# ADC.net
KiCad netlist of a schematic drawn in EAGLE
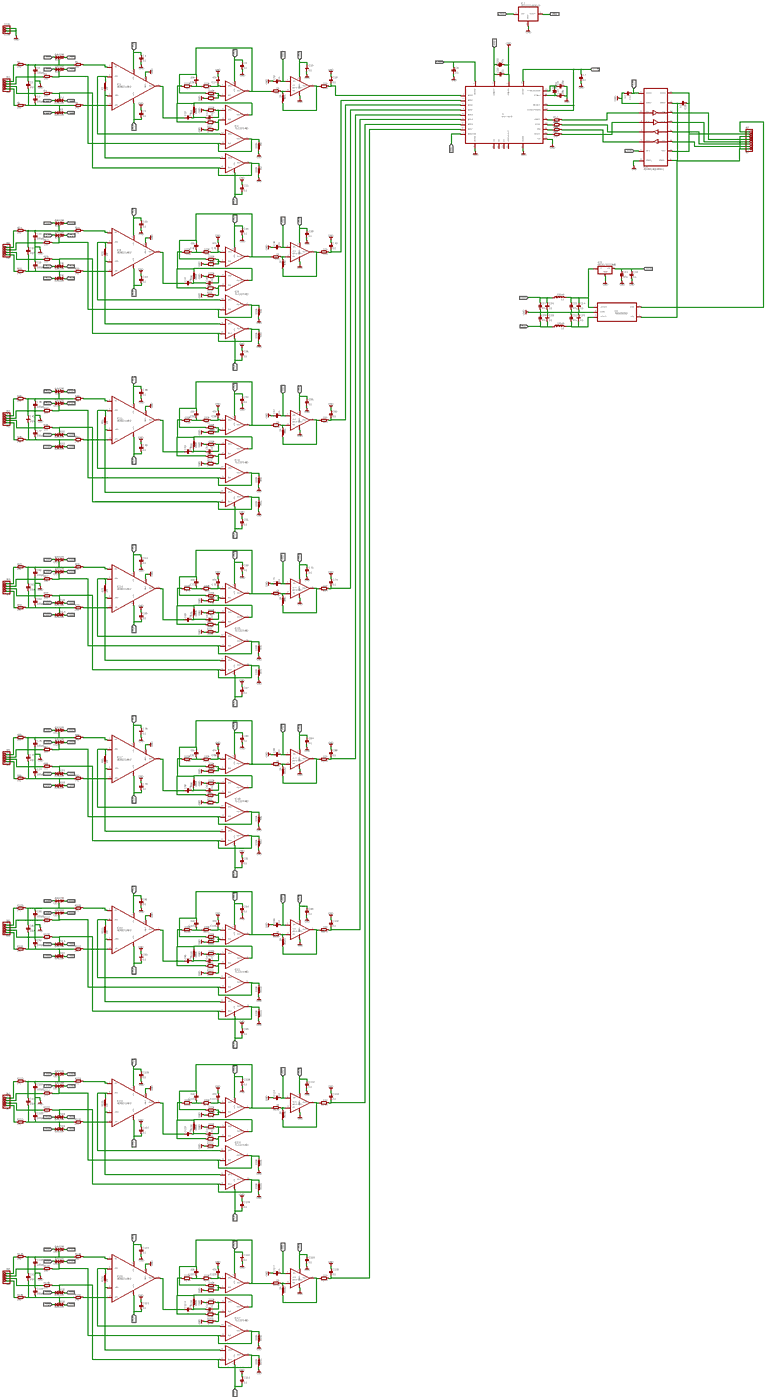
[diagram p0: schematic, sheet 1, overview]
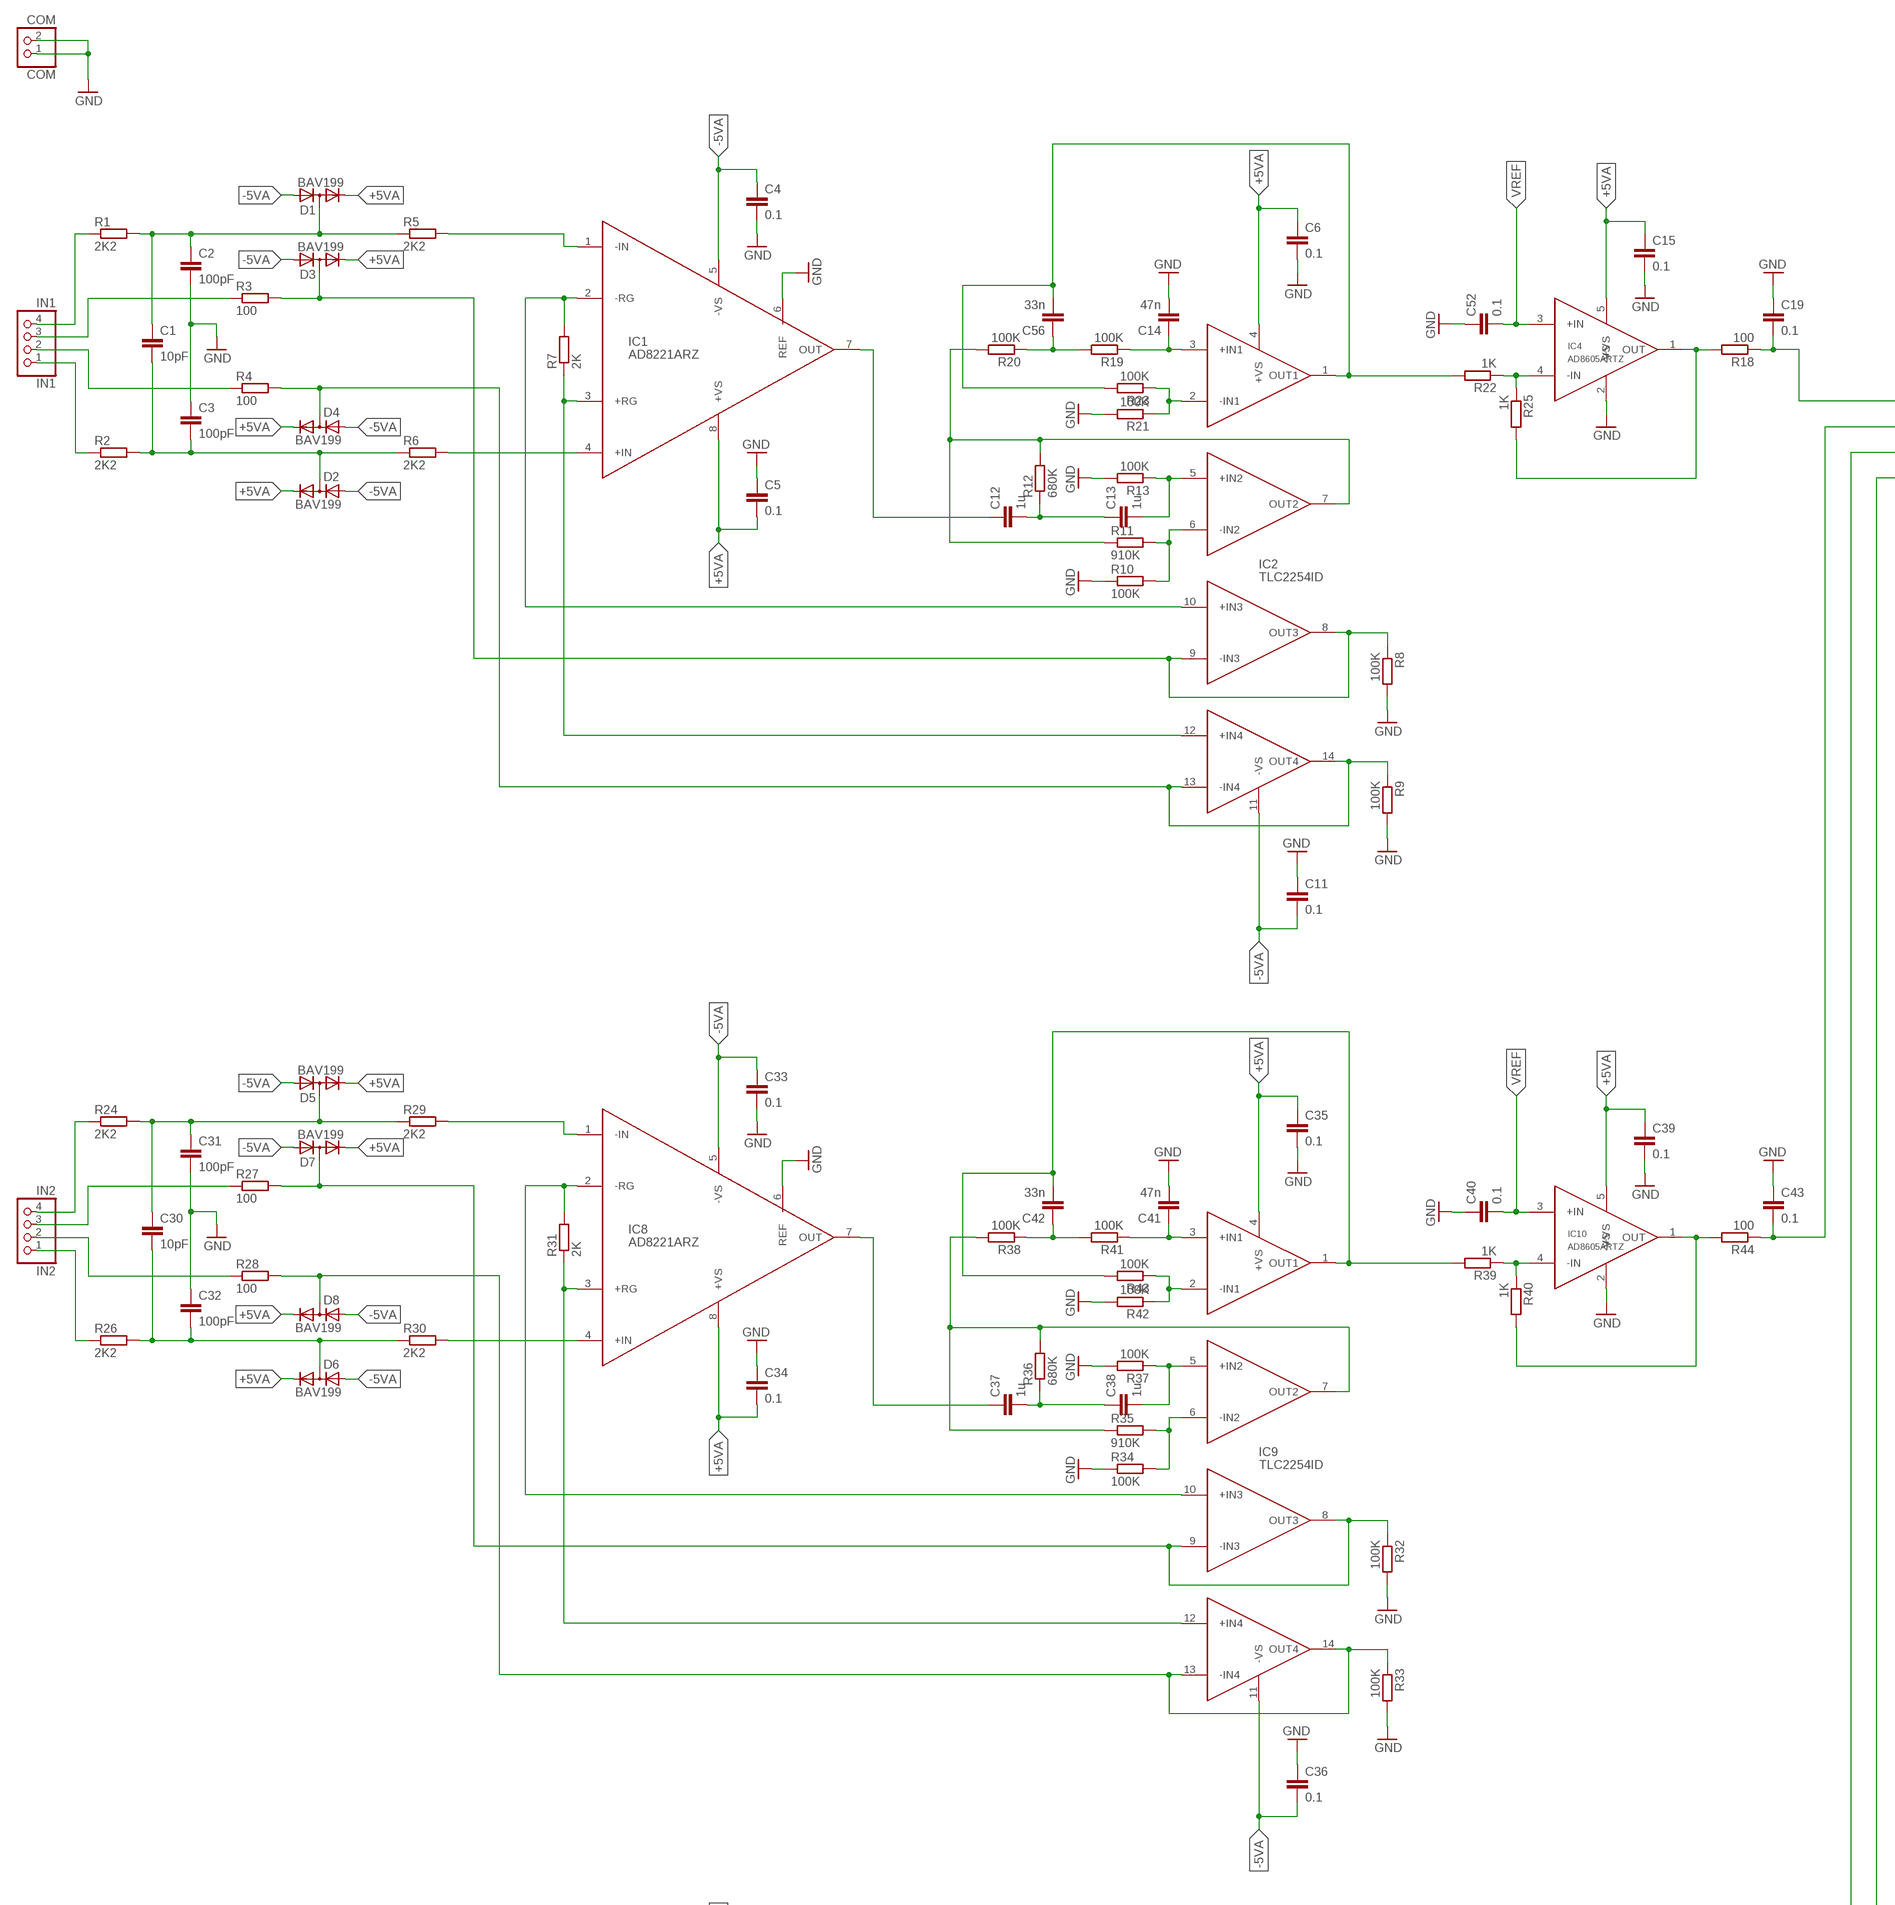
[diagram p1: schematic, sheet 1, part 1 of 5]
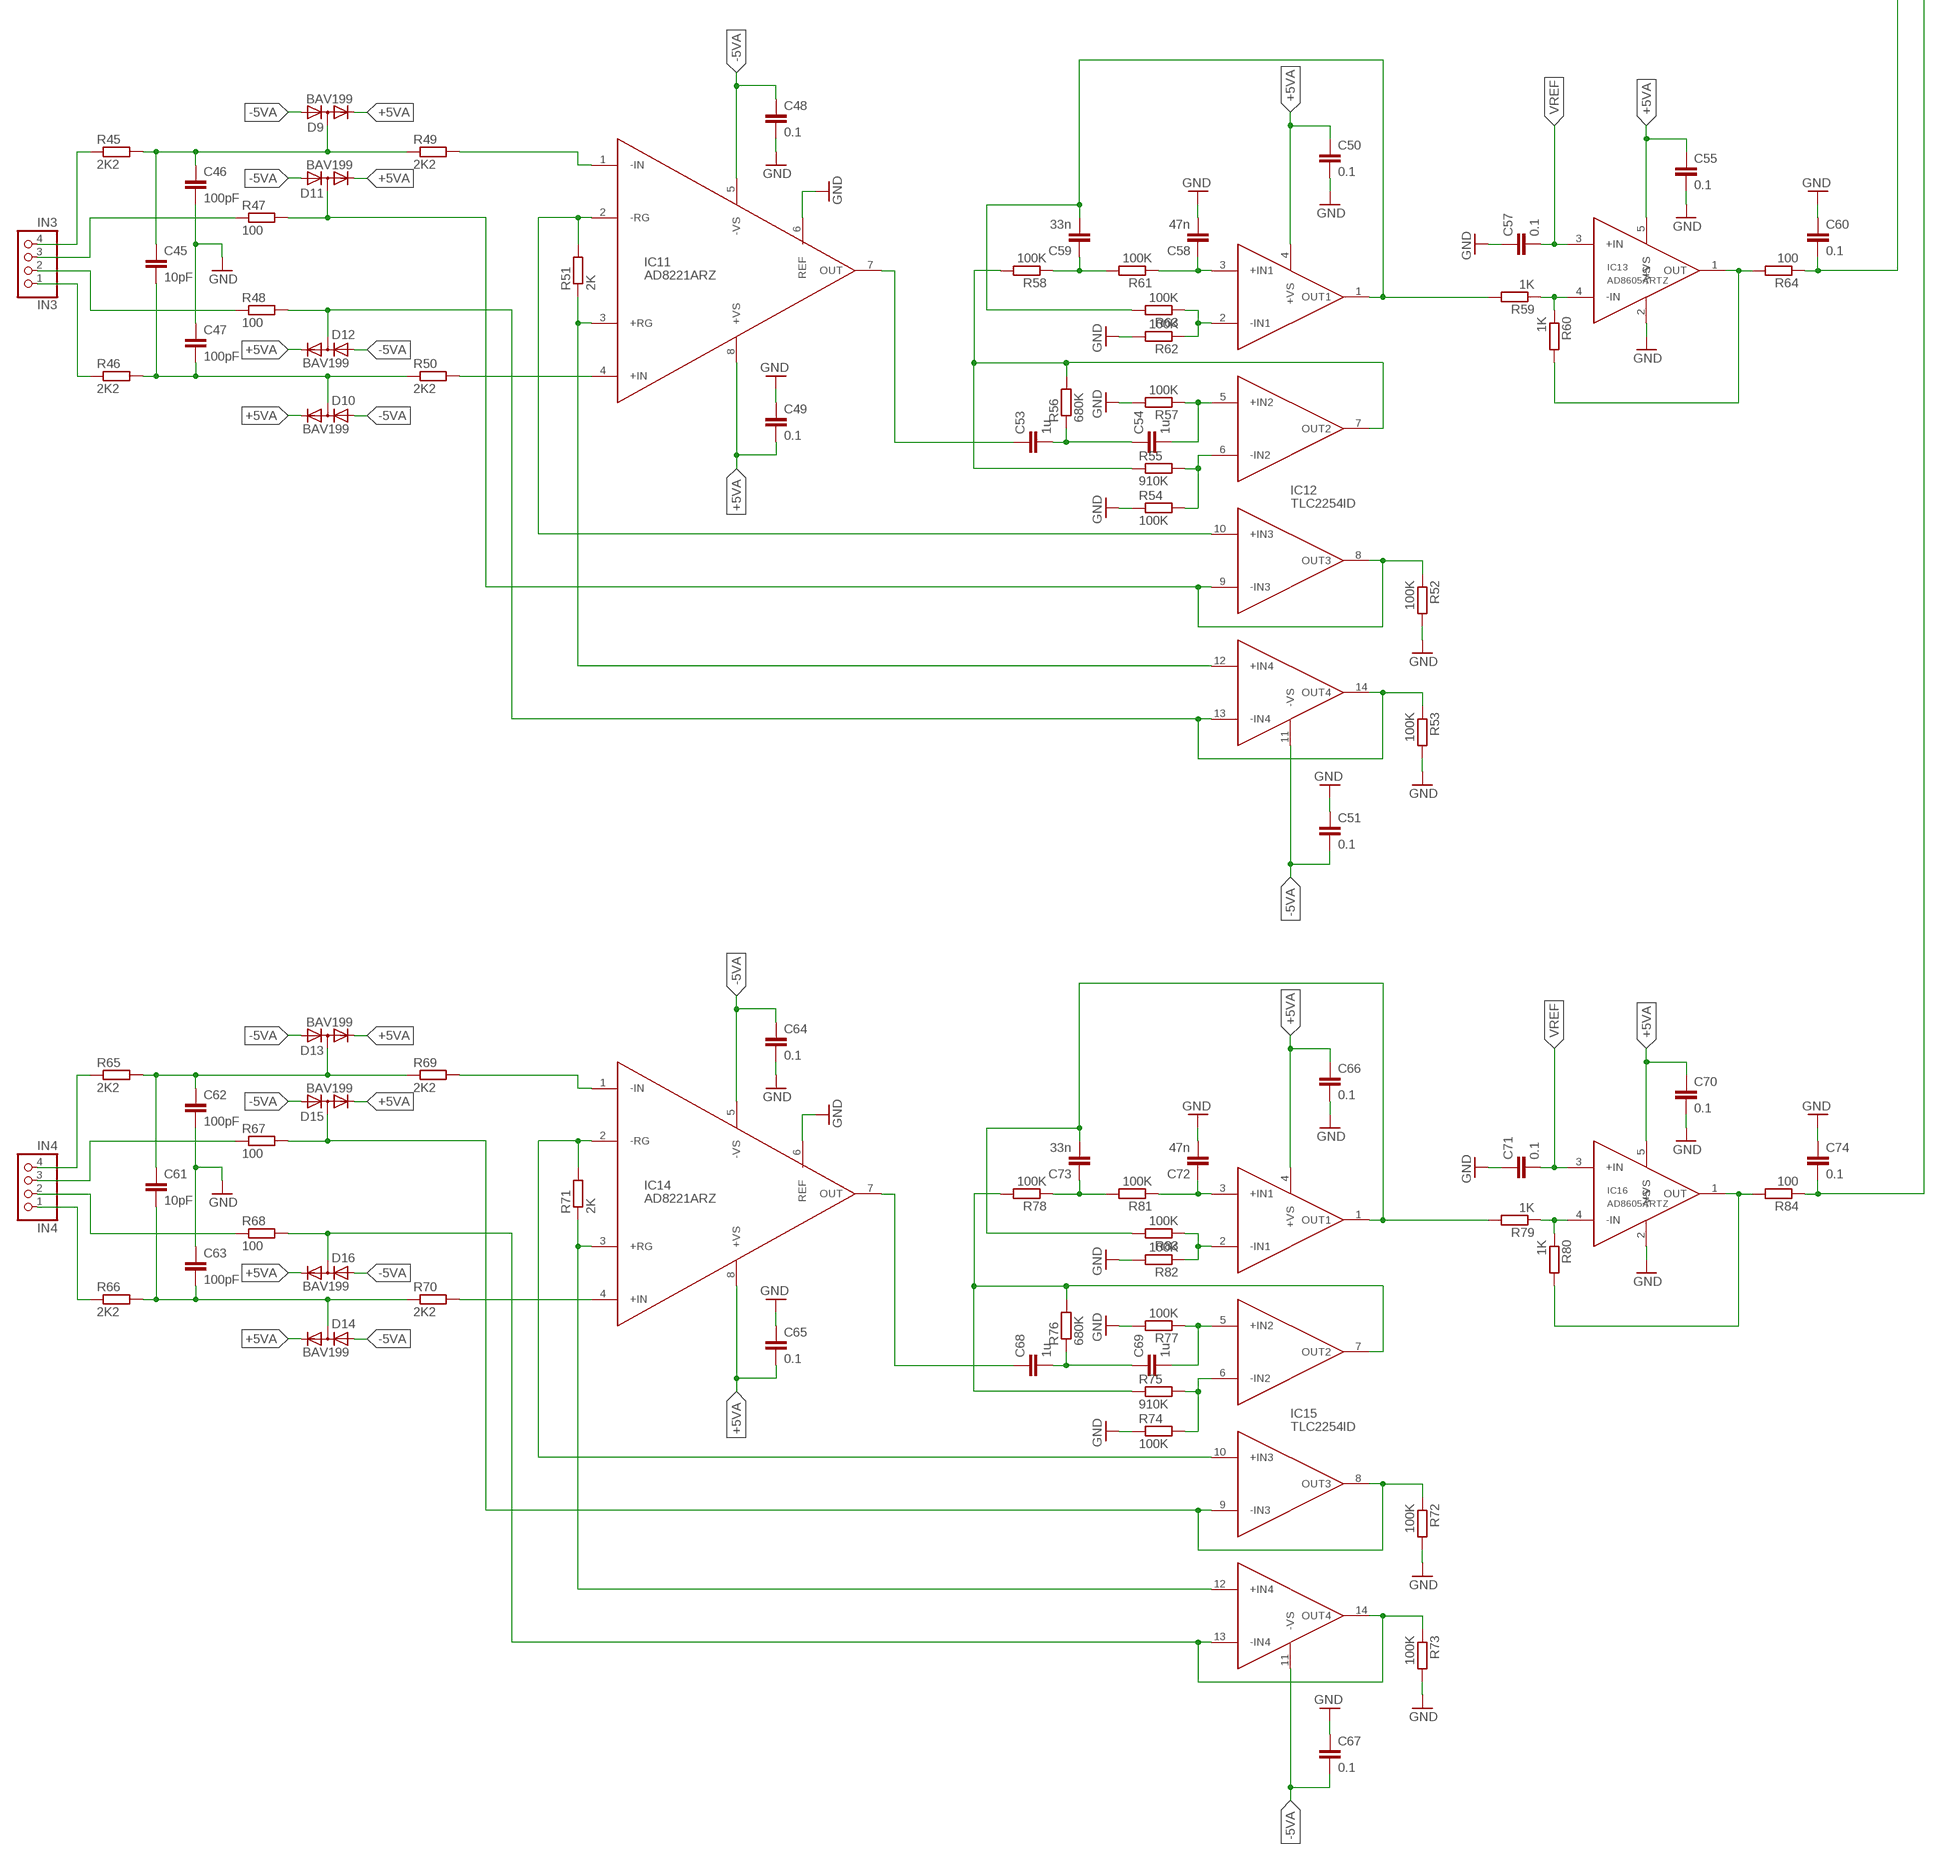
[diagram p2: schematic, sheet 1, part 2 of 5]
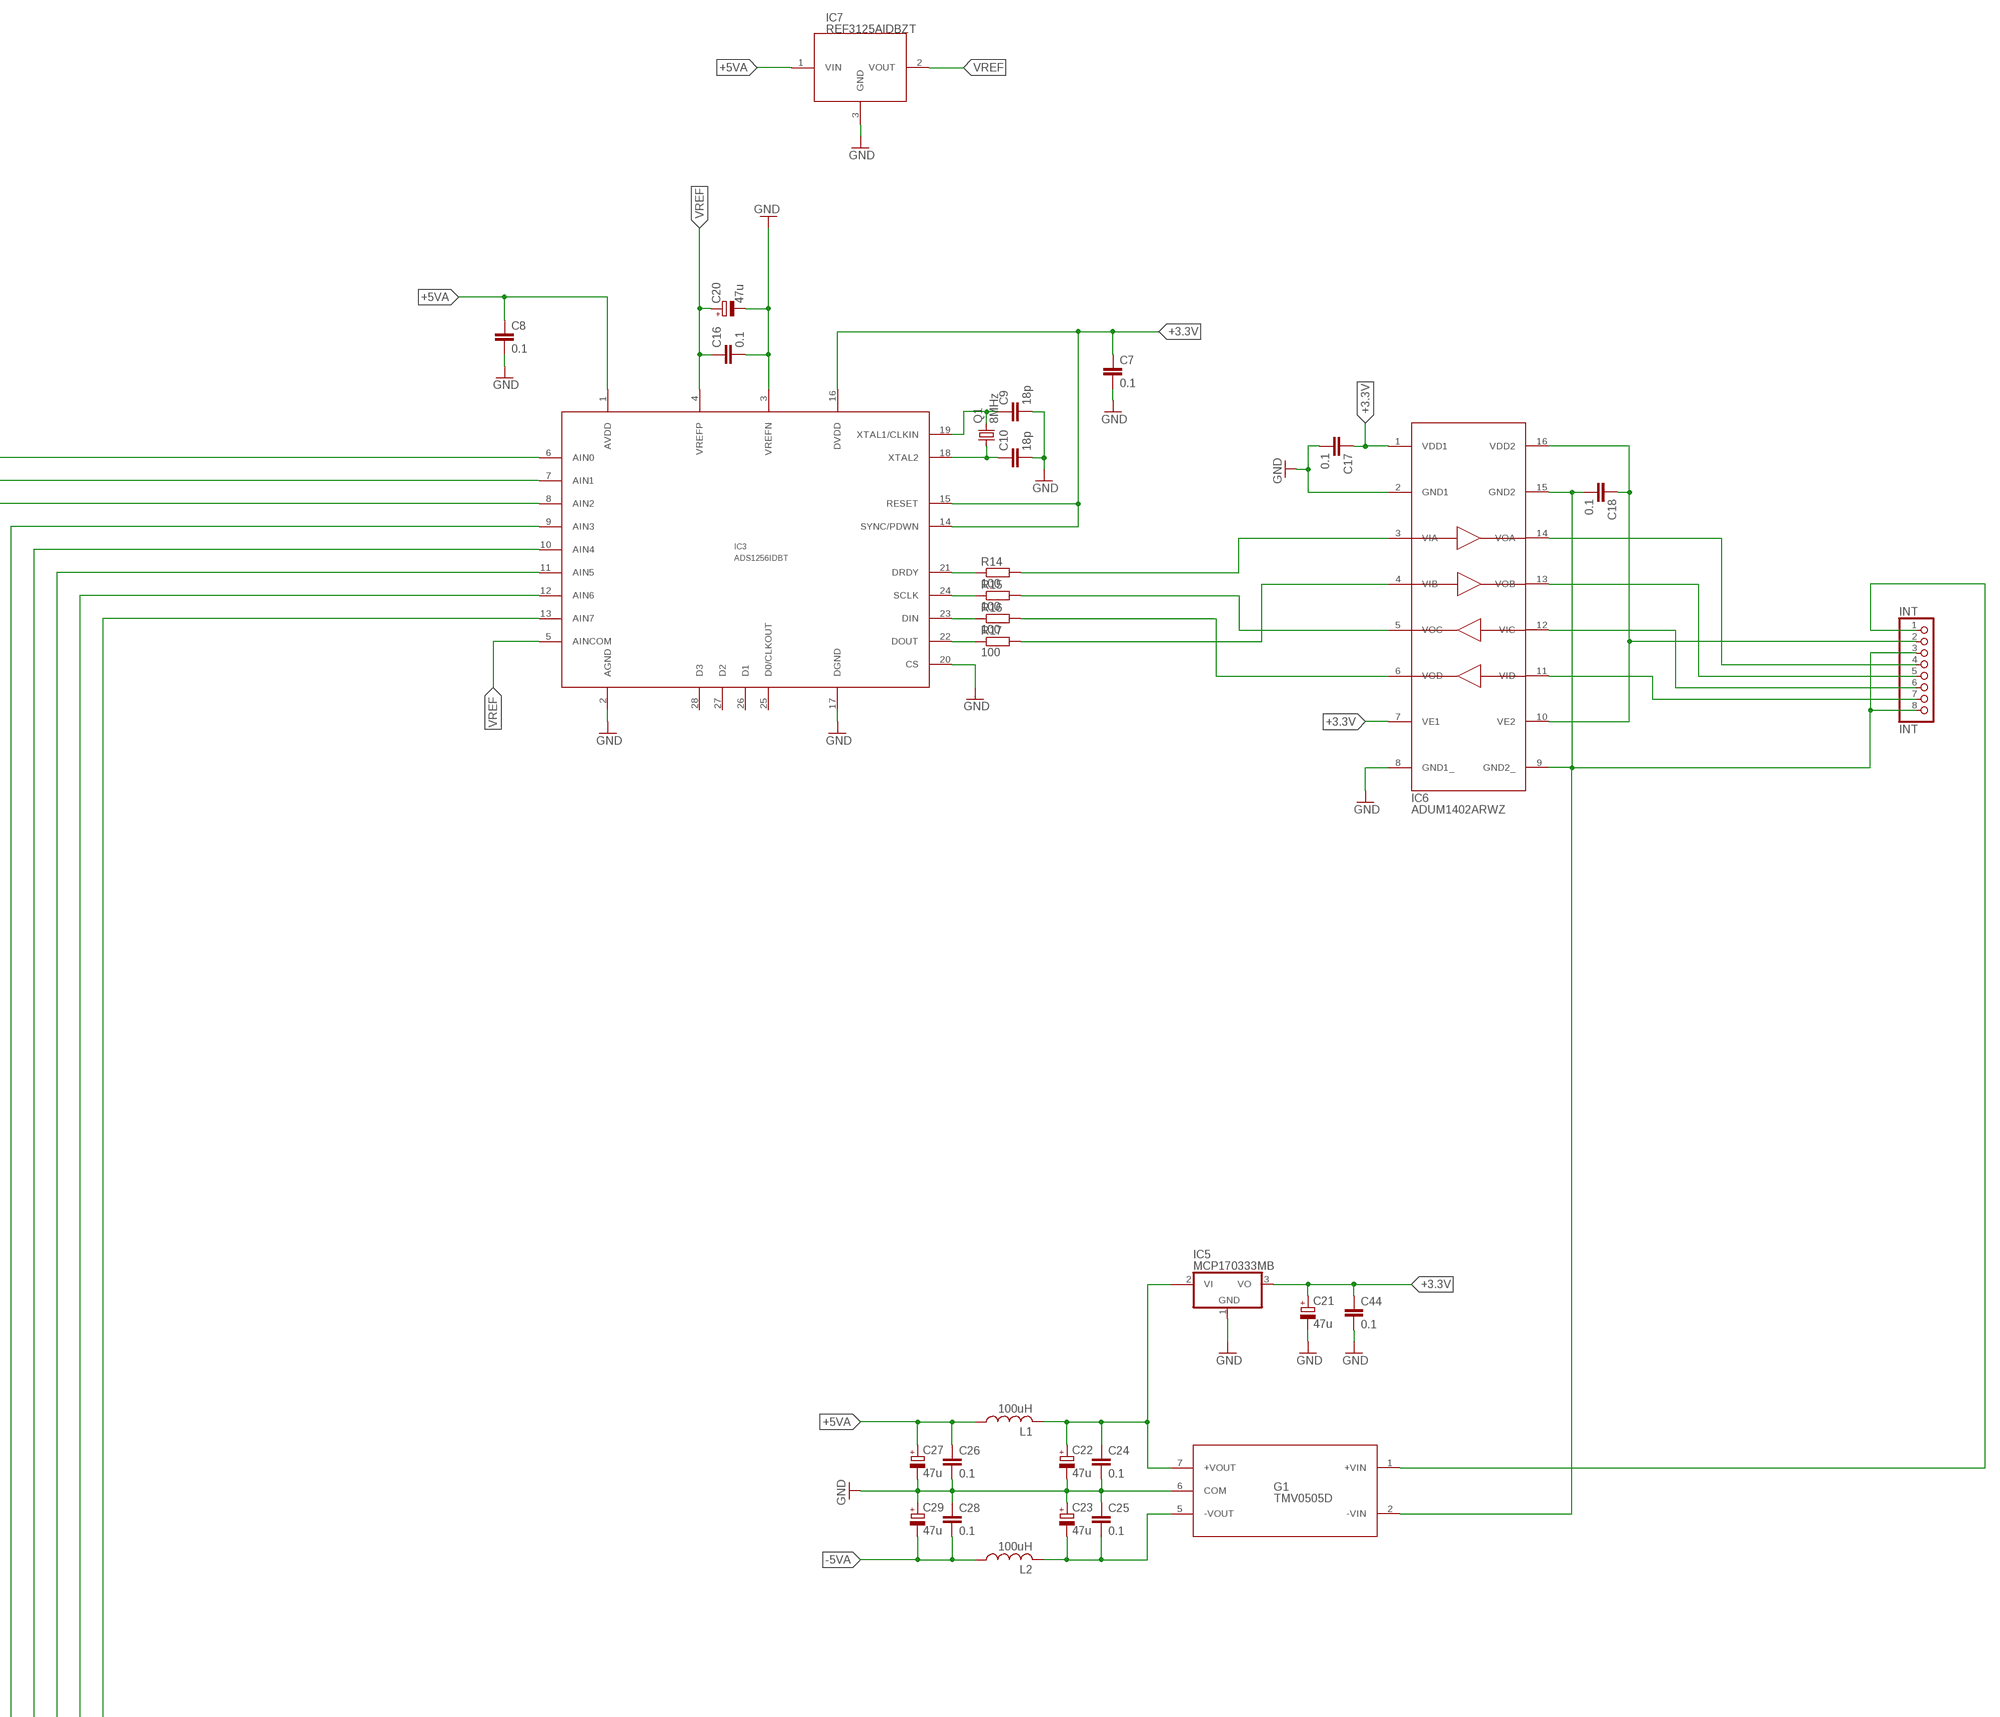
[diagram p3: schematic, sheet 1, part 3 of 5]
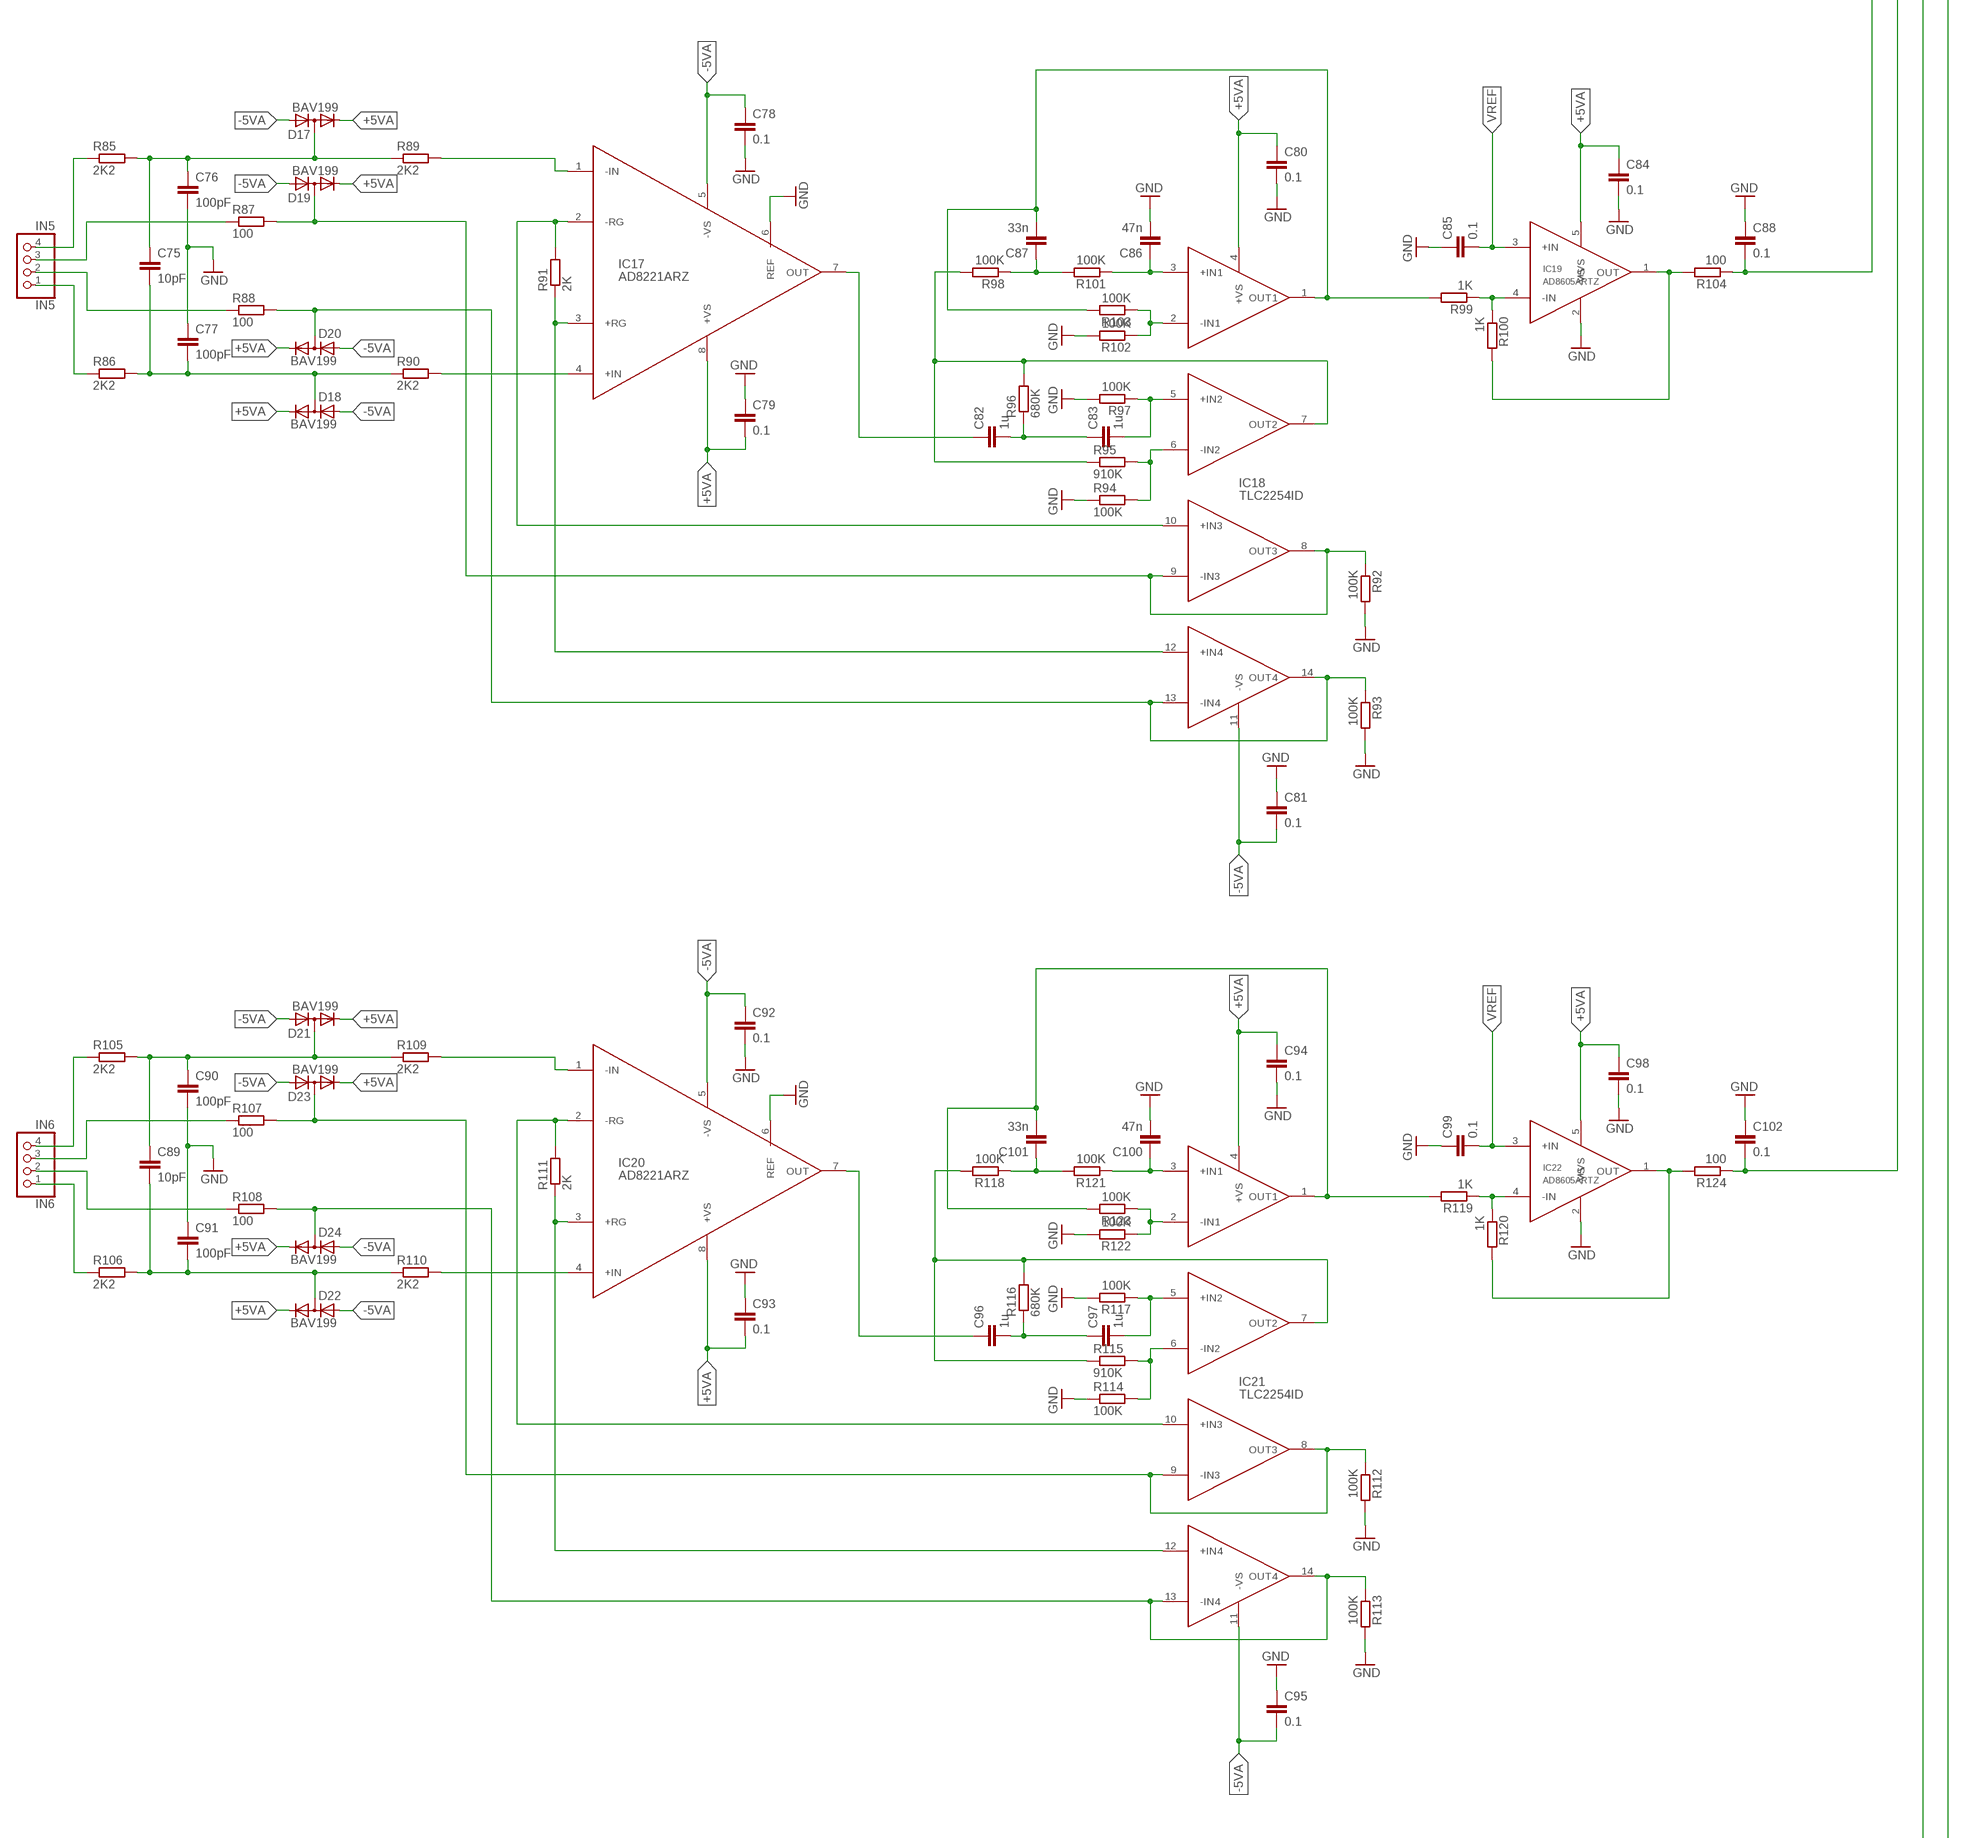
[diagram p4: schematic, sheet 1, part 4 of 5]
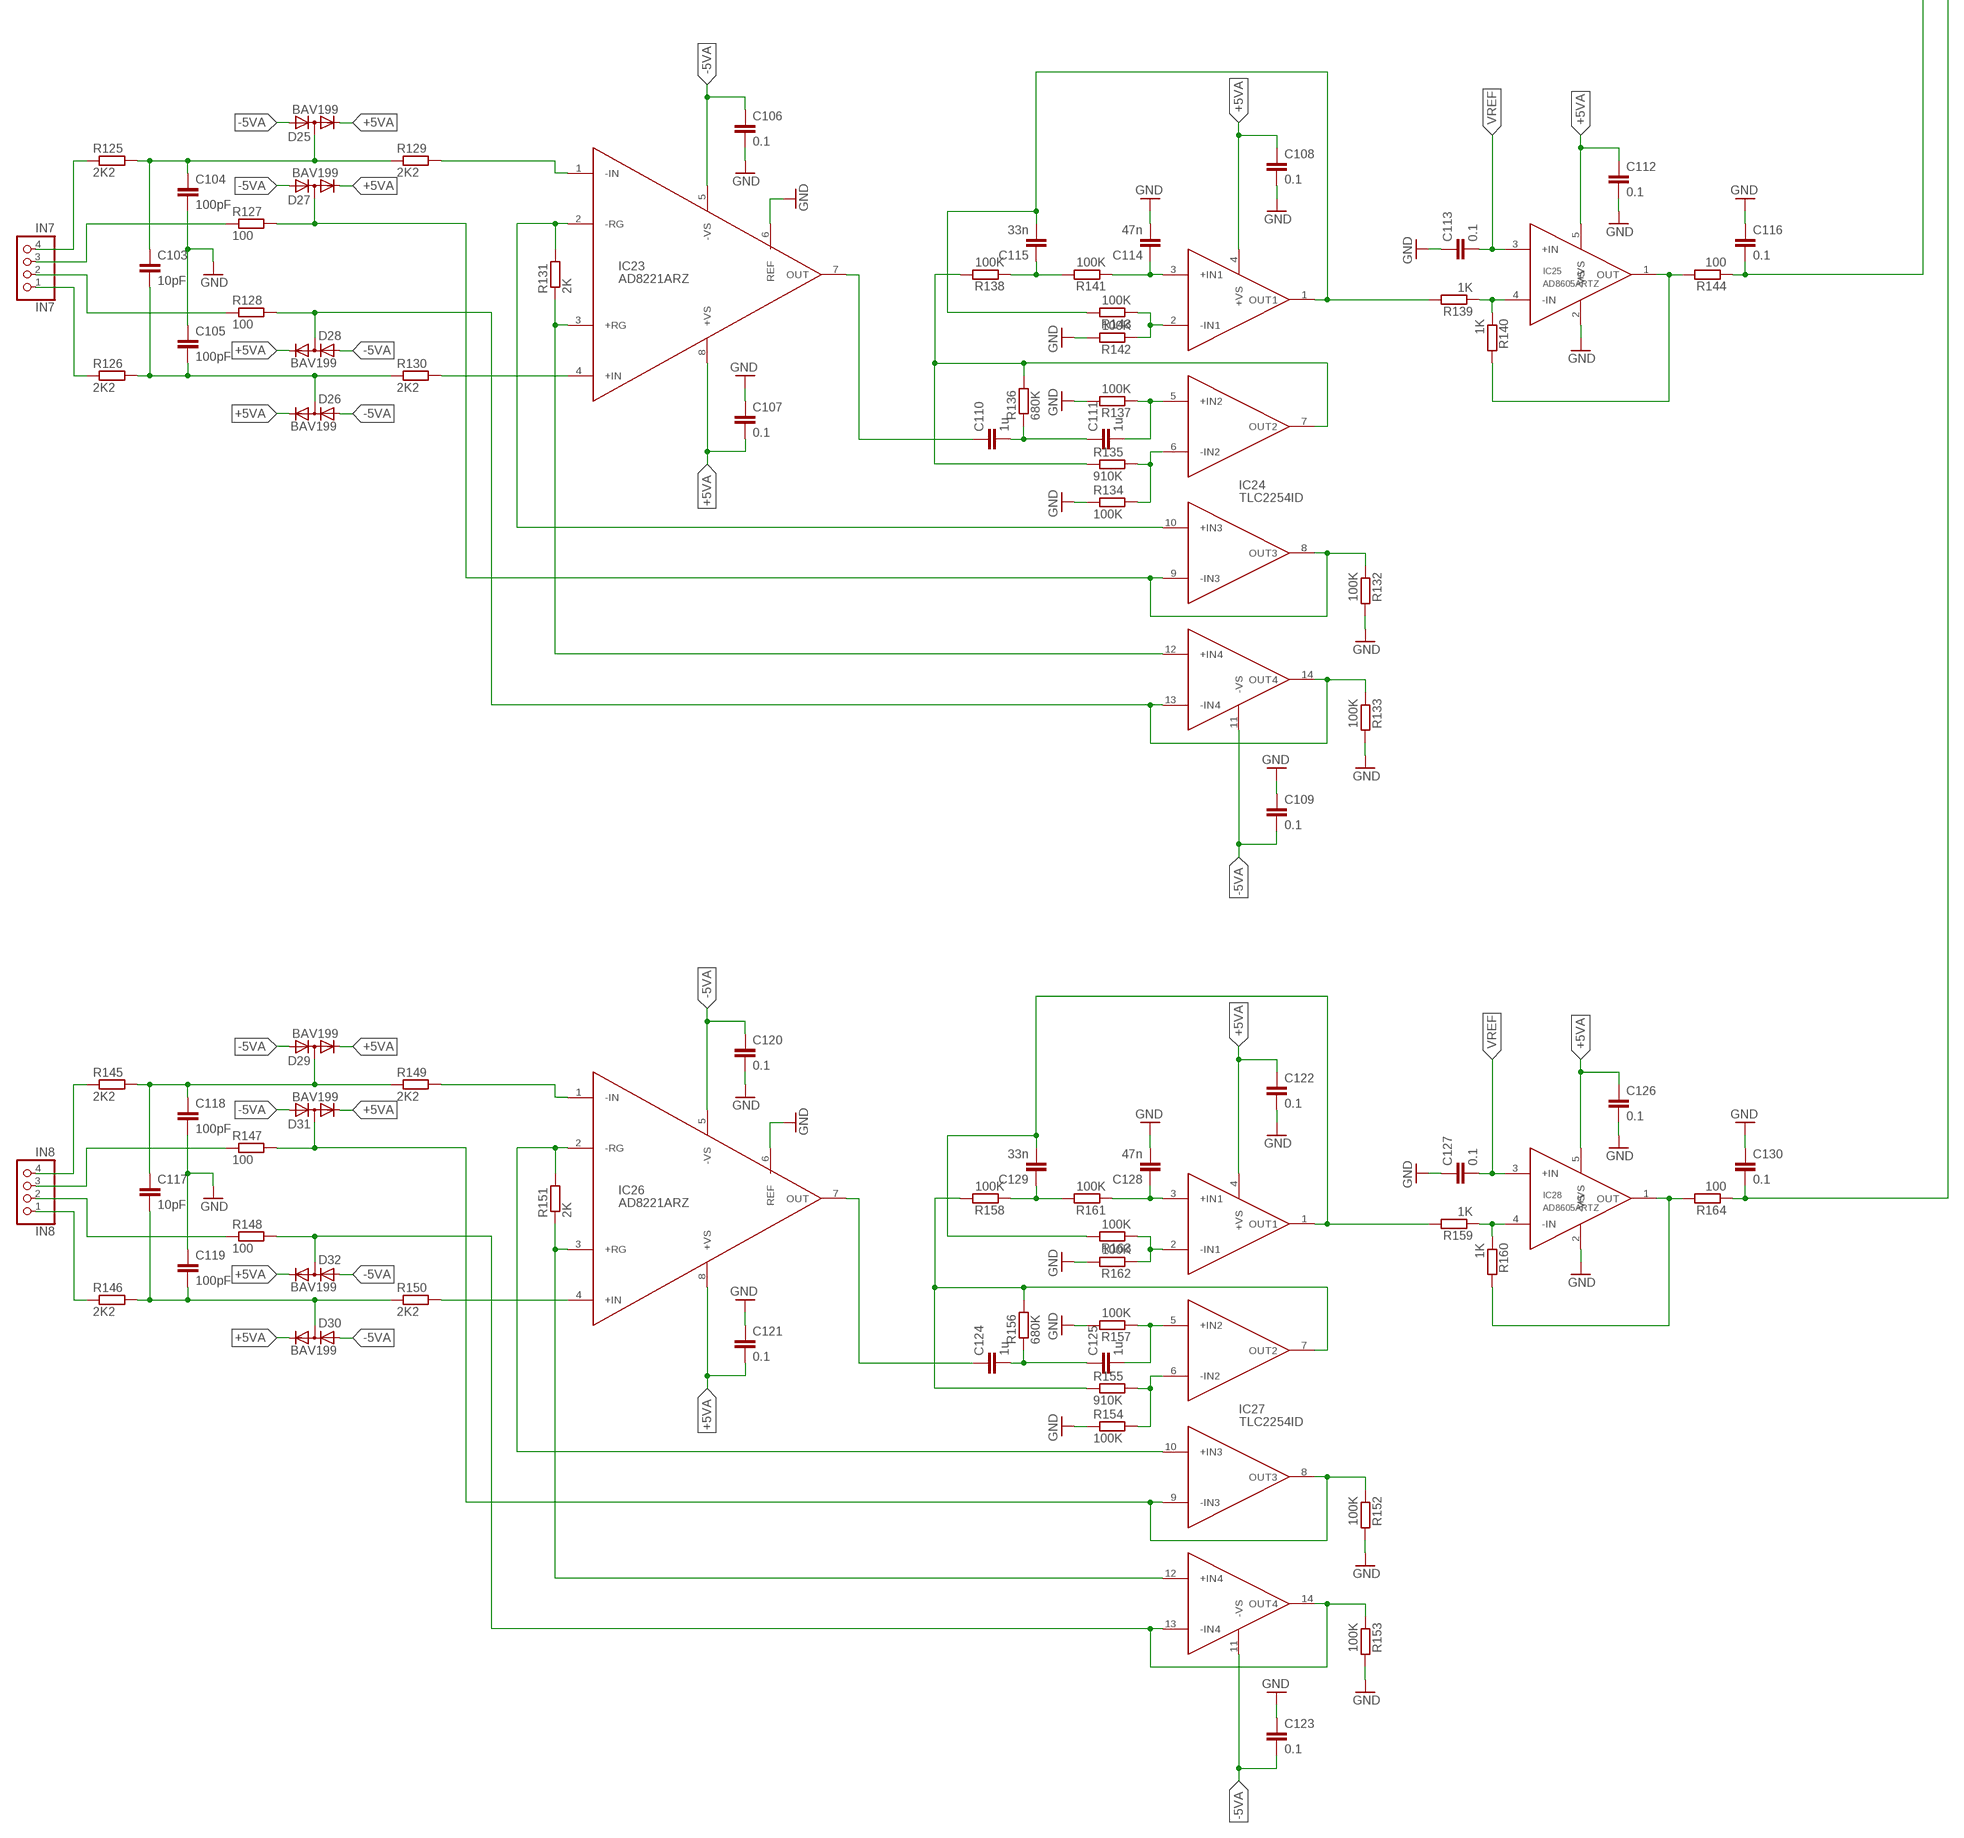
[diagram p5: schematic, sheet 1, part 5 of 5]

(export (version "E")
  (design (tool "Eeschema 10.0.6"))
  (components
    (comp (ref "C1")
      (value "10pF")
      (footprint "eagle-import:C0805")
      (libsource (lib "eagle-import") (part "C-EUC0805"))
    )
    (comp (ref "C2")
      (value "100pF")
      (footprint "eagle-import:C0805")
      (libsource (lib "eagle-import") (part "C-EUC0805"))
    )
    (comp (ref "C3")
      (value "100pF")
      (footprint "eagle-import:C0805")
      (libsource (lib "eagle-import") (part "C-EUC0805"))
    )
    (comp (ref "C4")
      (value "0.1")
      (footprint "eagle-import:C0805")
      (libsource (lib "eagle-import") (part "C-EUC0805"))
    )
    (comp (ref "C5")
      (value "0.1")
      (footprint "eagle-import:C0805")
      (libsource (lib "eagle-import") (part "C-EUC0805"))
    )
    (comp (ref "C6")
      (value "0.1")
      (footprint "eagle-import:C0805")
      (libsource (lib "eagle-import") (part "C-EUC0805"))
    )
    (comp (ref "C7")
      (value "0.1")
      (footprint "eagle-import:C0805")
      (libsource (lib "eagle-import") (part "C-EUC0805"))
    )
    (comp (ref "C8")
      (value "0.1")
      (footprint "eagle-import:C0805")
      (libsource (lib "eagle-import") (part "C-EUC0805"))
    )
    (comp (ref "C9")
      (value "18p")
      (footprint "eagle-import:C0805")
      (libsource (lib "eagle-import") (part "C-EUC0805"))
    )
    (comp (ref "C10")
      (value "18p")
      (footprint "eagle-import:C0805")
      (libsource (lib "eagle-import") (part "C-EUC0805"))
    )
    (comp (ref "C11")
      (value "0.1")
      (footprint "eagle-import:C0805")
      (libsource (lib "eagle-import") (part "C-EUC0805"))
    )
    (comp (ref "C12")
      (value "1u")
      (footprint "eagle-import:C0805")
      (libsource (lib "eagle-import") (part "C-EUC0805"))
    )
    (comp (ref "C13")
      (value "1u")
      (footprint "eagle-import:C0805")
      (libsource (lib "eagle-import") (part "C-EUC0805"))
    )
    (comp (ref "C14")
      (value "47n")
      (footprint "eagle-import:C0805")
      (libsource (lib "eagle-import") (part "C-EUC0805"))
    )
    (comp (ref "C15")
      (value "0.1")
      (footprint "eagle-import:C0805")
      (libsource (lib "eagle-import") (part "C-EUC0805"))
    )
    (comp (ref "C16")
      (value "0.1")
      (footprint "eagle-import:C0805")
      (libsource (lib "eagle-import") (part "C-EUC0805"))
    )
    (comp (ref "C17")
      (value "0.1")
      (footprint "eagle-import:C0805")
      (libsource (lib "eagle-import") (part "C-EUC0805"))
    )
    (comp (ref "C18")
      (value "0.1")
      (footprint "eagle-import:C0805")
      (libsource (lib "eagle-import") (part "C-EUC0805"))
    )
    (comp (ref "C19")
      (value "0.1")
      (footprint "eagle-import:C0805")
      (libsource (lib "eagle-import") (part "C-EUC0805"))
    )
    (comp (ref "C20")
      (value "47u")
      (footprint "eagle-import:E2-4")
      (libsource (lib "eagle-import") (part "CPOL-EUE2-4"))
    )
    (comp (ref "C21")
      (value "47u")
      (footprint "eagle-import:E2-4")
      (libsource (lib "eagle-import") (part "CPOL-EUE2-4"))
    )
    (comp (ref "C22")
      (value "47u")
      (footprint "eagle-import:E2-4")
      (libsource (lib "eagle-import") (part "CPOL-EUE2-4"))
    )
    (comp (ref "C23")
      (value "47u")
      (footprint "eagle-import:E2-4")
      (libsource (lib "eagle-import") (part "CPOL-EUE2-4"))
    )
    (comp (ref "C24")
      (value "0.1")
      (footprint "eagle-import:C0805")
      (libsource (lib "eagle-import") (part "C-EUC0805"))
    )
    (comp (ref "C25")
      (value "0.1")
      (footprint "eagle-import:C0805")
      (libsource (lib "eagle-import") (part "C-EUC0805"))
    )
    (comp (ref "C26")
      (value "0.1")
      (footprint "eagle-import:C0805")
      (libsource (lib "eagle-import") (part "C-EUC0805"))
    )
    (comp (ref "C27")
      (value "47u")
      (footprint "eagle-import:E2-4")
      (libsource (lib "eagle-import") (part "CPOL-EUE2-4"))
    )
    (comp (ref "C28")
      (value "0.1")
      (footprint "eagle-import:C0805")
      (libsource (lib "eagle-import") (part "C-EUC0805"))
    )
    (comp (ref "C29")
      (value "47u")
      (footprint "eagle-import:E2-4")
      (libsource (lib "eagle-import") (part "CPOL-EUE2-4"))
    )
    (comp (ref "C30")
      (value "10pF")
      (footprint "eagle-import:C0805")
      (libsource (lib "eagle-import") (part "C-EUC0805"))
    )
    (comp (ref "C31")
      (value "100pF")
      (footprint "eagle-import:C0805")
      (libsource (lib "eagle-import") (part "C-EUC0805"))
    )
    (comp (ref "C32")
      (value "100pF")
      (footprint "eagle-import:C0805")
      (libsource (lib "eagle-import") (part "C-EUC0805"))
    )
    (comp (ref "C33")
      (value "0.1")
      (footprint "eagle-import:C0805")
      (libsource (lib "eagle-import") (part "C-EUC0805"))
    )
    (comp (ref "C34")
      (value "0.1")
      (footprint "eagle-import:C0805")
      (libsource (lib "eagle-import") (part "C-EUC0805"))
    )
    (comp (ref "C35")
      (value "0.1")
      (footprint "eagle-import:C0805")
      (libsource (lib "eagle-import") (part "C-EUC0805"))
    )
    (comp (ref "C36")
      (value "0.1")
      (footprint "eagle-import:C0805")
      (libsource (lib "eagle-import") (part "C-EUC0805"))
    )
    (comp (ref "C37")
      (value "1u")
      (footprint "eagle-import:C0805")
      (libsource (lib "eagle-import") (part "C-EUC0805"))
    )
    (comp (ref "C38")
      (value "1u")
      (footprint "eagle-import:C0805")
      (libsource (lib "eagle-import") (part "C-EUC0805"))
    )
    (comp (ref "C39")
      (value "0.1")
      (footprint "eagle-import:C0805")
      (libsource (lib "eagle-import") (part "C-EUC0805"))
    )
    (comp (ref "C40")
      (value "0.1")
      (footprint "eagle-import:C0805")
      (libsource (lib "eagle-import") (part "C-EUC0805"))
    )
    (comp (ref "C41")
      (value "47n")
      (footprint "eagle-import:C0805")
      (libsource (lib "eagle-import") (part "C-EUC0805"))
    )
    (comp (ref "C42")
      (value "33n")
      (footprint "eagle-import:C0805")
      (libsource (lib "eagle-import") (part "C-EUC0805"))
    )
    (comp (ref "C43")
      (value "0.1")
      (footprint "eagle-import:C0805")
      (libsource (lib "eagle-import") (part "C-EUC0805"))
    )
    (comp (ref "C44")
      (value "0.1")
      (footprint "eagle-import:C0805")
      (libsource (lib "eagle-import") (part "C-EUC0805"))
    )
    (comp (ref "C45")
      (value "10pF")
      (footprint "eagle-import:C0805")
      (libsource (lib "eagle-import") (part "C-EUC0805"))
    )
    (comp (ref "C46")
      (value "100pF")
      (footprint "eagle-import:C0805")
      (libsource (lib "eagle-import") (part "C-EUC0805"))
    )
    (comp (ref "C47")
      (value "100pF")
      (footprint "eagle-import:C0805")
      (libsource (lib "eagle-import") (part "C-EUC0805"))
    )
    (comp (ref "C48")
      (value "0.1")
      (footprint "eagle-import:C0805")
      (libsource (lib "eagle-import") (part "C-EUC0805"))
    )
    (comp (ref "C49")
      (value "0.1")
      (footprint "eagle-import:C0805")
      (libsource (lib "eagle-import") (part "C-EUC0805"))
    )
    (comp (ref "C50")
      (value "0.1")
      (footprint "eagle-import:C0805")
      (libsource (lib "eagle-import") (part "C-EUC0805"))
    )
    (comp (ref "C51")
      (value "0.1")
      (footprint "eagle-import:C0805")
      (libsource (lib "eagle-import") (part "C-EUC0805"))
    )
    (comp (ref "C52")
      (value "0.1")
      (footprint "eagle-import:C0805")
      (libsource (lib "eagle-import") (part "C-EUC0805"))
    )
    (comp (ref "C53")
      (value "1u")
      (footprint "eagle-import:C0805")
      (libsource (lib "eagle-import") (part "C-EUC0805"))
    )
    (comp (ref "C54")
      (value "1u")
      (footprint "eagle-import:C0805")
      (libsource (lib "eagle-import") (part "C-EUC0805"))
    )
    (comp (ref "C55")
      (value "0.1")
      (footprint "eagle-import:C0805")
      (libsource (lib "eagle-import") (part "C-EUC0805"))
    )
    (comp (ref "C56")
      (value "33n")
      (footprint "eagle-import:C0805")
      (libsource (lib "eagle-import") (part "C-EUC0805"))
    )
    (comp (ref "C57")
      (value "0.1")
      (footprint "eagle-import:C0805")
      (libsource (lib "eagle-import") (part "C-EUC0805"))
    )
    (comp (ref "C58")
      (value "47n")
      (footprint "eagle-import:C0805")
      (libsource (lib "eagle-import") (part "C-EUC0805"))
    )
    (comp (ref "C59")
      (value "33n")
      (footprint "eagle-import:C0805")
      (libsource (lib "eagle-import") (part "C-EUC0805"))
    )
    (comp (ref "C60")
      (value "0.1")
      (footprint "eagle-import:C0805")
      (libsource (lib "eagle-import") (part "C-EUC0805"))
    )
    (comp (ref "C61")
      (value "10pF")
      (footprint "eagle-import:C0805")
      (libsource (lib "eagle-import") (part "C-EUC0805"))
    )
    (comp (ref "C62")
      (value "100pF")
      (footprint "eagle-import:C0805")
      (libsource (lib "eagle-import") (part "C-EUC0805"))
    )
    (comp (ref "C63")
      (value "100pF")
      (footprint "eagle-import:C0805")
      (libsource (lib "eagle-import") (part "C-EUC0805"))
    )
    (comp (ref "C64")
      (value "0.1")
      (footprint "eagle-import:C0805")
      (libsource (lib "eagle-import") (part "C-EUC0805"))
    )
    (comp (ref "C65")
      (value "0.1")
      (footprint "eagle-import:C0805")
      (libsource (lib "eagle-import") (part "C-EUC0805"))
    )
    (comp (ref "C66")
      (value "0.1")
      (footprint "eagle-import:C0805")
      (libsource (lib "eagle-import") (part "C-EUC0805"))
    )
    (comp (ref "C67")
      (value "0.1")
      (footprint "eagle-import:C0805")
      (libsource (lib "eagle-import") (part "C-EUC0805"))
    )
    (comp (ref "C68")
      (value "1u")
      (footprint "eagle-import:C0805")
      (libsource (lib "eagle-import") (part "C-EUC0805"))
    )
    (comp (ref "C69")
      (value "1u")
      (footprint "eagle-import:C0805")
      (libsource (lib "eagle-import") (part "C-EUC0805"))
    )
    (comp (ref "C70")
      (value "0.1")
      (footprint "eagle-import:C0805")
      (libsource (lib "eagle-import") (part "C-EUC0805"))
    )
    (comp (ref "C71")
      (value "0.1")
      (footprint "eagle-import:C0805")
      (libsource (lib "eagle-import") (part "C-EUC0805"))
    )
    (comp (ref "C72")
      (value "47n")
      (footprint "eagle-import:C0805")
      (libsource (lib "eagle-import") (part "C-EUC0805"))
    )
    (comp (ref "C73")
      (value "33n")
      (footprint "eagle-import:C0805")
      (libsource (lib "eagle-import") (part "C-EUC0805"))
    )
    (comp (ref "C74")
      (value "0.1")
      (footprint "eagle-import:C0805")
      (libsource (lib "eagle-import") (part "C-EUC0805"))
    )
    (comp (ref "C75")
      (value "10pF")
      (footprint "eagle-import:C0805")
      (libsource (lib "eagle-import") (part "C-EUC0805"))
    )
    (comp (ref "C76")
      (value "100pF")
      (footprint "eagle-import:C0805")
      (libsource (lib "eagle-import") (part "C-EUC0805"))
    )
    (comp (ref "C77")
      (value "100pF")
      (footprint "eagle-import:C0805")
      (libsource (lib "eagle-import") (part "C-EUC0805"))
    )
    (comp (ref "C78")
      (value "0.1")
      (footprint "eagle-import:C0805")
      (libsource (lib "eagle-import") (part "C-EUC0805"))
    )
    (comp (ref "C79")
      (value "0.1")
      (footprint "eagle-import:C0805")
      (libsource (lib "eagle-import") (part "C-EUC0805"))
    )
    (comp (ref "C80")
      (value "0.1")
      (footprint "eagle-import:C0805")
      (libsource (lib "eagle-import") (part "C-EUC0805"))
    )
    (comp (ref "C81")
      (value "0.1")
      (footprint "eagle-import:C0805")
      (libsource (lib "eagle-import") (part "C-EUC0805"))
    )
    (comp (ref "C82")
      (value "1u")
      (footprint "eagle-import:C0805")
      (libsource (lib "eagle-import") (part "C-EUC0805"))
    )
    (comp (ref "C83")
      (value "1u")
      (footprint "eagle-import:C0805")
      (libsource (lib "eagle-import") (part "C-EUC0805"))
    )
    (comp (ref "C84")
      (value "0.1")
      (footprint "eagle-import:C0805")
      (libsource (lib "eagle-import") (part "C-EUC0805"))
    )
    (comp (ref "C85")
      (value "0.1")
      (footprint "eagle-import:C0805")
      (libsource (lib "eagle-import") (part "C-EUC0805"))
    )
    (comp (ref "C86")
      (value "47n")
      (footprint "eagle-import:C0805")
      (libsource (lib "eagle-import") (part "C-EUC0805"))
    )
    (comp (ref "C87")
      (value "33n")
      (footprint "eagle-import:C0805")
      (libsource (lib "eagle-import") (part "C-EUC0805"))
    )
    (comp (ref "C88")
      (value "0.1")
      (footprint "eagle-import:C0805")
      (libsource (lib "eagle-import") (part "C-EUC0805"))
    )
    (comp (ref "C89")
      (value "10pF")
      (footprint "eagle-import:C0805")
      (libsource (lib "eagle-import") (part "C-EUC0805"))
    )
    (comp (ref "C90")
      (value "100pF")
      (footprint "eagle-import:C0805")
      (libsource (lib "eagle-import") (part "C-EUC0805"))
    )
    (comp (ref "C91")
      (value "100pF")
      (footprint "eagle-import:C0805")
      (libsource (lib "eagle-import") (part "C-EUC0805"))
    )
    (comp (ref "C92")
      (value "0.1")
      (footprint "eagle-import:C0805")
      (libsource (lib "eagle-import") (part "C-EUC0805"))
    )
    (comp (ref "C93")
      (value "0.1")
      (footprint "eagle-import:C0805")
      (libsource (lib "eagle-import") (part "C-EUC0805"))
    )
    (comp (ref "C94")
      (value "0.1")
      (footprint "eagle-import:C0805")
      (libsource (lib "eagle-import") (part "C-EUC0805"))
    )
    (comp (ref "C95")
      (value "0.1")
      (footprint "eagle-import:C0805")
      (libsource (lib "eagle-import") (part "C-EUC0805"))
    )
    (comp (ref "C96")
      (value "1u")
      (footprint "eagle-import:C0805")
      (libsource (lib "eagle-import") (part "C-EUC0805"))
    )
    (comp (ref "C97")
      (value "1u")
      (footprint "eagle-import:C0805")
      (libsource (lib "eagle-import") (part "C-EUC0805"))
    )
    (comp (ref "C98")
      (value "0.1")
      (footprint "eagle-import:C0805")
      (libsource (lib "eagle-import") (part "C-EUC0805"))
    )
    (comp (ref "C99")
      (value "0.1")
      (footprint "eagle-import:C0805")
      (libsource (lib "eagle-import") (part "C-EUC0805"))
    )
    (comp (ref "C100")
      (value "47n")
      (footprint "eagle-import:C0805")
      (libsource (lib "eagle-import") (part "C-EUC0805"))
    )
    (comp (ref "C101")
      (value "33n")
      (footprint "eagle-import:C0805")
      (libsource (lib "eagle-import") (part "C-EUC0805"))
    )
    (comp (ref "C102")
      (value "0.1")
      (footprint "eagle-import:C0805")
      (libsource (lib "eagle-import") (part "C-EUC0805"))
    )
    (comp (ref "C103")
      (value "10pF")
      (footprint "eagle-import:C0805")
      (libsource (lib "eagle-import") (part "C-EUC0805"))
    )
    (comp (ref "C104")
      (value "100pF")
      (footprint "eagle-import:C0805")
      (libsource (lib "eagle-import") (part "C-EUC0805"))
    )
    (comp (ref "C105")
      (value "100pF")
      (footprint "eagle-import:C0805")
      (libsource (lib "eagle-import") (part "C-EUC0805"))
    )
    (comp (ref "C106")
      (value "0.1")
      (footprint "eagle-import:C0805")
      (libsource (lib "eagle-import") (part "C-EUC0805"))
    )
    (comp (ref "C107")
      (value "0.1")
      (footprint "eagle-import:C0805")
      (libsource (lib "eagle-import") (part "C-EUC0805"))
    )
    (comp (ref "C108")
      (value "0.1")
      (footprint "eagle-import:C0805")
      (libsource (lib "eagle-import") (part "C-EUC0805"))
    )
    (comp (ref "C109")
      (value "0.1")
      (footprint "eagle-import:C0805")
      (libsource (lib "eagle-import") (part "C-EUC0805"))
    )
    (comp (ref "C110")
      (value "1u")
      (footprint "eagle-import:C0805")
      (libsource (lib "eagle-import") (part "C-EUC0805"))
    )
    (comp (ref "C111")
      (value "1u")
      (footprint "eagle-import:C0805")
      (libsource (lib "eagle-import") (part "C-EUC0805"))
    )
    (comp (ref "C112")
      (value "0.1")
      (footprint "eagle-import:C0805")
      (libsource (lib "eagle-import") (part "C-EUC0805"))
    )
    (comp (ref "C113")
      (value "0.1")
      (footprint "eagle-import:C0805")
      (libsource (lib "eagle-import") (part "C-EUC0805"))
    )
    (comp (ref "C114")
      (value "47n")
      (footprint "eagle-import:C0805")
      (libsource (lib "eagle-import") (part "C-EUC0805"))
    )
    (comp (ref "C115")
      (value "33n")
      (footprint "eagle-import:C0805")
      (libsource (lib "eagle-import") (part "C-EUC0805"))
    )
    (comp (ref "C116")
      (value "0.1")
      (footprint "eagle-import:C0805")
      (libsource (lib "eagle-import") (part "C-EUC0805"))
    )
    (comp (ref "C117")
      (value "10pF")
      (footprint "eagle-import:C0805")
      (libsource (lib "eagle-import") (part "C-EUC0805"))
    )
    (comp (ref "C118")
      (value "100pF")
      (footprint "eagle-import:C0805")
      (libsource (lib "eagle-import") (part "C-EUC0805"))
    )
    (comp (ref "C119")
      (value "100pF")
      (footprint "eagle-import:C0805")
      (libsource (lib "eagle-import") (part "C-EUC0805"))
    )
    (comp (ref "C120")
      (value "0.1")
      (footprint "eagle-import:C0805")
      (libsource (lib "eagle-import") (part "C-EUC0805"))
    )
    (comp (ref "C121")
      (value "0.1")
      (footprint "eagle-import:C0805")
      (libsource (lib "eagle-import") (part "C-EUC0805"))
    )
    (comp (ref "C122")
      (value "0.1")
      (footprint "eagle-import:C0805")
      (libsource (lib "eagle-import") (part "C-EUC0805"))
    )
    (comp (ref "C123")
      (value "0.1")
      (footprint "eagle-import:C0805")
      (libsource (lib "eagle-import") (part "C-EUC0805"))
    )
    (comp (ref "C124")
      (value "1u")
      (footprint "eagle-import:C0805")
      (libsource (lib "eagle-import") (part "C-EUC0805"))
    )
    (comp (ref "C125")
      (value "1u")
      (footprint "eagle-import:C0805")
      (libsource (lib "eagle-import") (part "C-EUC0805"))
    )
    (comp (ref "C126")
      (value "0.1")
      (footprint "eagle-import:C0805")
      (libsource (lib "eagle-import") (part "C-EUC0805"))
    )
    (comp (ref "C127")
      (value "0.1")
      (footprint "eagle-import:C0805")
      (libsource (lib "eagle-import") (part "C-EUC0805"))
    )
    (comp (ref "C128")
      (value "47n")
      (footprint "eagle-import:C0805")
      (libsource (lib "eagle-import") (part "C-EUC0805"))
    )
    (comp (ref "C129")
      (value "33n")
      (footprint "eagle-import:C0805")
      (libsource (lib "eagle-import") (part "C-EUC0805"))
    )
    (comp (ref "C130")
      (value "0.1")
      (footprint "eagle-import:C0805")
      (libsource (lib "eagle-import") (part "C-EUC0805"))
    )
    (comp (ref "COM")
      (value "COM")
      (footprint "eagle-import:1X02")
      (libsource (lib "eagle-import") (part "PINHD-1X2"))
    )
    (comp (ref "D1")
      (value "BAV199")
      (footprint "eagle-import:SOT23")
      (libsource (lib "eagle-import") (part "BAV199"))
    )
    (comp (ref "D2")
      (value "BAV199")
      (footprint "eagle-import:SOT23")
      (libsource (lib "eagle-import") (part "BAV199"))
    )
    (comp (ref "D3")
      (value "BAV199")
      (footprint "eagle-import:SOT23")
      (libsource (lib "eagle-import") (part "BAV199"))
    )
    (comp (ref "D4")
      (value "BAV199")
      (footprint "eagle-import:SOT23")
      (libsource (lib "eagle-import") (part "BAV199"))
    )
    (comp (ref "D5")
      (value "BAV199")
      (footprint "eagle-import:SOT23")
      (libsource (lib "eagle-import") (part "BAV199"))
    )
    (comp (ref "D6")
      (value "BAV199")
      (footprint "eagle-import:SOT23")
      (libsource (lib "eagle-import") (part "BAV199"))
    )
    (comp (ref "D7")
      (value "BAV199")
      (footprint "eagle-import:SOT23")
      (libsource (lib "eagle-import") (part "BAV199"))
    )
    (comp (ref "D8")
      (value "BAV199")
      (footprint "eagle-import:SOT23")
      (libsource (lib "eagle-import") (part "BAV199"))
    )
    (comp (ref "D9")
      (value "BAV199")
      (footprint "eagle-import:SOT23")
      (libsource (lib "eagle-import") (part "BAV199"))
    )
    (comp (ref "D10")
      (value "BAV199")
      (footprint "eagle-import:SOT23")
      (libsource (lib "eagle-import") (part "BAV199"))
    )
    (comp (ref "D11")
      (value "BAV199")
      (footprint "eagle-import:SOT23")
      (libsource (lib "eagle-import") (part "BAV199"))
    )
    (comp (ref "D12")
      (value "BAV199")
      (footprint "eagle-import:SOT23")
      (libsource (lib "eagle-import") (part "BAV199"))
    )
    (comp (ref "D13")
      (value "BAV199")
      (footprint "eagle-import:SOT23")
      (libsource (lib "eagle-import") (part "BAV199"))
    )
    (comp (ref "D14")
      (value "BAV199")
      (footprint "eagle-import:SOT23")
      (libsource (lib "eagle-import") (part "BAV199"))
    )
    (comp (ref "D15")
      (value "BAV199")
      (footprint "eagle-import:SOT23")
      (libsource (lib "eagle-import") (part "BAV199"))
    )
    (comp (ref "D16")
      (value "BAV199")
      (footprint "eagle-import:SOT23")
      (libsource (lib "eagle-import") (part "BAV199"))
    )
    (comp (ref "D17")
      (value "BAV199")
      (footprint "eagle-import:SOT23")
      (libsource (lib "eagle-import") (part "BAV199"))
    )
    (comp (ref "D18")
      (value "BAV199")
      (footprint "eagle-import:SOT23")
      (libsource (lib "eagle-import") (part "BAV199"))
    )
    (comp (ref "D19")
      (value "BAV199")
      (footprint "eagle-import:SOT23")
      (libsource (lib "eagle-import") (part "BAV199"))
    )
    (comp (ref "D20")
      (value "BAV199")
      (footprint "eagle-import:SOT23")
      (libsource (lib "eagle-import") (part "BAV199"))
    )
    (comp (ref "D21")
      (value "BAV199")
      (footprint "eagle-import:SOT23")
      (libsource (lib "eagle-import") (part "BAV199"))
    )
    (comp (ref "D22")
      (value "BAV199")
      (footprint "eagle-import:SOT23")
      (libsource (lib "eagle-import") (part "BAV199"))
    )
    (comp (ref "D23")
      (value "BAV199")
      (footprint "eagle-import:SOT23")
      (libsource (lib "eagle-import") (part "BAV199"))
    )
    (comp (ref "D24")
      (value "BAV199")
      (footprint "eagle-import:SOT23")
      (libsource (lib "eagle-import") (part "BAV199"))
    )
    (comp (ref "D25")
      (value "BAV199")
      (footprint "eagle-import:SOT23")
      (libsource (lib "eagle-import") (part "BAV199"))
    )
    (comp (ref "D26")
      (value "BAV199")
      (footprint "eagle-import:SOT23")
      (libsource (lib "eagle-import") (part "BAV199"))
    )
    (comp (ref "D27")
      (value "BAV199")
      (footprint "eagle-import:SOT23")
      (libsource (lib "eagle-import") (part "BAV199"))
    )
    (comp (ref "D28")
      (value "BAV199")
      (footprint "eagle-import:SOT23")
      (libsource (lib "eagle-import") (part "BAV199"))
    )
    (comp (ref "D29")
      (value "BAV199")
      (footprint "eagle-import:SOT23")
      (libsource (lib "eagle-import") (part "BAV199"))
    )
    (comp (ref "D30")
      (value "BAV199")
      (footprint "eagle-import:SOT23")
      (libsource (lib "eagle-import") (part "BAV199"))
    )
    (comp (ref "D31")
      (value "BAV199")
      (footprint "eagle-import:SOT23")
      (libsource (lib "eagle-import") (part "BAV199"))
    )
    (comp (ref "D32")
      (value "BAV199")
      (footprint "eagle-import:SOT23")
      (libsource (lib "eagle-import") (part "BAV199"))
    )
    (comp (ref "G1")
      (value "TMV0505D")
      (footprint "eagle-import:TMV0505D")
      (libsource (lib "eagle-import") (part "TMV0505D"))
    )
    (comp (ref "IC1")
      (value "AD8221ARZ")
      (footprint "eagle-import:SO-08")
      (libsource (lib "eagle-import") (part "AD8221ARZ"))
    )
    (comp (ref "IC2")
      (value "TLC2254ID")
      (footprint "eagle-import:TLC2254ID")
      (libsource (lib "eagle-import") (part "TLC2254ID"))
    )
    (comp (ref "IC3")
      (value "ADS1256IDBT")
      (footprint "eagle-import:ADS1256IDBT")
      (libsource (lib "eagle-import") (part "ADS1256IDBT"))
    )
    (comp (ref "IC4")
      (value "AD8605ARTZ")
      (footprint "eagle-import:AD8605ARTZ")
      (libsource (lib "eagle-import") (part "AD8605ARTZ"))
    )
    (comp (ref "IC5")
      (value "MCP170333MB")
      (footprint "eagle-import:SOT89")
      (libsource (lib "eagle-import") (part "MCP1703MB33"))
    )
    (comp (ref "IC6")
      (value "ADUM1402ARWZ")
      (footprint "eagle-import:ADUM1402ARWZ")
      (libsource (lib "eagle-import") (part "ADUM1402ARWZ"))
    )
    (comp (ref "IC7")
      (value "REF3125AIDBZT")
      (footprint "eagle-import:REF3125AIDBZT")
      (libsource (lib "eagle-import") (part "REF3125AIDBZT"))
    )
    (comp (ref "IC8")
      (value "AD8221ARZ")
      (footprint "eagle-import:SO-08")
      (libsource (lib "eagle-import") (part "AD8221ARZ"))
    )
    (comp (ref "IC9")
      (value "TLC2254ID")
      (footprint "eagle-import:TLC2254ID")
      (libsource (lib "eagle-import") (part "TLC2254ID"))
    )
    (comp (ref "IC10")
      (value "AD8605ARTZ")
      (footprint "eagle-import:AD8605ARTZ")
      (libsource (lib "eagle-import") (part "AD8605ARTZ"))
    )
    (comp (ref "IC11")
      (value "AD8221ARZ")
      (footprint "eagle-import:SO-08")
      (libsource (lib "eagle-import") (part "AD8221ARZ"))
    )
    (comp (ref "IC12")
      (value "TLC2254ID")
      (footprint "eagle-import:TLC2254ID")
      (libsource (lib "eagle-import") (part "TLC2254ID"))
    )
    (comp (ref "IC13")
      (value "AD8605ARTZ")
      (footprint "eagle-import:AD8605ARTZ")
      (libsource (lib "eagle-import") (part "AD8605ARTZ"))
    )
    (comp (ref "IC14")
      (value "AD8221ARZ")
      (footprint "eagle-import:SO-08")
      (libsource (lib "eagle-import") (part "AD8221ARZ"))
    )
    (comp (ref "IC15")
      (value "TLC2254ID")
      (footprint "eagle-import:TLC2254ID")
      (libsource (lib "eagle-import") (part "TLC2254ID"))
    )
    (comp (ref "IC16")
      (value "AD8605ARTZ")
      (footprint "eagle-import:AD8605ARTZ")
      (libsource (lib "eagle-import") (part "AD8605ARTZ"))
    )
    (comp (ref "IC17")
      (value "AD8221ARZ")
      (footprint "eagle-import:SO-08")
      (libsource (lib "eagle-import") (part "AD8221ARZ"))
    )
    (comp (ref "IC18")
      (value "TLC2254ID")
      (footprint "eagle-import:TLC2254ID")
      (libsource (lib "eagle-import") (part "TLC2254ID"))
    )
    (comp (ref "IC19")
      (value "AD8605ARTZ")
      (footprint "eagle-import:AD8605ARTZ")
      (libsource (lib "eagle-import") (part "AD8605ARTZ"))
    )
    (comp (ref "IC20")
      (value "AD8221ARZ")
      (footprint "eagle-import:SO-08")
      (libsource (lib "eagle-import") (part "AD8221ARZ"))
    )
    (comp (ref "IC21")
      (value "TLC2254ID")
      (footprint "eagle-import:TLC2254ID")
      (libsource (lib "eagle-import") (part "TLC2254ID"))
    )
    (comp (ref "IC22")
      (value "AD8605ARTZ")
      (footprint "eagle-import:AD8605ARTZ")
      (libsource (lib "eagle-import") (part "AD8605ARTZ"))
    )
    (comp (ref "IC23")
      (value "AD8221ARZ")
      (footprint "eagle-import:SO-08")
      (libsource (lib "eagle-import") (part "AD8221ARZ"))
    )
    (comp (ref "IC24")
      (value "TLC2254ID")
      (footprint "eagle-import:TLC2254ID")
      (libsource (lib "eagle-import") (part "TLC2254ID"))
    )
    (comp (ref "IC25")
      (value "AD8605ARTZ")
      (footprint "eagle-import:AD8605ARTZ")
      (libsource (lib "eagle-import") (part "AD8605ARTZ"))
    )
    (comp (ref "IC26")
      (value "AD8221ARZ")
      (footprint "eagle-import:SO-08")
      (libsource (lib "eagle-import") (part "AD8221ARZ"))
    )
    (comp (ref "IC27")
      (value "TLC2254ID")
      (footprint "eagle-import:TLC2254ID")
      (libsource (lib "eagle-import") (part "TLC2254ID"))
    )
    (comp (ref "IC28")
      (value "AD8605ARTZ")
      (footprint "eagle-import:AD8605ARTZ")
      (libsource (lib "eagle-import") (part "AD8605ARTZ"))
    )
    (comp (ref "IN1")
      (value "IN1")
      (footprint "eagle-import:1X04")
      (libsource (lib "eagle-import") (part "PINHD-1X4"))
    )
    (comp (ref "IN2")
      (value "IN2")
      (footprint "eagle-import:1X04")
      (libsource (lib "eagle-import") (part "PINHD-1X4"))
    )
    (comp (ref "IN3")
      (value "IN3")
      (footprint "eagle-import:1X04")
      (libsource (lib "eagle-import") (part "PINHD-1X4"))
    )
    (comp (ref "IN4")
      (value "IN4")
      (footprint "eagle-import:1X04")
      (libsource (lib "eagle-import") (part "PINHD-1X4"))
    )
    (comp (ref "IN5")
      (value "IN5")
      (footprint "eagle-import:1X04")
      (libsource (lib "eagle-import") (part "PINHD-1X4"))
    )
    (comp (ref "IN6")
      (value "IN6")
      (footprint "eagle-import:1X04")
      (libsource (lib "eagle-import") (part "PINHD-1X4"))
    )
    (comp (ref "IN7")
      (value "IN7")
      (footprint "eagle-import:1X04")
      (libsource (lib "eagle-import") (part "PINHD-1X4"))
    )
    (comp (ref "IN8")
      (value "IN8")
      (footprint "eagle-import:1X04")
      (libsource (lib "eagle-import") (part "PINHD-1X4"))
    )
    (comp (ref "INT")
      (value "INT")
      (footprint "eagle-import:1X08")
      (libsource (lib "eagle-import") (part "PINHD-1X8"))
    )
    (comp (ref "L1")
      (value "100uH")
      (footprint "eagle-import:L4532P")
      (libsource (lib "eagle-import") (part "L-USL4532P"))
    )
    (comp (ref "L2")
      (value "100uH")
      (footprint "eagle-import:L4532P")
      (libsource (lib "eagle-import") (part "L-USL4532P"))
    )
    (comp (ref "Q1")
      (value "8MHz")
      (footprint "eagle-import:HC49U-V")
      (libsource (lib "eagle-import") (part "CRYSTALHC49U-V"))
    )
    (comp (ref "R1")
      (value "2K2")
      (footprint "eagle-import:R0805")
      (libsource (lib "eagle-import") (part "R-EU_R0805"))
    )
    (comp (ref "R2")
      (value "2K2")
      (footprint "eagle-import:R0805")
      (libsource (lib "eagle-import") (part "R-EU_R0805"))
    )
    (comp (ref "R3")
      (value "100")
      (footprint "eagle-import:R0805")
      (libsource (lib "eagle-import") (part "R-EU_R0805"))
    )
    (comp (ref "R4")
      (value "100")
      (footprint "eagle-import:R0805")
      (libsource (lib "eagle-import") (part "R-EU_R0805"))
    )
    (comp (ref "R5")
      (value "2K2")
      (footprint "eagle-import:R0805")
      (libsource (lib "eagle-import") (part "R-EU_R0805"))
    )
    (comp (ref "R6")
      (value "2K2")
      (footprint "eagle-import:R0805")
      (libsource (lib "eagle-import") (part "R-EU_R0805"))
    )
    (comp (ref "R7")
      (value "2K")
      (footprint "eagle-import:R0805")
      (libsource (lib "eagle-import") (part "R-EU_R0805"))
    )
    (comp (ref "R8")
      (value "100K")
      (footprint "eagle-import:R0805")
      (libsource (lib "eagle-import") (part "R-EU_R0805"))
    )
    (comp (ref "R9")
      (value "100K")
      (footprint "eagle-import:R0805")
      (libsource (lib "eagle-import") (part "R-EU_R0805"))
    )
    (comp (ref "R10")
      (value "100K")
      (footprint "eagle-import:R0805")
      (libsource (lib "eagle-import") (part "R-EU_R0805"))
    )
    (comp (ref "R11")
      (value "910K")
      (footprint "eagle-import:R0805")
      (libsource (lib "eagle-import") (part "R-EU_R0805"))
    )
    (comp (ref "R12")
      (value "680K")
      (footprint "eagle-import:R0805")
      (libsource (lib "eagle-import") (part "R-EU_R0805"))
    )
    (comp (ref "R13")
      (value "100K")
      (footprint "eagle-import:R0805")
      (libsource (lib "eagle-import") (part "R-EU_R0805"))
    )
    (comp (ref "R14")
      (value "100")
      (footprint "eagle-import:R0805")
      (libsource (lib "eagle-import") (part "R-EU_R0805"))
    )
    (comp (ref "R15")
      (value "100")
      (footprint "eagle-import:R0805")
      (libsource (lib "eagle-import") (part "R-EU_R0805"))
    )
    (comp (ref "R16")
      (value "100")
      (footprint "eagle-import:R0805")
      (libsource (lib "eagle-import") (part "R-EU_R0805"))
    )
    (comp (ref "R17")
      (value "100")
      (footprint "eagle-import:R0805")
      (libsource (lib "eagle-import") (part "R-EU_R0805"))
    )
    (comp (ref "R18")
      (value "100")
      (footprint "eagle-import:R0805")
      (libsource (lib "eagle-import") (part "R-EU_R0805"))
    )
    (comp (ref "R19")
      (value "100K")
      (footprint "eagle-import:R0805")
      (libsource (lib "eagle-import") (part "R-EU_R0805"))
    )
    (comp (ref "R20")
      (value "100K")
      (footprint "eagle-import:R0805")
      (libsource (lib "eagle-import") (part "R-EU_R0805"))
    )
    (comp (ref "R21")
      (value "100K")
      (footprint "eagle-import:R0805")
      (libsource (lib "eagle-import") (part "R-EU_R0805"))
    )
    (comp (ref "R22")
      (value "1K")
      (footprint "eagle-import:R0805")
      (libsource (lib "eagle-import") (part "R-EU_R0805"))
    )
    (comp (ref "R23")
      (value "100K")
      (footprint "eagle-import:R0805")
      (libsource (lib "eagle-import") (part "R-EU_R0805"))
    )
    (comp (ref "R24")
      (value "2K2")
      (footprint "eagle-import:R0805")
      (libsource (lib "eagle-import") (part "R-EU_R0805"))
    )
    (comp (ref "R25")
      (value "1K")
      (footprint "eagle-import:R0805")
      (libsource (lib "eagle-import") (part "R-EU_R0805"))
    )
    (comp (ref "R26")
      (value "2K2")
      (footprint "eagle-import:R0805")
      (libsource (lib "eagle-import") (part "R-EU_R0805"))
    )
    (comp (ref "R27")
      (value "100")
      (footprint "eagle-import:R0805")
      (libsource (lib "eagle-import") (part "R-EU_R0805"))
    )
    (comp (ref "R28")
      (value "100")
      (footprint "eagle-import:R0805")
      (libsource (lib "eagle-import") (part "R-EU_R0805"))
    )
    (comp (ref "R29")
      (value "2K2")
      (footprint "eagle-import:R0805")
      (libsource (lib "eagle-import") (part "R-EU_R0805"))
    )
    (comp (ref "R30")
      (value "2K2")
      (footprint "eagle-import:R0805")
      (libsource (lib "eagle-import") (part "R-EU_R0805"))
    )
    (comp (ref "R31")
      (value "2K")
      (footprint "eagle-import:R0805")
      (libsource (lib "eagle-import") (part "R-EU_R0805"))
    )
    (comp (ref "R32")
      (value "100K")
      (footprint "eagle-import:R0805")
      (libsource (lib "eagle-import") (part "R-EU_R0805"))
    )
    (comp (ref "R33")
      (value "100K")
      (footprint "eagle-import:R0805")
      (libsource (lib "eagle-import") (part "R-EU_R0805"))
    )
    (comp (ref "R34")
      (value "100K")
      (footprint "eagle-import:R0805")
      (libsource (lib "eagle-import") (part "R-EU_R0805"))
    )
    (comp (ref "R35")
      (value "910K")
      (footprint "eagle-import:R0805")
      (libsource (lib "eagle-import") (part "R-EU_R0805"))
    )
    (comp (ref "R36")
      (value "680K")
      (footprint "eagle-import:R0805")
      (libsource (lib "eagle-import") (part "R-EU_R0805"))
    )
    (comp (ref "R37")
      (value "100K")
      (footprint "eagle-import:R0805")
      (libsource (lib "eagle-import") (part "R-EU_R0805"))
    )
    (comp (ref "R38")
      (value "100K")
      (footprint "eagle-import:R0805")
      (libsource (lib "eagle-import") (part "R-EU_R0805"))
    )
    (comp (ref "R39")
      (value "1K")
      (footprint "eagle-import:R0805")
      (libsource (lib "eagle-import") (part "R-EU_R0805"))
    )
    (comp (ref "R40")
      (value "1K")
      (footprint "eagle-import:R0805")
      (libsource (lib "eagle-import") (part "R-EU_R0805"))
    )
    (comp (ref "R41")
      (value "100K")
      (footprint "eagle-import:R0805")
      (libsource (lib "eagle-import") (part "R-EU_R0805"))
    )
    (comp (ref "R42")
      (value "100K")
      (footprint "eagle-import:R0805")
      (libsource (lib "eagle-import") (part "R-EU_R0805"))
    )
    (comp (ref "R43")
      (value "100K")
      (footprint "eagle-import:R0805")
      (libsource (lib "eagle-import") (part "R-EU_R0805"))
    )
    (comp (ref "R44")
      (value "100")
      (footprint "eagle-import:R0805")
      (libsource (lib "eagle-import") (part "R-EU_R0805"))
    )
    (comp (ref "R45")
      (value "2K2")
      (footprint "eagle-import:R0805")
      (libsource (lib "eagle-import") (part "R-EU_R0805"))
    )
    (comp (ref "R46")
      (value "2K2")
      (footprint "eagle-import:R0805")
      (libsource (lib "eagle-import") (part "R-EU_R0805"))
    )
    (comp (ref "R47")
      (value "100")
      (footprint "eagle-import:R0805")
      (libsource (lib "eagle-import") (part "R-EU_R0805"))
    )
    (comp (ref "R48")
      (value "100")
      (footprint "eagle-import:R0805")
      (libsource (lib "eagle-import") (part "R-EU_R0805"))
    )
    (comp (ref "R49")
      (value "2K2")
      (footprint "eagle-import:R0805")
      (libsource (lib "eagle-import") (part "R-EU_R0805"))
    )
    (comp (ref "R50")
      (value "2K2")
      (footprint "eagle-import:R0805")
      (libsource (lib "eagle-import") (part "R-EU_R0805"))
    )
    (comp (ref "R51")
      (value "2K")
      (footprint "eagle-import:R0805")
      (libsource (lib "eagle-import") (part "R-EU_R0805"))
    )
    (comp (ref "R52")
      (value "100K")
      (footprint "eagle-import:R0805")
      (libsource (lib "eagle-import") (part "R-EU_R0805"))
    )
    (comp (ref "R53")
      (value "100K")
      (footprint "eagle-import:R0805")
      (libsource (lib "eagle-import") (part "R-EU_R0805"))
    )
    (comp (ref "R54")
      (value "100K")
      (footprint "eagle-import:R0805")
      (libsource (lib "eagle-import") (part "R-EU_R0805"))
    )
    (comp (ref "R55")
      (value "910K")
      (footprint "eagle-import:R0805")
      (libsource (lib "eagle-import") (part "R-EU_R0805"))
    )
    (comp (ref "R56")
      (value "680K")
      (footprint "eagle-import:R0805")
      (libsource (lib "eagle-import") (part "R-EU_R0805"))
    )
    (comp (ref "R57")
      (value "100K")
      (footprint "eagle-import:R0805")
      (libsource (lib "eagle-import") (part "R-EU_R0805"))
    )
    (comp (ref "R58")
      (value "100K")
      (footprint "eagle-import:R0805")
      (libsource (lib "eagle-import") (part "R-EU_R0805"))
    )
    (comp (ref "R59")
      (value "1K")
      (footprint "eagle-import:R0805")
      (libsource (lib "eagle-import") (part "R-EU_R0805"))
    )
    (comp (ref "R60")
      (value "1K")
      (footprint "eagle-import:R0805")
      (libsource (lib "eagle-import") (part "R-EU_R0805"))
    )
    (comp (ref "R61")
      (value "100K")
      (footprint "eagle-import:R0805")
      (libsource (lib "eagle-import") (part "R-EU_R0805"))
    )
    (comp (ref "R62")
      (value "100K")
      (footprint "eagle-import:R0805")
      (libsource (lib "eagle-import") (part "R-EU_R0805"))
    )
    (comp (ref "R63")
      (value "100K")
      (footprint "eagle-import:R0805")
      (libsource (lib "eagle-import") (part "R-EU_R0805"))
    )
    (comp (ref "R64")
      (value "100")
      (footprint "eagle-import:R0805")
      (libsource (lib "eagle-import") (part "R-EU_R0805"))
    )
    (comp (ref "R65")
      (value "2K2")
      (footprint "eagle-import:R0805")
      (libsource (lib "eagle-import") (part "R-EU_R0805"))
    )
    (comp (ref "R66")
      (value "2K2")
      (footprint "eagle-import:R0805")
      (libsource (lib "eagle-import") (part "R-EU_R0805"))
    )
    (comp (ref "R67")
      (value "100")
      (footprint "eagle-import:R0805")
      (libsource (lib "eagle-import") (part "R-EU_R0805"))
    )
    (comp (ref "R68")
      (value "100")
      (footprint "eagle-import:R0805")
      (libsource (lib "eagle-import") (part "R-EU_R0805"))
    )
    (comp (ref "R69")
      (value "2K2")
      (footprint "eagle-import:R0805")
      (libsource (lib "eagle-import") (part "R-EU_R0805"))
    )
    (comp (ref "R70")
      (value "2K2")
      (footprint "eagle-import:R0805")
      (libsource (lib "eagle-import") (part "R-EU_R0805"))
    )
    (comp (ref "R71")
      (value "2K")
      (footprint "eagle-import:R0805")
      (libsource (lib "eagle-import") (part "R-EU_R0805"))
    )
    (comp (ref "R72")
      (value "100K")
      (footprint "eagle-import:R0805")
      (libsource (lib "eagle-import") (part "R-EU_R0805"))
    )
    (comp (ref "R73")
      (value "100K")
      (footprint "eagle-import:R0805")
      (libsource (lib "eagle-import") (part "R-EU_R0805"))
    )
    (comp (ref "R74")
      (value "100K")
      (footprint "eagle-import:R0805")
      (libsource (lib "eagle-import") (part "R-EU_R0805"))
    )
    (comp (ref "R75")
      (value "910K")
      (footprint "eagle-import:R0805")
      (libsource (lib "eagle-import") (part "R-EU_R0805"))
    )
    (comp (ref "R76")
      (value "680K")
      (footprint "eagle-import:R0805")
      (libsource (lib "eagle-import") (part "R-EU_R0805"))
    )
    (comp (ref "R77")
      (value "100K")
      (footprint "eagle-import:R0805")
      (libsource (lib "eagle-import") (part "R-EU_R0805"))
    )
    (comp (ref "R78")
      (value "100K")
      (footprint "eagle-import:R0805")
      (libsource (lib "eagle-import") (part "R-EU_R0805"))
    )
    (comp (ref "R79")
      (value "1K")
      (footprint "eagle-import:R0805")
      (libsource (lib "eagle-import") (part "R-EU_R0805"))
    )
    (comp (ref "R80")
      (value "1K")
      (footprint "eagle-import:R0805")
      (libsource (lib "eagle-import") (part "R-EU_R0805"))
    )
    (comp (ref "R81")
      (value "100K")
      (footprint "eagle-import:R0805")
      (libsource (lib "eagle-import") (part "R-EU_R0805"))
    )
    (comp (ref "R82")
      (value "100K")
      (footprint "eagle-import:R0805")
      (libsource (lib "eagle-import") (part "R-EU_R0805"))
    )
    (comp (ref "R83")
      (value "100K")
      (footprint "eagle-import:R0805")
      (libsource (lib "eagle-import") (part "R-EU_R0805"))
    )
    (comp (ref "R84")
      (value "100")
      (footprint "eagle-import:R0805")
      (libsource (lib "eagle-import") (part "R-EU_R0805"))
    )
    (comp (ref "R85")
      (value "2K2")
      (footprint "eagle-import:R0805")
      (libsource (lib "eagle-import") (part "R-EU_R0805"))
    )
    (comp (ref "R86")
      (value "2K2")
      (footprint "eagle-import:R0805")
      (libsource (lib "eagle-import") (part "R-EU_R0805"))
    )
    (comp (ref "R87")
      (value "100")
      (footprint "eagle-import:R0805")
      (libsource (lib "eagle-import") (part "R-EU_R0805"))
    )
    (comp (ref "R88")
      (value "100")
      (footprint "eagle-import:R0805")
      (libsource (lib "eagle-import") (part "R-EU_R0805"))
    )
    (comp (ref "R89")
      (value "2K2")
      (footprint "eagle-import:R0805")
      (libsource (lib "eagle-import") (part "R-EU_R0805"))
    )
    (comp (ref "R90")
      (value "2K2")
      (footprint "eagle-import:R0805")
      (libsource (lib "eagle-import") (part "R-EU_R0805"))
    )
    (comp (ref "R91")
      (value "2K")
      (footprint "eagle-import:R0805")
      (libsource (lib "eagle-import") (part "R-EU_R0805"))
    )
    (comp (ref "R92")
      (value "100K")
      (footprint "eagle-import:R0805")
      (libsource (lib "eagle-import") (part "R-EU_R0805"))
    )
    (comp (ref "R93")
      (value "100K")
      (footprint "eagle-import:R0805")
      (libsource (lib "eagle-import") (part "R-EU_R0805"))
    )
    (comp (ref "R94")
      (value "100K")
      (footprint "eagle-import:R0805")
      (libsource (lib "eagle-import") (part "R-EU_R0805"))
    )
    (comp (ref "R95")
      (value "910K")
      (footprint "eagle-import:R0805")
      (libsource (lib "eagle-import") (part "R-EU_R0805"))
    )
    (comp (ref "R96")
      (value "680K")
      (footprint "eagle-import:R0805")
      (libsource (lib "eagle-import") (part "R-EU_R0805"))
    )
    (comp (ref "R97")
      (value "100K")
      (footprint "eagle-import:R0805")
      (libsource (lib "eagle-import") (part "R-EU_R0805"))
    )
    (comp (ref "R98")
      (value "100K")
      (footprint "eagle-import:R0805")
      (libsource (lib "eagle-import") (part "R-EU_R0805"))
    )
    (comp (ref "R99")
      (value "1K")
      (footprint "eagle-import:R0805")
      (libsource (lib "eagle-import") (part "R-EU_R0805"))
    )
    (comp (ref "R100")
      (value "1K")
      (footprint "eagle-import:R0805")
      (libsource (lib "eagle-import") (part "R-EU_R0805"))
    )
    (comp (ref "R101")
      (value "100K")
      (footprint "eagle-import:R0805")
      (libsource (lib "eagle-import") (part "R-EU_R0805"))
    )
    (comp (ref "R102")
      (value "100K")
      (footprint "eagle-import:R0805")
      (libsource (lib "eagle-import") (part "R-EU_R0805"))
    )
    (comp (ref "R103")
      (value "100K")
      (footprint "eagle-import:R0805")
      (libsource (lib "eagle-import") (part "R-EU_R0805"))
    )
    (comp (ref "R104")
      (value "100")
      (footprint "eagle-import:R0805")
      (libsource (lib "eagle-import") (part "R-EU_R0805"))
    )
    (comp (ref "R105")
      (value "2K2")
      (footprint "eagle-import:R0805")
      (libsource (lib "eagle-import") (part "R-EU_R0805"))
    )
    (comp (ref "R106")
      (value "2K2")
      (footprint "eagle-import:R0805")
      (libsource (lib "eagle-import") (part "R-EU_R0805"))
    )
    (comp (ref "R107")
      (value "100")
      (footprint "eagle-import:R0805")
      (libsource (lib "eagle-import") (part "R-EU_R0805"))
    )
    (comp (ref "R108")
      (value "100")
      (footprint "eagle-import:R0805")
      (libsource (lib "eagle-import") (part "R-EU_R0805"))
    )
    (comp (ref "R109")
      (value "2K2")
      (footprint "eagle-import:R0805")
      (libsource (lib "eagle-import") (part "R-EU_R0805"))
    )
    (comp (ref "R110")
      (value "2K2")
      (footprint "eagle-import:R0805")
      (libsource (lib "eagle-import") (part "R-EU_R0805"))
    )
    (comp (ref "R111")
      (value "2K")
      (footprint "eagle-import:R0805")
      (libsource (lib "eagle-import") (part "R-EU_R0805"))
    )
    (comp (ref "R112")
      (value "100K")
      (footprint "eagle-import:R0805")
      (libsource (lib "eagle-import") (part "R-EU_R0805"))
    )
    (comp (ref "R113")
      (value "100K")
      (footprint "eagle-import:R0805")
      (libsource (lib "eagle-import") (part "R-EU_R0805"))
    )
    (comp (ref "R114")
      (value "100K")
      (footprint "eagle-import:R0805")
      (libsource (lib "eagle-import") (part "R-EU_R0805"))
    )
    (comp (ref "R115")
      (value "910K")
      (footprint "eagle-import:R0805")
      (libsource (lib "eagle-import") (part "R-EU_R0805"))
    )
    (comp (ref "R116")
      (value "680K")
      (footprint "eagle-import:R0805")
      (libsource (lib "eagle-import") (part "R-EU_R0805"))
    )
    (comp (ref "R117")
      (value "100K")
      (footprint "eagle-import:R0805")
      (libsource (lib "eagle-import") (part "R-EU_R0805"))
    )
    (comp (ref "R118")
      (value "100K")
      (footprint "eagle-import:R0805")
      (libsource (lib "eagle-import") (part "R-EU_R0805"))
    )
    (comp (ref "R119")
      (value "1K")
      (footprint "eagle-import:R0805")
      (libsource (lib "eagle-import") (part "R-EU_R0805"))
    )
    (comp (ref "R120")
      (value "1K")
      (footprint "eagle-import:R0805")
      (libsource (lib "eagle-import") (part "R-EU_R0805"))
    )
    (comp (ref "R121")
      (value "100K")
      (footprint "eagle-import:R0805")
      (libsource (lib "eagle-import") (part "R-EU_R0805"))
    )
    (comp (ref "R122")
      (value "100K")
      (footprint "eagle-import:R0805")
      (libsource (lib "eagle-import") (part "R-EU_R0805"))
    )
    (comp (ref "R123")
      (value "100K")
      (footprint "eagle-import:R0805")
      (libsource (lib "eagle-import") (part "R-EU_R0805"))
    )
    (comp (ref "R124")
      (value "100")
      (footprint "eagle-import:R0805")
      (libsource (lib "eagle-import") (part "R-EU_R0805"))
    )
    (comp (ref "R125")
      (value "2K2")
      (footprint "eagle-import:R0805")
      (libsource (lib "eagle-import") (part "R-EU_R0805"))
    )
    (comp (ref "R126")
      (value "2K2")
      (footprint "eagle-import:R0805")
      (libsource (lib "eagle-import") (part "R-EU_R0805"))
    )
    (comp (ref "R127")
      (value "100")
      (footprint "eagle-import:R0805")
      (libsource (lib "eagle-import") (part "R-EU_R0805"))
    )
    (comp (ref "R128")
      (value "100")
      (footprint "eagle-import:R0805")
      (libsource (lib "eagle-import") (part "R-EU_R0805"))
    )
    (comp (ref "R129")
      (value "2K2")
      (footprint "eagle-import:R0805")
      (libsource (lib "eagle-import") (part "R-EU_R0805"))
    )
    (comp (ref "R130")
      (value "2K2")
      (footprint "eagle-import:R0805")
      (libsource (lib "eagle-import") (part "R-EU_R0805"))
    )
    (comp (ref "R131")
      (value "2K")
      (footprint "eagle-import:R0805")
      (libsource (lib "eagle-import") (part "R-EU_R0805"))
    )
    (comp (ref "R132")
      (value "100K")
      (footprint "eagle-import:R0805")
      (libsource (lib "eagle-import") (part "R-EU_R0805"))
    )
    (comp (ref "R133")
      (value "100K")
      (footprint "eagle-import:R0805")
      (libsource (lib "eagle-import") (part "R-EU_R0805"))
    )
    (comp (ref "R134")
      (value "100K")
      (footprint "eagle-import:R0805")
      (libsource (lib "eagle-import") (part "R-EU_R0805"))
    )
    (comp (ref "R135")
      (value "910K")
      (footprint "eagle-import:R0805")
      (libsource (lib "eagle-import") (part "R-EU_R0805"))
    )
    (comp (ref "R136")
      (value "680K")
      (footprint "eagle-import:R0805")
      (libsource (lib "eagle-import") (part "R-EU_R0805"))
    )
    (comp (ref "R137")
      (value "100K")
      (footprint "eagle-import:R0805")
      (libsource (lib "eagle-import") (part "R-EU_R0805"))
    )
    (comp (ref "R138")
      (value "100K")
      (footprint "eagle-import:R0805")
      (libsource (lib "eagle-import") (part "R-EU_R0805"))
    )
    (comp (ref "R139")
      (value "1K")
      (footprint "eagle-import:R0805")
      (libsource (lib "eagle-import") (part "R-EU_R0805"))
    )
    (comp (ref "R140")
      (value "1K")
      (footprint "eagle-import:R0805")
      (libsource (lib "eagle-import") (part "R-EU_R0805"))
    )
    (comp (ref "R141")
      (value "100K")
      (footprint "eagle-import:R0805")
      (libsource (lib "eagle-import") (part "R-EU_R0805"))
    )
    (comp (ref "R142")
      (value "100K")
      (footprint "eagle-import:R0805")
      (libsource (lib "eagle-import") (part "R-EU_R0805"))
    )
    (comp (ref "R143")
      (value "100K")
      (footprint "eagle-import:R0805")
      (libsource (lib "eagle-import") (part "R-EU_R0805"))
    )
    (comp (ref "R144")
      (value "100")
      (footprint "eagle-import:R0805")
      (libsource (lib "eagle-import") (part "R-EU_R0805"))
    )
    (comp (ref "R145")
      (value "2K2")
      (footprint "eagle-import:R0805")
      (libsource (lib "eagle-import") (part "R-EU_R0805"))
    )
    (comp (ref "R146")
      (value "2K2")
      (footprint "eagle-import:R0805")
      (libsource (lib "eagle-import") (part "R-EU_R0805"))
    )
    (comp (ref "R147")
      (value "100")
      (footprint "eagle-import:R0805")
      (libsource (lib "eagle-import") (part "R-EU_R0805"))
    )
    (comp (ref "R148")
      (value "100")
      (footprint "eagle-import:R0805")
      (libsource (lib "eagle-import") (part "R-EU_R0805"))
    )
    (comp (ref "R149")
      (value "2K2")
      (footprint "eagle-import:R0805")
      (libsource (lib "eagle-import") (part "R-EU_R0805"))
    )
    (comp (ref "R150")
      (value "2K2")
      (footprint "eagle-import:R0805")
      (libsource (lib "eagle-import") (part "R-EU_R0805"))
    )
    (comp (ref "R151")
      (value "2K")
      (footprint "eagle-import:R0805")
      (libsource (lib "eagle-import") (part "R-EU_R0805"))
    )
    (comp (ref "R152")
      (value "100K")
      (footprint "eagle-import:R0805")
      (libsource (lib "eagle-import") (part "R-EU_R0805"))
    )
    (comp (ref "R153")
      (value "100K")
      (footprint "eagle-import:R0805")
      (libsource (lib "eagle-import") (part "R-EU_R0805"))
    )
    (comp (ref "R154")
      (value "100K")
      (footprint "eagle-import:R0805")
      (libsource (lib "eagle-import") (part "R-EU_R0805"))
    )
    (comp (ref "R155")
      (value "910K")
      (footprint "eagle-import:R0805")
      (libsource (lib "eagle-import") (part "R-EU_R0805"))
    )
    (comp (ref "R156")
      (value "680K")
      (footprint "eagle-import:R0805")
      (libsource (lib "eagle-import") (part "R-EU_R0805"))
    )
    (comp (ref "R157")
      (value "100K")
      (footprint "eagle-import:R0805")
      (libsource (lib "eagle-import") (part "R-EU_R0805"))
    )
    (comp (ref "R158")
      (value "100K")
      (footprint "eagle-import:R0805")
      (libsource (lib "eagle-import") (part "R-EU_R0805"))
    )
    (comp (ref "R159")
      (value "1K")
      (footprint "eagle-import:R0805")
      (libsource (lib "eagle-import") (part "R-EU_R0805"))
    )
    (comp (ref "R160")
      (value "1K")
      (footprint "eagle-import:R0805")
      (libsource (lib "eagle-import") (part "R-EU_R0805"))
    )
    (comp (ref "R161")
      (value "100K")
      (footprint "eagle-import:R0805")
      (libsource (lib "eagle-import") (part "R-EU_R0805"))
    )
    (comp (ref "R162")
      (value "100K")
      (footprint "eagle-import:R0805")
      (libsource (lib "eagle-import") (part "R-EU_R0805"))
    )
    (comp (ref "R163")
      (value "100K")
      (footprint "eagle-import:R0805")
      (libsource (lib "eagle-import") (part "R-EU_R0805"))
    )
    (comp (ref "R164")
      (value "100")
      (footprint "eagle-import:R0805")
      (libsource (lib "eagle-import") (part "R-EU_R0805"))
    )
  )
  (nets
    (net (code "1") (name "+3.3V") (class "Default")
      (node (ref "C17") (pin "1") (pinfunction "1_1") (pintype "passive"))
      (node (ref "C21") (pin "+") (pinfunction "+_+") (pintype "passive"))
      (node (ref "C44") (pin "1") (pinfunction "1_1") (pintype "passive"))
      (node (ref "C7") (pin "1") (pinfunction "1_1") (pintype "passive"))
      (node (ref "IC3") (pin "14") (pinfunction "SYNC/PDWN_14") (pintype "bidirectional"))
      (node (ref "IC3") (pin "15") (pinfunction "RESET_15") (pintype "bidirectional"))
      (node (ref "IC3") (pin "16") (pinfunction "DVDD_16") (pintype "bidirectional"))
      (node (ref "IC5") (pin "3") (pinfunction "VO_3") (pintype "passive"))
      (node (ref "IC6") (pin "1") (pinfunction "VDD1_1") (pintype "bidirectional"))
      (node (ref "IC6") (pin "7") (pinfunction "VE1_7") (pintype "bidirectional"))
    )
    (net (code "2") (name "+5VA") (class "Default")
      (node (ref "C107") (pin "2") (pinfunction "2_2") (pintype "passive"))
      (node (ref "C108") (pin "1") (pinfunction "1_1") (pintype "passive"))
      (node (ref "C112") (pin "1") (pinfunction "1_1") (pintype "passive"))
      (node (ref "C121") (pin "2") (pinfunction "2_2") (pintype "passive"))
      (node (ref "C122") (pin "1") (pinfunction "1_1") (pintype "passive"))
      (node (ref "C126") (pin "1") (pinfunction "1_1") (pintype "passive"))
      (node (ref "C15") (pin "1") (pinfunction "1_1") (pintype "passive"))
      (node (ref "C26") (pin "1") (pinfunction "1_1") (pintype "passive"))
      (node (ref "C27") (pin "+") (pinfunction "+_+") (pintype "passive"))
      (node (ref "C34") (pin "2") (pinfunction "2_2") (pintype "passive"))
      (node (ref "C35") (pin "1") (pinfunction "1_1") (pintype "passive"))
      (node (ref "C39") (pin "1") (pinfunction "1_1") (pintype "passive"))
      (node (ref "C49") (pin "2") (pinfunction "2_2") (pintype "passive"))
      (node (ref "C5") (pin "2") (pinfunction "2_2") (pintype "passive"))
      (node (ref "C50") (pin "1") (pinfunction "1_1") (pintype "passive"))
      (node (ref "C55") (pin "1") (pinfunction "1_1") (pintype "passive"))
      (node (ref "C6") (pin "1") (pinfunction "1_1") (pintype "passive"))
      (node (ref "C65") (pin "2") (pinfunction "2_2") (pintype "passive"))
      (node (ref "C66") (pin "1") (pinfunction "1_1") (pintype "passive"))
      (node (ref "C70") (pin "1") (pinfunction "1_1") (pintype "passive"))
      (node (ref "C79") (pin "2") (pinfunction "2_2") (pintype "passive"))
      (node (ref "C8") (pin "1") (pinfunction "1_1") (pintype "passive"))
      (node (ref "C80") (pin "1") (pinfunction "1_1") (pintype "passive"))
      (node (ref "C84") (pin "1") (pinfunction "1_1") (pintype "passive"))
      (node (ref "C93") (pin "2") (pinfunction "2_2") (pintype "passive"))
      (node (ref "C94") (pin "1") (pinfunction "1_1") (pintype "passive"))
      (node (ref "C98") (pin "1") (pinfunction "1_1") (pintype "passive"))
      (node (ref "D1") (pin "2") (pinfunction "C_2") (pintype "passive"))
      (node (ref "D10") (pin "2") (pinfunction "C_2") (pintype "passive"))
      (node (ref "D11") (pin "2") (pinfunction "C_2") (pintype "passive"))
      (node (ref "D12") (pin "2") (pinfunction "C_2") (pintype "passive"))
      (node (ref "D13") (pin "2") (pinfunction "C_2") (pintype "passive"))
      (node (ref "D14") (pin "2") (pinfunction "C_2") (pintype "passive"))
      (node (ref "D15") (pin "2") (pinfunction "C_2") (pintype "passive"))
      (node (ref "D16") (pin "2") (pinfunction "C_2") (pintype "passive"))
      (node (ref "D17") (pin "2") (pinfunction "C_2") (pintype "passive"))
      (node (ref "D18") (pin "2") (pinfunction "C_2") (pintype "passive"))
      (node (ref "D19") (pin "2") (pinfunction "C_2") (pintype "passive"))
      (node (ref "D2") (pin "2") (pinfunction "C_2") (pintype "passive"))
      (node (ref "D20") (pin "2") (pinfunction "C_2") (pintype "passive"))
      (node (ref "D21") (pin "2") (pinfunction "C_2") (pintype "passive"))
      (node (ref "D22") (pin "2") (pinfunction "C_2") (pintype "passive"))
      (node (ref "D23") (pin "2") (pinfunction "C_2") (pintype "passive"))
      (node (ref "D24") (pin "2") (pinfunction "C_2") (pintype "passive"))
      (node (ref "D25") (pin "2") (pinfunction "C_2") (pintype "passive"))
      (node (ref "D26") (pin "2") (pinfunction "C_2") (pintype "passive"))
      (node (ref "D27") (pin "2") (pinfunction "C_2") (pintype "passive"))
      (node (ref "D28") (pin "2") (pinfunction "C_2") (pintype "passive"))
      (node (ref "D29") (pin "2") (pinfunction "C_2") (pintype "passive"))
      (node (ref "D3") (pin "2") (pinfunction "C_2") (pintype "passive"))
      (node (ref "D30") (pin "2") (pinfunction "C_2") (pintype "passive"))
      (node (ref "D31") (pin "2") (pinfunction "C_2") (pintype "passive"))
      (node (ref "D32") (pin "2") (pinfunction "C_2") (pintype "passive"))
      (node (ref "D4") (pin "2") (pinfunction "C_2") (pintype "passive"))
      (node (ref "D5") (pin "2") (pinfunction "C_2") (pintype "passive"))
      (node (ref "D6") (pin "2") (pinfunction "C_2") (pintype "passive"))
      (node (ref "D7") (pin "2") (pinfunction "C_2") (pintype "passive"))
      (node (ref "D8") (pin "2") (pinfunction "C_2") (pintype "passive"))
      (node (ref "D9") (pin "2") (pinfunction "C_2") (pintype "passive"))
      (node (ref "IC1") (pin "8") (pinfunction "+VS_8") (pintype "power_in"))
      (node (ref "IC10") (pin "5") (pinfunction "+VS_5") (pintype "power_in"))
      (node (ref "IC11") (pin "8") (pinfunction "+VS_8") (pintype "power_in"))
      (node (ref "IC12") (pin "4") (pinfunction "+VS_4") (pintype "power_in"))
      (node (ref "IC13") (pin "5") (pinfunction "+VS_5") (pintype "power_in"))
      (node (ref "IC14") (pin "8") (pinfunction "+VS_8") (pintype "power_in"))
      (node (ref "IC15") (pin "4") (pinfunction "+VS_4") (pintype "power_in"))
      (node (ref "IC16") (pin "5") (pinfunction "+VS_5") (pintype "power_in"))
      (node (ref "IC17") (pin "8") (pinfunction "+VS_8") (pintype "power_in"))
      (node (ref "IC18") (pin "4") (pinfunction "+VS_4") (pintype "power_in"))
      (node (ref "IC19") (pin "5") (pinfunction "+VS_5") (pintype "power_in"))
      (node (ref "IC2") (pin "4") (pinfunction "+VS_4") (pintype "power_in"))
      (node (ref "IC20") (pin "8") (pinfunction "+VS_8") (pintype "power_in"))
      (node (ref "IC21") (pin "4") (pinfunction "+VS_4") (pintype "power_in"))
      (node (ref "IC22") (pin "5") (pinfunction "+VS_5") (pintype "power_in"))
      (node (ref "IC23") (pin "8") (pinfunction "+VS_8") (pintype "power_in"))
      (node (ref "IC24") (pin "4") (pinfunction "+VS_4") (pintype "power_in"))
      (node (ref "IC25") (pin "5") (pinfunction "+VS_5") (pintype "power_in"))
      (node (ref "IC26") (pin "8") (pinfunction "+VS_8") (pintype "power_in"))
      (node (ref "IC27") (pin "4") (pinfunction "+VS_4") (pintype "power_in"))
      (node (ref "IC28") (pin "5") (pinfunction "+VS_5") (pintype "power_in"))
      (node (ref "IC3") (pin "1") (pinfunction "AVDD_1") (pintype "bidirectional"))
      (node (ref "IC4") (pin "5") (pinfunction "+VS_5") (pintype "power_in"))
      (node (ref "IC7") (pin "1") (pinfunction "VIN_1") (pintype "bidirectional"))
      (node (ref "IC8") (pin "8") (pinfunction "+VS_8") (pintype "power_in"))
      (node (ref "IC9") (pin "4") (pinfunction "+VS_4") (pintype "power_in"))
      (node (ref "L1") (pin "1") (pinfunction "1_1") (pintype "passive"))
    )
    (net (code "3") (name "-5VA") (class "Default")
      (node (ref "C106") (pin "1") (pinfunction "1_1") (pintype "passive"))
      (node (ref "C109") (pin "2") (pinfunction "2_2") (pintype "passive"))
      (node (ref "C11") (pin "2") (pinfunction "2_2") (pintype "passive"))
      (node (ref "C120") (pin "1") (pinfunction "1_1") (pintype "passive"))
      (node (ref "C123") (pin "2") (pinfunction "2_2") (pintype "passive"))
      (node (ref "C28") (pin "2") (pinfunction "2_2") (pintype "passive"))
      (node (ref "C29") (pin "-") (pinfunction "-_-") (pintype "passive"))
      (node (ref "C33") (pin "1") (pinfunction "1_1") (pintype "passive"))
      (node (ref "C36") (pin "2") (pinfunction "2_2") (pintype "passive"))
      (node (ref "C4") (pin "1") (pinfunction "1_1") (pintype "passive"))
      (node (ref "C48") (pin "1") (pinfunction "1_1") (pintype "passive"))
      (node (ref "C51") (pin "2") (pinfunction "2_2") (pintype "passive"))
      (node (ref "C64") (pin "1") (pinfunction "1_1") (pintype "passive"))
      (node (ref "C67") (pin "2") (pinfunction "2_2") (pintype "passive"))
      (node (ref "C78") (pin "1") (pinfunction "1_1") (pintype "passive"))
      (node (ref "C81") (pin "2") (pinfunction "2_2") (pintype "passive"))
      (node (ref "C92") (pin "1") (pinfunction "1_1") (pintype "passive"))
      (node (ref "C95") (pin "2") (pinfunction "2_2") (pintype "passive"))
      (node (ref "D1") (pin "1") (pinfunction "A_1") (pintype "passive"))
      (node (ref "D10") (pin "1") (pinfunction "A_1") (pintype "passive"))
      (node (ref "D11") (pin "1") (pinfunction "A_1") (pintype "passive"))
      (node (ref "D12") (pin "1") (pinfunction "A_1") (pintype "passive"))
      (node (ref "D13") (pin "1") (pinfunction "A_1") (pintype "passive"))
      (node (ref "D14") (pin "1") (pinfunction "A_1") (pintype "passive"))
      (node (ref "D15") (pin "1") (pinfunction "A_1") (pintype "passive"))
      (node (ref "D16") (pin "1") (pinfunction "A_1") (pintype "passive"))
      (node (ref "D17") (pin "1") (pinfunction "A_1") (pintype "passive"))
      (node (ref "D18") (pin "1") (pinfunction "A_1") (pintype "passive"))
      (node (ref "D19") (pin "1") (pinfunction "A_1") (pintype "passive"))
      (node (ref "D2") (pin "1") (pinfunction "A_1") (pintype "passive"))
      (node (ref "D20") (pin "1") (pinfunction "A_1") (pintype "passive"))
      (node (ref "D21") (pin "1") (pinfunction "A_1") (pintype "passive"))
      (node (ref "D22") (pin "1") (pinfunction "A_1") (pintype "passive"))
      (node (ref "D23") (pin "1") (pinfunction "A_1") (pintype "passive"))
      (node (ref "D24") (pin "1") (pinfunction "A_1") (pintype "passive"))
      (node (ref "D25") (pin "1") (pinfunction "A_1") (pintype "passive"))
      (node (ref "D26") (pin "1") (pinfunction "A_1") (pintype "passive"))
      (node (ref "D27") (pin "1") (pinfunction "A_1") (pintype "passive"))
      (node (ref "D28") (pin "1") (pinfunction "A_1") (pintype "passive"))
      (node (ref "D29") (pin "1") (pinfunction "A_1") (pintype "passive"))
      (node (ref "D3") (pin "1") (pinfunction "A_1") (pintype "passive"))
      (node (ref "D30") (pin "1") (pinfunction "A_1") (pintype "passive"))
      (node (ref "D31") (pin "1") (pinfunction "A_1") (pintype "passive"))
      (node (ref "D32") (pin "1") (pinfunction "A_1") (pintype "passive"))
      (node (ref "D4") (pin "1") (pinfunction "A_1") (pintype "passive"))
      (node (ref "D5") (pin "1") (pinfunction "A_1") (pintype "passive"))
      (node (ref "D6") (pin "1") (pinfunction "A_1") (pintype "passive"))
      (node (ref "D7") (pin "1") (pinfunction "A_1") (pintype "passive"))
      (node (ref "D8") (pin "1") (pinfunction "A_1") (pintype "passive"))
      (node (ref "D9") (pin "1") (pinfunction "A_1") (pintype "passive"))
      (node (ref "IC1") (pin "5") (pinfunction "-VS_5") (pintype "power_in"))
      (node (ref "IC11") (pin "5") (pinfunction "-VS_5") (pintype "power_in"))
      (node (ref "IC12") (pin "11") (pinfunction "-VS_11") (pintype "power_in"))
      (node (ref "IC14") (pin "5") (pinfunction "-VS_5") (pintype "power_in"))
      (node (ref "IC15") (pin "11") (pinfunction "-VS_11") (pintype "power_in"))
      (node (ref "IC17") (pin "5") (pinfunction "-VS_5") (pintype "power_in"))
      (node (ref "IC18") (pin "11") (pinfunction "-VS_11") (pintype "power_in"))
      (node (ref "IC2") (pin "11") (pinfunction "-VS_11") (pintype "power_in"))
      (node (ref "IC20") (pin "5") (pinfunction "-VS_5") (pintype "power_in"))
      (node (ref "IC21") (pin "11") (pinfunction "-VS_11") (pintype "power_in"))
      (node (ref "IC23") (pin "5") (pinfunction "-VS_5") (pintype "power_in"))
      (node (ref "IC24") (pin "11") (pinfunction "-VS_11") (pintype "power_in"))
      (node (ref "IC26") (pin "5") (pinfunction "-VS_5") (pintype "power_in"))
      (node (ref "IC27") (pin "11") (pinfunction "-VS_11") (pintype "power_in"))
      (node (ref "IC8") (pin "5") (pinfunction "-VS_5") (pintype "power_in"))
      (node (ref "IC9") (pin "11") (pinfunction "-VS_11") (pintype "power_in"))
      (node (ref "L2") (pin "1") (pinfunction "1_1") (pintype "passive"))
    )
    (net (code "4") (name "GND") (class "Default")
      (node (ref "C10") (pin "2") (pinfunction "2_2") (pintype "passive"))
      (node (ref "C100") (pin "2") (pinfunction "2_2") (pintype "passive"))
      (node (ref "C102") (pin "1") (pinfunction "1_1") (pintype "passive"))
      (node (ref "C104") (pin "2") (pinfunction "2_2") (pintype "passive"))
      (node (ref "C105") (pin "1") (pinfunction "1_1") (pintype "passive"))
      (node (ref "C106") (pin "2") (pinfunction "2_2") (pintype "passive"))
      (node (ref "C107") (pin "1") (pinfunction "1_1") (pintype "passive"))
      (node (ref "C108") (pin "2") (pinfunction "2_2") (pintype "passive"))
      (node (ref "C109") (pin "1") (pinfunction "1_1") (pintype "passive"))
      (node (ref "C11") (pin "1") (pinfunction "1_1") (pintype "passive"))
      (node (ref "C112") (pin "2") (pinfunction "2_2") (pintype "passive"))
      (node (ref "C113") (pin "1") (pinfunction "1_1") (pintype "passive"))
      (node (ref "C114") (pin "2") (pinfunction "2_2") (pintype "passive"))
      (node (ref "C116") (pin "1") (pinfunction "1_1") (pintype "passive"))
      (node (ref "C118") (pin "2") (pinfunction "2_2") (pintype "passive"))
      (node (ref "C119") (pin "1") (pinfunction "1_1") (pintype "passive"))
      (node (ref "C120") (pin "2") (pinfunction "2_2") (pintype "passive"))
      (node (ref "C121") (pin "1") (pinfunction "1_1") (pintype "passive"))
      (node (ref "C122") (pin "2") (pinfunction "2_2") (pintype "passive"))
      (node (ref "C123") (pin "1") (pinfunction "1_1") (pintype "passive"))
      (node (ref "C126") (pin "2") (pinfunction "2_2") (pintype "passive"))
      (node (ref "C127") (pin "1") (pinfunction "1_1") (pintype "passive"))
      (node (ref "C128") (pin "2") (pinfunction "2_2") (pintype "passive"))
      (node (ref "C130") (pin "1") (pinfunction "1_1") (pintype "passive"))
      (node (ref "C14") (pin "2") (pinfunction "2_2") (pintype "passive"))
      (node (ref "C15") (pin "2") (pinfunction "2_2") (pintype "passive"))
      (node (ref "C16") (pin "2") (pinfunction "2_2") (pintype "passive"))
      (node (ref "C17") (pin "2") (pinfunction "2_2") (pintype "passive"))
      (node (ref "C19") (pin "1") (pinfunction "1_1") (pintype "passive"))
      (node (ref "C2") (pin "2") (pinfunction "2_2") (pintype "passive"))
      (node (ref "C20") (pin "-") (pinfunction "-_-") (pintype "passive"))
      (node (ref "C21") (pin "-") (pinfunction "-_-") (pintype "passive"))
      (node (ref "C22") (pin "-") (pinfunction "-_-") (pintype "passive"))
      (node (ref "C23") (pin "+") (pinfunction "+_+") (pintype "passive"))
      (node (ref "C24") (pin "2") (pinfunction "2_2") (pintype "passive"))
      (node (ref "C25") (pin "1") (pinfunction "1_1") (pintype "passive"))
      (node (ref "C26") (pin "2") (pinfunction "2_2") (pintype "passive"))
      (node (ref "C27") (pin "-") (pinfunction "-_-") (pintype "passive"))
      (node (ref "C28") (pin "1") (pinfunction "1_1") (pintype "passive"))
      (node (ref "C29") (pin "+") (pinfunction "+_+") (pintype "passive"))
      (node (ref "C3") (pin "1") (pinfunction "1_1") (pintype "passive"))
      (node (ref "C31") (pin "2") (pinfunction "2_2") (pintype "passive"))
      (node (ref "C32") (pin "1") (pinfunction "1_1") (pintype "passive"))
      (node (ref "C33") (pin "2") (pinfunction "2_2") (pintype "passive"))
      (node (ref "C34") (pin "1") (pinfunction "1_1") (pintype "passive"))
      (node (ref "C35") (pin "2") (pinfunction "2_2") (pintype "passive"))
      (node (ref "C36") (pin "1") (pinfunction "1_1") (pintype "passive"))
      (node (ref "C39") (pin "2") (pinfunction "2_2") (pintype "passive"))
      (node (ref "C4") (pin "2") (pinfunction "2_2") (pintype "passive"))
      (node (ref "C40") (pin "1") (pinfunction "1_1") (pintype "passive"))
      (node (ref "C41") (pin "2") (pinfunction "2_2") (pintype "passive"))
      (node (ref "C43") (pin "1") (pinfunction "1_1") (pintype "passive"))
      (node (ref "C44") (pin "2") (pinfunction "2_2") (pintype "passive"))
      (node (ref "C46") (pin "2") (pinfunction "2_2") (pintype "passive"))
      (node (ref "C47") (pin "1") (pinfunction "1_1") (pintype "passive"))
      (node (ref "C48") (pin "2") (pinfunction "2_2") (pintype "passive"))
      (node (ref "C49") (pin "1") (pinfunction "1_1") (pintype "passive"))
      (node (ref "C5") (pin "1") (pinfunction "1_1") (pintype "passive"))
      (node (ref "C50") (pin "2") (pinfunction "2_2") (pintype "passive"))
      (node (ref "C51") (pin "1") (pinfunction "1_1") (pintype "passive"))
      (node (ref "C52") (pin "1") (pinfunction "1_1") (pintype "passive"))
      (node (ref "C55") (pin "2") (pinfunction "2_2") (pintype "passive"))
      (node (ref "C57") (pin "1") (pinfunction "1_1") (pintype "passive"))
      (node (ref "C58") (pin "2") (pinfunction "2_2") (pintype "passive"))
      (node (ref "C6") (pin "2") (pinfunction "2_2") (pintype "passive"))
      (node (ref "C60") (pin "1") (pinfunction "1_1") (pintype "passive"))
      (node (ref "C62") (pin "2") (pinfunction "2_2") (pintype "passive"))
      (node (ref "C63") (pin "1") (pinfunction "1_1") (pintype "passive"))
      (node (ref "C64") (pin "2") (pinfunction "2_2") (pintype "passive"))
      (node (ref "C65") (pin "1") (pinfunction "1_1") (pintype "passive"))
      (node (ref "C66") (pin "2") (pinfunction "2_2") (pintype "passive"))
      (node (ref "C67") (pin "1") (pinfunction "1_1") (pintype "passive"))
      (node (ref "C7") (pin "2") (pinfunction "2_2") (pintype "passive"))
      (node (ref "C70") (pin "2") (pinfunction "2_2") (pintype "passive"))
      (node (ref "C71") (pin "1") (pinfunction "1_1") (pintype "passive"))
      (node (ref "C72") (pin "2") (pinfunction "2_2") (pintype "passive"))
      (node (ref "C74") (pin "1") (pinfunction "1_1") (pintype "passive"))
      (node (ref "C76") (pin "2") (pinfunction "2_2") (pintype "passive"))
      (node (ref "C77") (pin "1") (pinfunction "1_1") (pintype "passive"))
      (node (ref "C78") (pin "2") (pinfunction "2_2") (pintype "passive"))
      (node (ref "C79") (pin "1") (pinfunction "1_1") (pintype "passive"))
      (node (ref "C8") (pin "2") (pinfunction "2_2") (pintype "passive"))
      (node (ref "C80") (pin "2") (pinfunction "2_2") (pintype "passive"))
      (node (ref "C81") (pin "1") (pinfunction "1_1") (pintype "passive"))
      (node (ref "C84") (pin "2") (pinfunction "2_2") (pintype "passive"))
      (node (ref "C85") (pin "1") (pinfunction "1_1") (pintype "passive"))
      (node (ref "C86") (pin "2") (pinfunction "2_2") (pintype "passive"))
      (node (ref "C88") (pin "1") (pinfunction "1_1") (pintype "passive"))
      (node (ref "C9") (pin "2") (pinfunction "2_2") (pintype "passive"))
      (node (ref "C90") (pin "2") (pinfunction "2_2") (pintype "passive"))
      (node (ref "C91") (pin "1") (pinfunction "1_1") (pintype "passive"))
      (node (ref "C92") (pin "2") (pinfunction "2_2") (pintype "passive"))
      (node (ref "C93") (pin "1") (pinfunction "1_1") (pintype "passive"))
      (node (ref "C94") (pin "2") (pinfunction "2_2") (pintype "passive"))
      (node (ref "C95") (pin "1") (pinfunction "1_1") (pintype "passive"))
      (node (ref "C98") (pin "2") (pinfunction "2_2") (pintype "passive"))
      (node (ref "C99") (pin "1") (pinfunction "1_1") (pintype "passive"))
      (node (ref "COM") (pin "1") (pinfunction "1_1") (pintype "passive"))
      (node (ref "COM") (pin "2") (pinfunction "2_2") (pintype "passive"))
      (node (ref "G1") (pin "6") (pinfunction "COM_6") (pintype "bidirectional"))
      (node (ref "IC1") (pin "6") (pinfunction "REF_6") (pintype "bidirectional"))
      (node (ref "IC10") (pin "2") (pinfunction "-VS_2") (pintype "power_in"))
      (node (ref "IC11") (pin "6") (pinfunction "REF_6") (pintype "bidirectional"))
      (node (ref "IC13") (pin "2") (pinfunction "-VS_2") (pintype "power_in"))
      (node (ref "IC14") (pin "6") (pinfunction "REF_6") (pintype "bidirectional"))
      (node (ref "IC16") (pin "2") (pinfunction "-VS_2") (pintype "power_in"))
      (node (ref "IC17") (pin "6") (pinfunction "REF_6") (pintype "bidirectional"))
      (node (ref "IC19") (pin "2") (pinfunction "-VS_2") (pintype "power_in"))
      (node (ref "IC20") (pin "6") (pinfunction "REF_6") (pintype "bidirectional"))
      (node (ref "IC22") (pin "2") (pinfunction "-VS_2") (pintype "power_in"))
      (node (ref "IC23") (pin "6") (pinfunction "REF_6") (pintype "bidirectional"))
      (node (ref "IC25") (pin "2") (pinfunction "-VS_2") (pintype "power_in"))
      (node (ref "IC26") (pin "6") (pinfunction "REF_6") (pintype "bidirectional"))
      (node (ref "IC28") (pin "2") (pinfunction "-VS_2") (pintype "power_in"))
      (node (ref "IC3") (pin "17") (pinfunction "DGND_17") (pintype "bidirectional"))
      (node (ref "IC3") (pin "2") (pinfunction "AGND_2") (pintype "bidirectional"))
      (node (ref "IC3") (pin "20") (pinfunction "CS_20") (pintype "bidirectional"))
      (node (ref "IC3") (pin "3") (pinfunction "VREFN_3") (pintype "bidirectional"))
      (node (ref "IC4") (pin "2") (pinfunction "-VS_2") (pintype "power_in"))
      (node (ref "IC5") (pin "1") (pinfunction "GND_1") (pintype "passive"))
      (node (ref "IC6") (pin "2") (pinfunction "GND1_2") (pintype "bidirectional"))
      (node (ref "IC6") (pin "8") (pinfunction "GND1__8") (pintype "bidirectional"))
      (node (ref "IC7") (pin "3") (pinfunction "GND_3") (pintype "bidirectional"))
      (node (ref "IC8") (pin "6") (pinfunction "REF_6") (pintype "bidirectional"))
      (node (ref "R10") (pin "1") (pinfunction "1_1") (pintype "passive"))
      (node (ref "R102") (pin "2") (pinfunction "2_2") (pintype "passive"))
      (node (ref "R112") (pin "2") (pinfunction "2_2") (pintype "passive"))
      (node (ref "R113") (pin "2") (pinfunction "2_2") (pintype "passive"))
      (node (ref "R114") (pin "1") (pinfunction "1_1") (pintype "passive"))
      (node (ref "R117") (pin "2") (pinfunction "2_2") (pintype "passive"))
      (node (ref "R122") (pin "2") (pinfunction "2_2") (pintype "passive"))
      (node (ref "R13") (pin "2") (pinfunction "2_2") (pintype "passive"))
      (node (ref "R132") (pin "2") (pinfunction "2_2") (pintype "passive"))
      (node (ref "R133") (pin "2") (pinfunction "2_2") (pintype "passive"))
      (node (ref "R134") (pin "1") (pinfunction "1_1") (pintype "passive"))
      (node (ref "R137") (pin "2") (pinfunction "2_2") (pintype "passive"))
      (node (ref "R142") (pin "2") (pinfunction "2_2") (pintype "passive"))
      (node (ref "R152") (pin "2") (pinfunction "2_2") (pintype "passive"))
      (node (ref "R153") (pin "2") (pinfunction "2_2") (pintype "passive"))
      (node (ref "R154") (pin "1") (pinfunction "1_1") (pintype "passive"))
      (node (ref "R157") (pin "2") (pinfunction "2_2") (pintype "passive"))
      (node (ref "R162") (pin "2") (pinfunction "2_2") (pintype "passive"))
      (node (ref "R21") (pin "2") (pinfunction "2_2") (pintype "passive"))
      (node (ref "R32") (pin "2") (pinfunction "2_2") (pintype "passive"))
      (node (ref "R33") (pin "2") (pinfunction "2_2") (pintype "passive"))
      (node (ref "R34") (pin "1") (pinfunction "1_1") (pintype "passive"))
      (node (ref "R37") (pin "2") (pinfunction "2_2") (pintype "passive"))
      (node (ref "R42") (pin "2") (pinfunction "2_2") (pintype "passive"))
      (node (ref "R52") (pin "2") (pinfunction "2_2") (pintype "passive"))
      (node (ref "R53") (pin "2") (pinfunction "2_2") (pintype "passive"))
      (node (ref "R54") (pin "1") (pinfunction "1_1") (pintype "passive"))
      (node (ref "R57") (pin "2") (pinfunction "2_2") (pintype "passive"))
      (node (ref "R62") (pin "2") (pinfunction "2_2") (pintype "passive"))
      (node (ref "R72") (pin "2") (pinfunction "2_2") (pintype "passive"))
      (node (ref "R73") (pin "2") (pinfunction "2_2") (pintype "passive"))
      (node (ref "R74") (pin "1") (pinfunction "1_1") (pintype "passive"))
      (node (ref "R77") (pin "2") (pinfunction "2_2") (pintype "passive"))
      (node (ref "R8") (pin "2") (pinfunction "2_2") (pintype "passive"))
      (node (ref "R82") (pin "2") (pinfunction "2_2") (pintype "passive"))
      (node (ref "R9") (pin "2") (pinfunction "2_2") (pintype "passive"))
      (node (ref "R92") (pin "2") (pinfunction "2_2") (pintype "passive"))
      (node (ref "R93") (pin "2") (pinfunction "2_2") (pintype "passive"))
      (node (ref "R94") (pin "1") (pinfunction "1_1") (pintype "passive"))
      (node (ref "R97") (pin "2") (pinfunction "2_2") (pintype "passive"))
    )
    (net (code "5") (name "Net-(C12-Pad2)") (class "Default")
      (node (ref "C12") (pin "2") (pinfunction "2_2") (pintype "passive"))
      (node (ref "C13") (pin "1") (pinfunction "1_1") (pintype "passive"))
      (node (ref "R12") (pin "1") (pinfunction "1_1") (pintype "passive"))
    )
    (net (code "6") (name "Net-(C37-Pad2)") (class "Default")
      (node (ref "C37") (pin "2") (pinfunction "2_2") (pintype "passive"))
      (node (ref "C38") (pin "1") (pinfunction "1_1") (pintype "passive"))
      (node (ref "R36") (pin "1") (pinfunction "1_1") (pintype "passive"))
    )
    (net (code "7") (name "Net-(C42-Pad1)") (class "Default")
      (node (ref "C42") (pin "1") (pinfunction "1_1") (pintype "passive"))
      (node (ref "R38") (pin "1") (pinfunction "1_1") (pintype "passive"))
      (node (ref "R41") (pin "2") (pinfunction "2_2") (pintype "passive"))
    )
    (net (code "8") (name "Net-(C53-Pad2)") (class "Default")
      (node (ref "C53") (pin "2") (pinfunction "2_2") (pintype "passive"))
      (node (ref "C54") (pin "1") (pinfunction "1_1") (pintype "passive"))
      (node (ref "R56") (pin "1") (pinfunction "1_1") (pintype "passive"))
    )
    (net (code "9") (name "Net-(C56-Pad1)") (class "Default")
      (node (ref "C56") (pin "1") (pinfunction "1_1") (pintype "passive"))
      (node (ref "R19") (pin "2") (pinfunction "2_2") (pintype "passive"))
      (node (ref "R20") (pin "1") (pinfunction "1_1") (pintype "passive"))
    )
    (net (code "10") (name "Net-(C59-Pad1)") (class "Default")
      (node (ref "C59") (pin "1") (pinfunction "1_1") (pintype "passive"))
      (node (ref "R58") (pin "1") (pinfunction "1_1") (pintype "passive"))
      (node (ref "R61") (pin "2") (pinfunction "2_2") (pintype "passive"))
    )
    (net (code "11") (name "Net-(C68-Pad2)") (class "Default")
      (node (ref "C68") (pin "2") (pinfunction "2_2") (pintype "passive"))
      (node (ref "C69") (pin "1") (pinfunction "1_1") (pintype "passive"))
      (node (ref "R76") (pin "1") (pinfunction "1_1") (pintype "passive"))
    )
    (net (code "12") (name "Net-(C73-Pad1)") (class "Default")
      (node (ref "C73") (pin "1") (pinfunction "1_1") (pintype "passive"))
      (node (ref "R78") (pin "1") (pinfunction "1_1") (pintype "passive"))
      (node (ref "R81") (pin "2") (pinfunction "2_2") (pintype "passive"))
    )
    (net (code "13") (name "Net-(C82-Pad2)") (class "Default")
      (node (ref "C82") (pin "2") (pinfunction "2_2") (pintype "passive"))
      (node (ref "C83") (pin "1") (pinfunction "1_1") (pintype "passive"))
      (node (ref "R96") (pin "1") (pinfunction "1_1") (pintype "passive"))
    )
    (net (code "14") (name "Net-(C87-Pad1)") (class "Default")
      (node (ref "C87") (pin "1") (pinfunction "1_1") (pintype "passive"))
      (node (ref "R101") (pin "2") (pinfunction "2_2") (pintype "passive"))
      (node (ref "R98") (pin "1") (pinfunction "1_1") (pintype "passive"))
    )
    (net (code "15") (name "Net-(C96-Pad2)") (class "Default")
      (node (ref "C96") (pin "2") (pinfunction "2_2") (pintype "passive"))
      (node (ref "C97") (pin "1") (pinfunction "1_1") (pintype "passive"))
      (node (ref "R116") (pin "1") (pinfunction "1_1") (pintype "passive"))
    )
    (net (code "16") (name "Net-(C101-Pad1)") (class "Default")
      (node (ref "C101") (pin "1") (pinfunction "1_1") (pintype "passive"))
      (node (ref "R118") (pin "1") (pinfunction "1_1") (pintype "passive"))
      (node (ref "R121") (pin "2") (pinfunction "2_2") (pintype "passive"))
    )
    (net (code "17") (name "Net-(C110-Pad2)") (class "Default")
      (node (ref "C110") (pin "2") (pinfunction "2_2") (pintype "passive"))
      (node (ref "C111") (pin "1") (pinfunction "1_1") (pintype "passive"))
      (node (ref "R136") (pin "1") (pinfunction "1_1") (pintype "passive"))
    )
    (net (code "18") (name "Net-(C115-Pad1)") (class "Default")
      (node (ref "C115") (pin "1") (pinfunction "1_1") (pintype "passive"))
      (node (ref "R138") (pin "1") (pinfunction "1_1") (pintype "passive"))
      (node (ref "R141") (pin "2") (pinfunction "2_2") (pintype "passive"))
    )
    (net (code "19") (name "Net-(C124-Pad2)") (class "Default")
      (node (ref "C124") (pin "2") (pinfunction "2_2") (pintype "passive"))
      (node (ref "C125") (pin "1") (pinfunction "1_1") (pintype "passive"))
      (node (ref "R156") (pin "1") (pinfunction "1_1") (pintype "passive"))
    )
    (net (code "20") (name "Net-(C129-Pad1)") (class "Default")
      (node (ref "C129") (pin "1") (pinfunction "1_1") (pintype "passive"))
      (node (ref "R158") (pin "1") (pinfunction "1_1") (pintype "passive"))
      (node (ref "R161") (pin "2") (pinfunction "2_2") (pintype "passive"))
    )
    (net (code "21") (name "Net-(D1-AC)") (class "Default")
      (node (ref "C1") (pin "1") (pinfunction "1_1") (pintype "passive"))
      (node (ref "C2") (pin "1") (pinfunction "1_1") (pintype "passive"))
      (node (ref "D1") (pin "3") (pinfunction "AC_3") (pintype "passive"))
      (node (ref "R1") (pin "2") (pinfunction "2_2") (pintype "passive"))
      (node (ref "R5") (pin "1") (pinfunction "1_1") (pintype "passive"))
    )
    (net (code "22") (name "Net-(D2-AC)") (class "Default")
      (node (ref "C1") (pin "2") (pinfunction "2_2") (pintype "passive"))
      (node (ref "C3") (pin "2") (pinfunction "2_2") (pintype "passive"))
      (node (ref "D2") (pin "3") (pinfunction "AC_3") (pintype "passive"))
      (node (ref "R2") (pin "2") (pinfunction "2_2") (pintype "passive"))
      (node (ref "R6") (pin "1") (pinfunction "1_1") (pintype "passive"))
    )
    (net (code "23") (name "Net-(D3-AC)") (class "Default")
      (node (ref "D3") (pin "3") (pinfunction "AC_3") (pintype "passive"))
      (node (ref "IC2") (pin "8") (pinfunction "OUT3_8") (pintype "bidirectional"))
      (node (ref "IC2") (pin "9") (pinfunction "-IN3_9") (pintype "bidirectional"))
      (node (ref "R3") (pin "2") (pinfunction "2_2") (pintype "passive"))
      (node (ref "R8") (pin "1") (pinfunction "1_1") (pintype "passive"))
    )
    (net (code "24") (name "Net-(D4-AC)") (class "Default")
      (node (ref "D4") (pin "3") (pinfunction "AC_3") (pintype "passive"))
      (node (ref "IC2") (pin "13") (pinfunction "-IN4_13") (pintype "bidirectional"))
      (node (ref "IC2") (pin "14") (pinfunction "OUT4_14") (pintype "bidirectional"))
      (node (ref "R4") (pin "2") (pinfunction "2_2") (pintype "passive"))
      (node (ref "R9") (pin "1") (pinfunction "1_1") (pintype "passive"))
    )
    (net (code "25") (name "Net-(D5-AC)") (class "Default")
      (node (ref "C30") (pin "1") (pinfunction "1_1") (pintype "passive"))
      (node (ref "C31") (pin "1") (pinfunction "1_1") (pintype "passive"))
      (node (ref "D5") (pin "3") (pinfunction "AC_3") (pintype "passive"))
      (node (ref "R24") (pin "2") (pinfunction "2_2") (pintype "passive"))
      (node (ref "R29") (pin "1") (pinfunction "1_1") (pintype "passive"))
    )
    (net (code "26") (name "Net-(D6-AC)") (class "Default")
      (node (ref "C30") (pin "2") (pinfunction "2_2") (pintype "passive"))
      (node (ref "C32") (pin "2") (pinfunction "2_2") (pintype "passive"))
      (node (ref "D6") (pin "3") (pinfunction "AC_3") (pintype "passive"))
      (node (ref "R26") (pin "2") (pinfunction "2_2") (pintype "passive"))
      (node (ref "R30") (pin "1") (pinfunction "1_1") (pintype "passive"))
    )
    (net (code "27") (name "Net-(D7-AC)") (class "Default")
      (node (ref "D7") (pin "3") (pinfunction "AC_3") (pintype "passive"))
      (node (ref "IC9") (pin "8") (pinfunction "OUT3_8") (pintype "bidirectional"))
      (node (ref "IC9") (pin "9") (pinfunction "-IN3_9") (pintype "bidirectional"))
      (node (ref "R27") (pin "2") (pinfunction "2_2") (pintype "passive"))
      (node (ref "R32") (pin "1") (pinfunction "1_1") (pintype "passive"))
    )
    (net (code "28") (name "Net-(D8-AC)") (class "Default")
      (node (ref "D8") (pin "3") (pinfunction "AC_3") (pintype "passive"))
      (node (ref "IC9") (pin "13") (pinfunction "-IN4_13") (pintype "bidirectional"))
      (node (ref "IC9") (pin "14") (pinfunction "OUT4_14") (pintype "bidirectional"))
      (node (ref "R28") (pin "2") (pinfunction "2_2") (pintype "passive"))
      (node (ref "R33") (pin "1") (pinfunction "1_1") (pintype "passive"))
    )
    (net (code "29") (name "Net-(D9-AC)") (class "Default")
      (node (ref "C45") (pin "1") (pinfunction "1_1") (pintype "passive"))
      (node (ref "C46") (pin "1") (pinfunction "1_1") (pintype "passive"))
      (node (ref "D9") (pin "3") (pinfunction "AC_3") (pintype "passive"))
      (node (ref "R45") (pin "2") (pinfunction "2_2") (pintype "passive"))
      (node (ref "R49") (pin "1") (pinfunction "1_1") (pintype "passive"))
    )
    (net (code "30") (name "Net-(D10-AC)") (class "Default")
      (node (ref "C45") (pin "2") (pinfunction "2_2") (pintype "passive"))
      (node (ref "C47") (pin "2") (pinfunction "2_2") (pintype "passive"))
      (node (ref "D10") (pin "3") (pinfunction "AC_3") (pintype "passive"))
      (node (ref "R46") (pin "2") (pinfunction "2_2") (pintype "passive"))
      (node (ref "R50") (pin "1") (pinfunction "1_1") (pintype "passive"))
    )
    (net (code "31") (name "Net-(D11-AC)") (class "Default")
      (node (ref "D11") (pin "3") (pinfunction "AC_3") (pintype "passive"))
      (node (ref "IC12") (pin "8") (pinfunction "OUT3_8") (pintype "bidirectional"))
      (node (ref "IC12") (pin "9") (pinfunction "-IN3_9") (pintype "bidirectional"))
      (node (ref "R47") (pin "2") (pinfunction "2_2") (pintype "passive"))
      (node (ref "R52") (pin "1") (pinfunction "1_1") (pintype "passive"))
    )
    (net (code "32") (name "Net-(D12-AC)") (class "Default")
      (node (ref "D12") (pin "3") (pinfunction "AC_3") (pintype "passive"))
      (node (ref "IC12") (pin "13") (pinfunction "-IN4_13") (pintype "bidirectional"))
      (node (ref "IC12") (pin "14") (pinfunction "OUT4_14") (pintype "bidirectional"))
      (node (ref "R48") (pin "2") (pinfunction "2_2") (pintype "passive"))
      (node (ref "R53") (pin "1") (pinfunction "1_1") (pintype "passive"))
    )
    (net (code "33") (name "Net-(D13-AC)") (class "Default")
      (node (ref "C61") (pin "1") (pinfunction "1_1") (pintype "passive"))
      (node (ref "C62") (pin "1") (pinfunction "1_1") (pintype "passive"))
      (node (ref "D13") (pin "3") (pinfunction "AC_3") (pintype "passive"))
      (node (ref "R65") (pin "2") (pinfunction "2_2") (pintype "passive"))
      (node (ref "R69") (pin "1") (pinfunction "1_1") (pintype "passive"))
    )
    (net (code "34") (name "Net-(D14-AC)") (class "Default")
      (node (ref "C61") (pin "2") (pinfunction "2_2") (pintype "passive"))
      (node (ref "C63") (pin "2") (pinfunction "2_2") (pintype "passive"))
      (node (ref "D14") (pin "3") (pinfunction "AC_3") (pintype "passive"))
      (node (ref "R66") (pin "2") (pinfunction "2_2") (pintype "passive"))
      (node (ref "R70") (pin "1") (pinfunction "1_1") (pintype "passive"))
    )
    (net (code "35") (name "Net-(D15-AC)") (class "Default")
      (node (ref "D15") (pin "3") (pinfunction "AC_3") (pintype "passive"))
      (node (ref "IC15") (pin "8") (pinfunction "OUT3_8") (pintype "bidirectional"))
      (node (ref "IC15") (pin "9") (pinfunction "-IN3_9") (pintype "bidirectional"))
      (node (ref "R67") (pin "2") (pinfunction "2_2") (pintype "passive"))
      (node (ref "R72") (pin "1") (pinfunction "1_1") (pintype "passive"))
    )
    (net (code "36") (name "Net-(D16-AC)") (class "Default")
      (node (ref "D16") (pin "3") (pinfunction "AC_3") (pintype "passive"))
      (node (ref "IC15") (pin "13") (pinfunction "-IN4_13") (pintype "bidirectional"))
      (node (ref "IC15") (pin "14") (pinfunction "OUT4_14") (pintype "bidirectional"))
      (node (ref "R68") (pin "2") (pinfunction "2_2") (pintype "passive"))
      (node (ref "R73") (pin "1") (pinfunction "1_1") (pintype "passive"))
    )
    (net (code "37") (name "Net-(D17-AC)") (class "Default")
      (node (ref "C75") (pin "1") (pinfunction "1_1") (pintype "passive"))
      (node (ref "C76") (pin "1") (pinfunction "1_1") (pintype "passive"))
      (node (ref "D17") (pin "3") (pinfunction "AC_3") (pintype "passive"))
      (node (ref "R85") (pin "2") (pinfunction "2_2") (pintype "passive"))
      (node (ref "R89") (pin "1") (pinfunction "1_1") (pintype "passive"))
    )
    (net (code "38") (name "Net-(D18-AC)") (class "Default")
      (node (ref "C75") (pin "2") (pinfunction "2_2") (pintype "passive"))
      (node (ref "C77") (pin "2") (pinfunction "2_2") (pintype "passive"))
      (node (ref "D18") (pin "3") (pinfunction "AC_3") (pintype "passive"))
      (node (ref "R86") (pin "2") (pinfunction "2_2") (pintype "passive"))
      (node (ref "R90") (pin "1") (pinfunction "1_1") (pintype "passive"))
    )
    (net (code "39") (name "Net-(D19-AC)") (class "Default")
      (node (ref "D19") (pin "3") (pinfunction "AC_3") (pintype "passive"))
      (node (ref "IC18") (pin "8") (pinfunction "OUT3_8") (pintype "bidirectional"))
      (node (ref "IC18") (pin "9") (pinfunction "-IN3_9") (pintype "bidirectional"))
      (node (ref "R87") (pin "2") (pinfunction "2_2") (pintype "passive"))
      (node (ref "R92") (pin "1") (pinfunction "1_1") (pintype "passive"))
    )
    (net (code "40") (name "Net-(D20-AC)") (class "Default")
      (node (ref "D20") (pin "3") (pinfunction "AC_3") (pintype "passive"))
      (node (ref "IC18") (pin "13") (pinfunction "-IN4_13") (pintype "bidirectional"))
      (node (ref "IC18") (pin "14") (pinfunction "OUT4_14") (pintype "bidirectional"))
      (node (ref "R88") (pin "2") (pinfunction "2_2") (pintype "passive"))
      (node (ref "R93") (pin "1") (pinfunction "1_1") (pintype "passive"))
    )
    (net (code "41") (name "Net-(D21-AC)") (class "Default")
      (node (ref "C89") (pin "1") (pinfunction "1_1") (pintype "passive"))
      (node (ref "C90") (pin "1") (pinfunction "1_1") (pintype "passive"))
      (node (ref "D21") (pin "3") (pinfunction "AC_3") (pintype "passive"))
      (node (ref "R105") (pin "2") (pinfunction "2_2") (pintype "passive"))
      (node (ref "R109") (pin "1") (pinfunction "1_1") (pintype "passive"))
    )
    (net (code "42") (name "Net-(D22-AC)") (class "Default")
      (node (ref "C89") (pin "2") (pinfunction "2_2") (pintype "passive"))
      (node (ref "C91") (pin "2") (pinfunction "2_2") (pintype "passive"))
      (node (ref "D22") (pin "3") (pinfunction "AC_3") (pintype "passive"))
      (node (ref "R106") (pin "2") (pinfunction "2_2") (pintype "passive"))
      (node (ref "R110") (pin "1") (pinfunction "1_1") (pintype "passive"))
    )
    (net (code "43") (name "Net-(D23-AC)") (class "Default")
      (node (ref "D23") (pin "3") (pinfunction "AC_3") (pintype "passive"))
      (node (ref "IC21") (pin "8") (pinfunction "OUT3_8") (pintype "bidirectional"))
      (node (ref "IC21") (pin "9") (pinfunction "-IN3_9") (pintype "bidirectional"))
      (node (ref "R107") (pin "2") (pinfunction "2_2") (pintype "passive"))
      (node (ref "R112") (pin "1") (pinfunction "1_1") (pintype "passive"))
    )
    (net (code "44") (name "Net-(D24-AC)") (class "Default")
      (node (ref "D24") (pin "3") (pinfunction "AC_3") (pintype "passive"))
      (node (ref "IC21") (pin "13") (pinfunction "-IN4_13") (pintype "bidirectional"))
      (node (ref "IC21") (pin "14") (pinfunction "OUT4_14") (pintype "bidirectional"))
      (node (ref "R108") (pin "2") (pinfunction "2_2") (pintype "passive"))
      (node (ref "R113") (pin "1") (pinfunction "1_1") (pintype "passive"))
    )
    (net (code "45") (name "Net-(D25-AC)") (class "Default")
      (node (ref "C103") (pin "1") (pinfunction "1_1") (pintype "passive"))
      (node (ref "C104") (pin "1") (pinfunction "1_1") (pintype "passive"))
      (node (ref "D25") (pin "3") (pinfunction "AC_3") (pintype "passive"))
      (node (ref "R125") (pin "2") (pinfunction "2_2") (pintype "passive"))
      (node (ref "R129") (pin "1") (pinfunction "1_1") (pintype "passive"))
    )
    (net (code "46") (name "Net-(D26-AC)") (class "Default")
      (node (ref "C103") (pin "2") (pinfunction "2_2") (pintype "passive"))
      (node (ref "C105") (pin "2") (pinfunction "2_2") (pintype "passive"))
      (node (ref "D26") (pin "3") (pinfunction "AC_3") (pintype "passive"))
      (node (ref "R126") (pin "2") (pinfunction "2_2") (pintype "passive"))
      (node (ref "R130") (pin "1") (pinfunction "1_1") (pintype "passive"))
    )
    (net (code "47") (name "Net-(D27-AC)") (class "Default")
      (node (ref "D27") (pin "3") (pinfunction "AC_3") (pintype "passive"))
      (node (ref "IC24") (pin "8") (pinfunction "OUT3_8") (pintype "bidirectional"))
      (node (ref "IC24") (pin "9") (pinfunction "-IN3_9") (pintype "bidirectional"))
      (node (ref "R127") (pin "2") (pinfunction "2_2") (pintype "passive"))
      (node (ref "R132") (pin "1") (pinfunction "1_1") (pintype "passive"))
    )
    (net (code "48") (name "Net-(D28-AC)") (class "Default")
      (node (ref "D28") (pin "3") (pinfunction "AC_3") (pintype "passive"))
      (node (ref "IC24") (pin "13") (pinfunction "-IN4_13") (pintype "bidirectional"))
      (node (ref "IC24") (pin "14") (pinfunction "OUT4_14") (pintype "bidirectional"))
      (node (ref "R128") (pin "2") (pinfunction "2_2") (pintype "passive"))
      (node (ref "R133") (pin "1") (pinfunction "1_1") (pintype "passive"))
    )
    (net (code "49") (name "Net-(D29-AC)") (class "Default")
      (node (ref "C117") (pin "1") (pinfunction "1_1") (pintype "passive"))
      (node (ref "C118") (pin "1") (pinfunction "1_1") (pintype "passive"))
      (node (ref "D29") (pin "3") (pinfunction "AC_3") (pintype "passive"))
      (node (ref "R145") (pin "2") (pinfunction "2_2") (pintype "passive"))
      (node (ref "R149") (pin "1") (pinfunction "1_1") (pintype "passive"))
    )
    (net (code "50") (name "Net-(D30-AC)") (class "Default")
      (node (ref "C117") (pin "2") (pinfunction "2_2") (pintype "passive"))
      (node (ref "C119") (pin "2") (pinfunction "2_2") (pintype "passive"))
      (node (ref "D30") (pin "3") (pinfunction "AC_3") (pintype "passive"))
      (node (ref "R146") (pin "2") (pinfunction "2_2") (pintype "passive"))
      (node (ref "R150") (pin "1") (pinfunction "1_1") (pintype "passive"))
    )
    (net (code "51") (name "Net-(D31-AC)") (class "Default")
      (node (ref "D31") (pin "3") (pinfunction "AC_3") (pintype "passive"))
      (node (ref "IC27") (pin "8") (pinfunction "OUT3_8") (pintype "bidirectional"))
      (node (ref "IC27") (pin "9") (pinfunction "-IN3_9") (pintype "bidirectional"))
      (node (ref "R147") (pin "2") (pinfunction "2_2") (pintype "passive"))
      (node (ref "R152") (pin "1") (pinfunction "1_1") (pintype "passive"))
    )
    (net (code "52") (name "Net-(D32-AC)") (class "Default")
      (node (ref "D32") (pin "3") (pinfunction "AC_3") (pintype "passive"))
      (node (ref "IC27") (pin "13") (pinfunction "-IN4_13") (pintype "bidirectional"))
      (node (ref "IC27") (pin "14") (pinfunction "OUT4_14") (pintype "bidirectional"))
      (node (ref "R148") (pin "2") (pinfunction "2_2") (pintype "passive"))
      (node (ref "R153") (pin "1") (pinfunction "1_1") (pintype "passive"))
    )
    (net (code "53") (name "Net-(G1-+VIN)") (class "Default")
      (node (ref "G1") (pin "1") (pinfunction "+VIN_1") (pintype "bidirectional"))
      (node (ref "INT") (pin "1") (pinfunction "1_1") (pintype "passive"))
    )
    (net (code "54") (name "Net-(G1-+VOUT)") (class "Default")
      (node (ref "C22") (pin "+") (pinfunction "+_+") (pintype "passive"))
      (node (ref "C24") (pin "1") (pinfunction "1_1") (pintype "passive"))
      (node (ref "G1") (pin "7") (pinfunction "+VOUT_7") (pintype "bidirectional"))
      (node (ref "IC5") (pin "2@1") (pinfunction "VI1_2@1") (pintype "input"))
      (node (ref "L1") (pin "2") (pinfunction "2_2") (pintype "passive"))
    )
    (net (code "55") (name "Net-(G1--VIN)") (class "Default")
      (node (ref "C18") (pin "2") (pinfunction "2_2") (pintype "passive"))
      (node (ref "G1") (pin "2") (pinfunction "-VIN_2") (pintype "bidirectional"))
      (node (ref "IC6") (pin "15") (pinfunction "GND2_15") (pintype "bidirectional"))
      (node (ref "IC6") (pin "9") (pinfunction "GND2__9") (pintype "bidirectional"))
      (node (ref "INT") (pin "3") (pinfunction "3_3") (pintype "passive"))
      (node (ref "INT") (pin "8") (pinfunction "8_8") (pintype "passive"))
    )
    (net (code "56") (name "Net-(G1--VOUT)") (class "Default")
      (node (ref "C23") (pin "-") (pinfunction "-_-") (pintype "passive"))
      (node (ref "C25") (pin "2") (pinfunction "2_2") (pintype "passive"))
      (node (ref "G1") (pin "5") (pinfunction "-VOUT_5") (pintype "bidirectional"))
      (node (ref "L2") (pin "2") (pinfunction "2_2") (pintype "passive"))
    )
    (net (code "57") (name "Net-(IC1-+IN)") (class "Default")
      (node (ref "IC1") (pin "4") (pinfunction "+IN_4") (pintype "bidirectional"))
      (node (ref "R6") (pin "2") (pinfunction "2_2") (pintype "passive"))
    )
    (net (code "58") (name "Net-(IC1-+RG)") (class "Default")
      (node (ref "IC1") (pin "3") (pinfunction "+RG_3") (pintype "bidirectional"))
      (node (ref "IC2") (pin "12") (pinfunction "+IN4_12") (pintype "bidirectional"))
      (node (ref "R7") (pin "1") (pinfunction "1_1") (pintype "passive"))
    )
    (net (code "59") (name "Net-(IC1--IN)") (class "Default")
      (node (ref "IC1") (pin "1") (pinfunction "-IN_1") (pintype "bidirectional"))
      (node (ref "R5") (pin "2") (pinfunction "2_2") (pintype "passive"))
    )
    (net (code "60") (name "Net-(IC1--RG)") (class "Default")
      (node (ref "IC1") (pin "2") (pinfunction "-RG_2") (pintype "bidirectional"))
      (node (ref "IC2") (pin "10") (pinfunction "+IN3_10") (pintype "bidirectional"))
      (node (ref "R7") (pin "2") (pinfunction "2_2") (pintype "passive"))
    )
    (net (code "61") (name "Net-(IC1-OUT)") (class "Default")
      (node (ref "C12") (pin "1") (pinfunction "1_1") (pintype "passive"))
      (node (ref "IC1") (pin "7") (pinfunction "OUT_7") (pintype "bidirectional"))
    )
    (net (code "62") (name "Net-(IC2-+IN1)") (class "Default")
      (node (ref "C14") (pin "1") (pinfunction "1_1") (pintype "passive"))
      (node (ref "IC2") (pin "3") (pinfunction "+IN1_3") (pintype "bidirectional"))
      (node (ref "R19") (pin "1") (pinfunction "1_1") (pintype "passive"))
    )
    (net (code "63") (name "Net-(IC2-+IN2)") (class "Default")
      (node (ref "C13") (pin "2") (pinfunction "2_2") (pintype "passive"))
      (node (ref "IC2") (pin "5") (pinfunction "+IN2_5") (pintype "bidirectional"))
      (node (ref "R13") (pin "1") (pinfunction "1_1") (pintype "passive"))
    )
    (net (code "64") (name "Net-(IC2--IN1)") (class "Default")
      (node (ref "IC2") (pin "2") (pinfunction "-IN1_2") (pintype "bidirectional"))
      (node (ref "R21") (pin "1") (pinfunction "1_1") (pintype "passive"))
      (node (ref "R23") (pin "1") (pinfunction "1_1") (pintype "passive"))
    )
    (net (code "65") (name "Net-(IC2--IN2)") (class "Default")
      (node (ref "IC2") (pin "6") (pinfunction "-IN2_6") (pintype "bidirectional"))
      (node (ref "R10") (pin "2") (pinfunction "2_2") (pintype "passive"))
      (node (ref "R11") (pin "2") (pinfunction "2_2") (pintype "passive"))
    )
    (net (code "66") (name "Net-(IC2-OUT1)") (class "Default")
      (node (ref "C56") (pin "2") (pinfunction "2_2") (pintype "passive"))
      (node (ref "IC2") (pin "1") (pinfunction "OUT1_1") (pintype "bidirectional"))
      (node (ref "R22") (pin "2") (pinfunction "2_2") (pintype "passive"))
      (node (ref "R23") (pin "2") (pinfunction "2_2") (pintype "passive"))
    )
    (net (code "67") (name "Net-(IC2-OUT2)") (class "Default")
      (node (ref "IC2") (pin "7") (pinfunction "OUT2_7") (pintype "bidirectional"))
      (node (ref "R11") (pin "1") (pinfunction "1_1") (pintype "passive"))
      (node (ref "R12") (pin "2") (pinfunction "2_2") (pintype "passive"))
      (node (ref "R20") (pin "2") (pinfunction "2_2") (pintype "passive"))
    )
    (net (code "68") (name "Net-(IC3-AIN0)") (class "Default")
      (node (ref "C19") (pin "2") (pinfunction "2_2") (pintype "passive"))
      (node (ref "IC3") (pin "6") (pinfunction "AIN0_6") (pintype "bidirectional"))
      (node (ref "R18") (pin "1") (pinfunction "1_1") (pintype "passive"))
    )
    (net (code "69") (name "Net-(IC3-AIN1)") (class "Default")
      (node (ref "C43") (pin "2") (pinfunction "2_2") (pintype "passive"))
      (node (ref "IC3") (pin "7") (pinfunction "AIN1_7") (pintype "bidirectional"))
      (node (ref "R44") (pin "1") (pinfunction "1_1") (pintype "passive"))
    )
    (net (code "70") (name "Net-(IC3-AIN2)") (class "Default")
      (node (ref "C60") (pin "2") (pinfunction "2_2") (pintype "passive"))
      (node (ref "IC3") (pin "8") (pinfunction "AIN2_8") (pintype "bidirectional"))
      (node (ref "R64") (pin "1") (pinfunction "1_1") (pintype "passive"))
    )
    (net (code "71") (name "Net-(IC3-AIN3)") (class "Default")
      (node (ref "C74") (pin "2") (pinfunction "2_2") (pintype "passive"))
      (node (ref "IC3") (pin "9") (pinfunction "AIN3_9") (pintype "bidirectional"))
      (node (ref "R84") (pin "1") (pinfunction "1_1") (pintype "passive"))
    )
    (net (code "72") (name "Net-(IC3-AIN4)") (class "Default")
      (node (ref "C88") (pin "2") (pinfunction "2_2") (pintype "passive"))
      (node (ref "IC3") (pin "10") (pinfunction "AIN4_10") (pintype "bidirectional"))
      (node (ref "R104") (pin "1") (pinfunction "1_1") (pintype "passive"))
    )
    (net (code "73") (name "Net-(IC3-AIN5)") (class "Default")
      (node (ref "C102") (pin "2") (pinfunction "2_2") (pintype "passive"))
      (node (ref "IC3") (pin "11") (pinfunction "AIN5_11") (pintype "bidirectional"))
      (node (ref "R124") (pin "1") (pinfunction "1_1") (pintype "passive"))
    )
    (net (code "74") (name "Net-(IC3-AIN6)") (class "Default")
      (node (ref "C116") (pin "2") (pinfunction "2_2") (pintype "passive"))
      (node (ref "IC3") (pin "12") (pinfunction "AIN6_12") (pintype "bidirectional"))
      (node (ref "R144") (pin "1") (pinfunction "1_1") (pintype "passive"))
    )
    (net (code "75") (name "Net-(IC3-AIN7)") (class "Default")
      (node (ref "C130") (pin "2") (pinfunction "2_2") (pintype "passive"))
      (node (ref "IC3") (pin "13") (pinfunction "AIN7_13") (pintype "bidirectional"))
      (node (ref "R164") (pin "1") (pinfunction "1_1") (pintype "passive"))
    )
    (net (code "76") (name "Net-(IC3-DIN)") (class "Default")
      (node (ref "IC3") (pin "23") (pinfunction "DIN_23") (pintype "bidirectional"))
      (node (ref "R16") (pin "1") (pinfunction "1_1") (pintype "passive"))
    )
    (net (code "77") (name "Net-(IC3-DOUT)") (class "Default")
      (node (ref "IC3") (pin "22") (pinfunction "DOUT_22") (pintype "bidirectional"))
      (node (ref "R17") (pin "1") (pinfunction "1_1") (pintype "passive"))
    )
    (net (code "78") (name "Net-(IC3-DRDY)") (class "Default")
      (node (ref "IC3") (pin "21") (pinfunction "DRDY_21") (pintype "bidirectional"))
      (node (ref "R14") (pin "1") (pinfunction "1_1") (pintype "passive"))
    )
    (net (code "79") (name "Net-(IC3-SCLK)") (class "Default")
      (node (ref "IC3") (pin "24") (pinfunction "SCLK_24") (pintype "bidirectional"))
      (node (ref "R15") (pin "1") (pinfunction "1_1") (pintype "passive"))
    )
    (net (code "80") (name "Net-(IC3-XTAL1{slash}CLKIN)") (class "Default")
      (node (ref "C9") (pin "1") (pinfunction "1_1") (pintype "passive"))
      (node (ref "IC3") (pin "19") (pinfunction "XTAL1/CLKIN_19") (pintype "bidirectional"))
      (node (ref "Q1") (pin "2") (pinfunction "2_2") (pintype "passive"))
    )
    (net (code "81") (name "Net-(IC3-XTAL2)") (class "Default")
      (node (ref "C10") (pin "1") (pinfunction "1_1") (pintype "passive"))
      (node (ref "IC3") (pin "18") (pinfunction "XTAL2_18") (pintype "bidirectional"))
      (node (ref "Q1") (pin "1") (pinfunction "1_1") (pintype "passive"))
    )
    (net (code "82") (name "Net-(IC4--IN)") (class "Default")
      (node (ref "IC4") (pin "4") (pinfunction "-IN_4") (pintype "bidirectional"))
      (node (ref "R22") (pin "1") (pinfunction "1_1") (pintype "passive"))
      (node (ref "R25") (pin "1") (pinfunction "1_1") (pintype "passive"))
    )
    (net (code "83") (name "Net-(IC4-OUT)") (class "Default")
      (node (ref "IC4") (pin "1") (pinfunction "OUT_1") (pintype "bidirectional"))
      (node (ref "R18") (pin "2") (pinfunction "2_2") (pintype "passive"))
      (node (ref "R25") (pin "2") (pinfunction "2_2") (pintype "passive"))
    )
    (net (code "84") (name "Net-(IC6-VDD2)") (class "Default")
      (node (ref "C18") (pin "1") (pinfunction "1_1") (pintype "passive"))
      (node (ref "IC6") (pin "10") (pinfunction "VE2_10") (pintype "bidirectional"))
      (node (ref "IC6") (pin "16") (pinfunction "VDD2_16") (pintype "bidirectional"))
      (node (ref "INT") (pin "2") (pinfunction "2_2") (pintype "passive"))
    )
    (net (code "85") (name "Net-(IC6-VIA)") (class "Default")
      (node (ref "IC6") (pin "3") (pinfunction "VIA_3") (pintype "bidirectional"))
      (node (ref "R14") (pin "2") (pinfunction "2_2") (pintype "passive"))
    )
    (net (code "86") (name "Net-(IC6-VIB)") (class "Default")
      (node (ref "IC6") (pin "4") (pinfunction "VIB_4") (pintype "bidirectional"))
      (node (ref "R17") (pin "2") (pinfunction "2_2") (pintype "passive"))
    )
    (net (code "87") (name "Net-(IC6-VIC)") (class "Default")
      (node (ref "IC6") (pin "12") (pinfunction "VIC_12") (pintype "bidirectional"))
      (node (ref "INT") (pin "6") (pinfunction "6_6") (pintype "passive"))
    )
    (net (code "88") (name "Net-(IC6-VID)") (class "Default")
      (node (ref "IC6") (pin "11") (pinfunction "VID_11") (pintype "bidirectional"))
      (node (ref "INT") (pin "7") (pinfunction "7_7") (pintype "passive"))
    )
    (net (code "89") (name "Net-(IC6-VOA)") (class "Default")
      (node (ref "IC6") (pin "14") (pinfunction "VOA_14") (pintype "bidirectional"))
      (node (ref "INT") (pin "4") (pinfunction "4_4") (pintype "passive"))
    )
    (net (code "90") (name "Net-(IC6-VOB)") (class "Default")
      (node (ref "IC6") (pin "13") (pinfunction "VOB_13") (pintype "bidirectional"))
      (node (ref "INT") (pin "5") (pinfunction "5_5") (pintype "passive"))
    )
    (net (code "91") (name "Net-(IC6-VOC)") (class "Default")
      (node (ref "IC6") (pin "5") (pinfunction "VOC_5") (pintype "bidirectional"))
      (node (ref "R15") (pin "2") (pinfunction "2_2") (pintype "passive"))
    )
    (net (code "92") (name "Net-(IC6-VOD)") (class "Default")
      (node (ref "IC6") (pin "6") (pinfunction "VOD_6") (pintype "bidirectional"))
      (node (ref "R16") (pin "2") (pinfunction "2_2") (pintype "passive"))
    )
    (net (code "93") (name "Net-(IC8-+IN)") (class "Default")
      (node (ref "IC8") (pin "4") (pinfunction "+IN_4") (pintype "bidirectional"))
      (node (ref "R30") (pin "2") (pinfunction "2_2") (pintype "passive"))
    )
    (net (code "94") (name "Net-(IC8-+RG)") (class "Default")
      (node (ref "IC8") (pin "3") (pinfunction "+RG_3") (pintype "bidirectional"))
      (node (ref "IC9") (pin "12") (pinfunction "+IN4_12") (pintype "bidirectional"))
      (node (ref "R31") (pin "1") (pinfunction "1_1") (pintype "passive"))
    )
    (net (code "95") (name "Net-(IC8--IN)") (class "Default")
      (node (ref "IC8") (pin "1") (pinfunction "-IN_1") (pintype "bidirectional"))
      (node (ref "R29") (pin "2") (pinfunction "2_2") (pintype "passive"))
    )
    (net (code "96") (name "Net-(IC8--RG)") (class "Default")
      (node (ref "IC8") (pin "2") (pinfunction "-RG_2") (pintype "bidirectional"))
      (node (ref "IC9") (pin "10") (pinfunction "+IN3_10") (pintype "bidirectional"))
      (node (ref "R31") (pin "2") (pinfunction "2_2") (pintype "passive"))
    )
    (net (code "97") (name "Net-(IC8-OUT)") (class "Default")
      (node (ref "C37") (pin "1") (pinfunction "1_1") (pintype "passive"))
      (node (ref "IC8") (pin "7") (pinfunction "OUT_7") (pintype "bidirectional"))
    )
    (net (code "98") (name "Net-(IC9-+IN1)") (class "Default")
      (node (ref "C41") (pin "1") (pinfunction "1_1") (pintype "passive"))
      (node (ref "IC9") (pin "3") (pinfunction "+IN1_3") (pintype "bidirectional"))
      (node (ref "R41") (pin "1") (pinfunction "1_1") (pintype "passive"))
    )
    (net (code "99") (name "Net-(IC9-+IN2)") (class "Default")
      (node (ref "C38") (pin "2") (pinfunction "2_2") (pintype "passive"))
      (node (ref "IC9") (pin "5") (pinfunction "+IN2_5") (pintype "bidirectional"))
      (node (ref "R37") (pin "1") (pinfunction "1_1") (pintype "passive"))
    )
    (net (code "100") (name "Net-(IC9--IN1)") (class "Default")
      (node (ref "IC9") (pin "2") (pinfunction "-IN1_2") (pintype "bidirectional"))
      (node (ref "R42") (pin "1") (pinfunction "1_1") (pintype "passive"))
      (node (ref "R43") (pin "1") (pinfunction "1_1") (pintype "passive"))
    )
    (net (code "101") (name "Net-(IC9--IN2)") (class "Default")
      (node (ref "IC9") (pin "6") (pinfunction "-IN2_6") (pintype "bidirectional"))
      (node (ref "R34") (pin "2") (pinfunction "2_2") (pintype "passive"))
      (node (ref "R35") (pin "2") (pinfunction "2_2") (pintype "passive"))
    )
    (net (code "102") (name "Net-(IC9-OUT1)") (class "Default")
      (node (ref "C42") (pin "2") (pinfunction "2_2") (pintype "passive"))
      (node (ref "IC9") (pin "1") (pinfunction "OUT1_1") (pintype "bidirectional"))
      (node (ref "R39") (pin "2") (pinfunction "2_2") (pintype "passive"))
      (node (ref "R43") (pin "2") (pinfunction "2_2") (pintype "passive"))
    )
    (net (code "103") (name "Net-(IC9-OUT2)") (class "Default")
      (node (ref "IC9") (pin "7") (pinfunction "OUT2_7") (pintype "bidirectional"))
      (node (ref "R35") (pin "1") (pinfunction "1_1") (pintype "passive"))
      (node (ref "R36") (pin "2") (pinfunction "2_2") (pintype "passive"))
      (node (ref "R38") (pin "2") (pinfunction "2_2") (pintype "passive"))
    )
    (net (code "104") (name "Net-(IC10--IN)") (class "Default")
      (node (ref "IC10") (pin "4") (pinfunction "-IN_4") (pintype "bidirectional"))
      (node (ref "R39") (pin "1") (pinfunction "1_1") (pintype "passive"))
      (node (ref "R40") (pin "1") (pinfunction "1_1") (pintype "passive"))
    )
    (net (code "105") (name "Net-(IC10-OUT)") (class "Default")
      (node (ref "IC10") (pin "1") (pinfunction "OUT_1") (pintype "bidirectional"))
      (node (ref "R40") (pin "2") (pinfunction "2_2") (pintype "passive"))
      (node (ref "R44") (pin "2") (pinfunction "2_2") (pintype "passive"))
    )
    (net (code "106") (name "Net-(IC11-+IN)") (class "Default")
      (node (ref "IC11") (pin "4") (pinfunction "+IN_4") (pintype "bidirectional"))
      (node (ref "R50") (pin "2") (pinfunction "2_2") (pintype "passive"))
    )
    (net (code "107") (name "Net-(IC11-+RG)") (class "Default")
      (node (ref "IC11") (pin "3") (pinfunction "+RG_3") (pintype "bidirectional"))
      (node (ref "IC12") (pin "12") (pinfunction "+IN4_12") (pintype "bidirectional"))
      (node (ref "R51") (pin "1") (pinfunction "1_1") (pintype "passive"))
    )
    (net (code "108") (name "Net-(IC11--IN)") (class "Default")
      (node (ref "IC11") (pin "1") (pinfunction "-IN_1") (pintype "bidirectional"))
      (node (ref "R49") (pin "2") (pinfunction "2_2") (pintype "passive"))
    )
    (net (code "109") (name "Net-(IC11--RG)") (class "Default")
      (node (ref "IC11") (pin "2") (pinfunction "-RG_2") (pintype "bidirectional"))
      (node (ref "IC12") (pin "10") (pinfunction "+IN3_10") (pintype "bidirectional"))
      (node (ref "R51") (pin "2") (pinfunction "2_2") (pintype "passive"))
    )
    (net (code "110") (name "Net-(IC11-OUT)") (class "Default")
      (node (ref "C53") (pin "1") (pinfunction "1_1") (pintype "passive"))
      (node (ref "IC11") (pin "7") (pinfunction "OUT_7") (pintype "bidirectional"))
    )
    (net (code "111") (name "Net-(IC12-+IN1)") (class "Default")
      (node (ref "C58") (pin "1") (pinfunction "1_1") (pintype "passive"))
      (node (ref "IC12") (pin "3") (pinfunction "+IN1_3") (pintype "bidirectional"))
      (node (ref "R61") (pin "1") (pinfunction "1_1") (pintype "passive"))
    )
    (net (code "112") (name "Net-(IC12-+IN2)") (class "Default")
      (node (ref "C54") (pin "2") (pinfunction "2_2") (pintype "passive"))
      (node (ref "IC12") (pin "5") (pinfunction "+IN2_5") (pintype "bidirectional"))
      (node (ref "R57") (pin "1") (pinfunction "1_1") (pintype "passive"))
    )
    (net (code "113") (name "Net-(IC12--IN1)") (class "Default")
      (node (ref "IC12") (pin "2") (pinfunction "-IN1_2") (pintype "bidirectional"))
      (node (ref "R62") (pin "1") (pinfunction "1_1") (pintype "passive"))
      (node (ref "R63") (pin "1") (pinfunction "1_1") (pintype "passive"))
    )
    (net (code "114") (name "Net-(IC12--IN2)") (class "Default")
      (node (ref "IC12") (pin "6") (pinfunction "-IN2_6") (pintype "bidirectional"))
      (node (ref "R54") (pin "2") (pinfunction "2_2") (pintype "passive"))
      (node (ref "R55") (pin "2") (pinfunction "2_2") (pintype "passive"))
    )
    (net (code "115") (name "Net-(IC12-OUT1)") (class "Default")
      (node (ref "C59") (pin "2") (pinfunction "2_2") (pintype "passive"))
      (node (ref "IC12") (pin "1") (pinfunction "OUT1_1") (pintype "bidirectional"))
      (node (ref "R59") (pin "2") (pinfunction "2_2") (pintype "passive"))
      (node (ref "R63") (pin "2") (pinfunction "2_2") (pintype "passive"))
    )
    (net (code "116") (name "Net-(IC12-OUT2)") (class "Default")
      (node (ref "IC12") (pin "7") (pinfunction "OUT2_7") (pintype "bidirectional"))
      (node (ref "R55") (pin "1") (pinfunction "1_1") (pintype "passive"))
      (node (ref "R56") (pin "2") (pinfunction "2_2") (pintype "passive"))
      (node (ref "R58") (pin "2") (pinfunction "2_2") (pintype "passive"))
    )
    (net (code "117") (name "Net-(IC13--IN)") (class "Default")
      (node (ref "IC13") (pin "4") (pinfunction "-IN_4") (pintype "bidirectional"))
      (node (ref "R59") (pin "1") (pinfunction "1_1") (pintype "passive"))
      (node (ref "R60") (pin "1") (pinfunction "1_1") (pintype "passive"))
    )
    (net (code "118") (name "Net-(IC13-OUT)") (class "Default")
      (node (ref "IC13") (pin "1") (pinfunction "OUT_1") (pintype "bidirectional"))
      (node (ref "R60") (pin "2") (pinfunction "2_2") (pintype "passive"))
      (node (ref "R64") (pin "2") (pinfunction "2_2") (pintype "passive"))
    )
    (net (code "119") (name "Net-(IC14-+IN)") (class "Default")
      (node (ref "IC14") (pin "4") (pinfunction "+IN_4") (pintype "bidirectional"))
      (node (ref "R70") (pin "2") (pinfunction "2_2") (pintype "passive"))
    )
    (net (code "120") (name "Net-(IC14-+RG)") (class "Default")
      (node (ref "IC14") (pin "3") (pinfunction "+RG_3") (pintype "bidirectional"))
      (node (ref "IC15") (pin "12") (pinfunction "+IN4_12") (pintype "bidirectional"))
      (node (ref "R71") (pin "1") (pinfunction "1_1") (pintype "passive"))
    )
    (net (code "121") (name "Net-(IC14--IN)") (class "Default")
      (node (ref "IC14") (pin "1") (pinfunction "-IN_1") (pintype "bidirectional"))
      (node (ref "R69") (pin "2") (pinfunction "2_2") (pintype "passive"))
    )
    (net (code "122") (name "Net-(IC14--RG)") (class "Default")
      (node (ref "IC14") (pin "2") (pinfunction "-RG_2") (pintype "bidirectional"))
      (node (ref "IC15") (pin "10") (pinfunction "+IN3_10") (pintype "bidirectional"))
      (node (ref "R71") (pin "2") (pinfunction "2_2") (pintype "passive"))
    )
    (net (code "123") (name "Net-(IC14-OUT)") (class "Default")
      (node (ref "C68") (pin "1") (pinfunction "1_1") (pintype "passive"))
      (node (ref "IC14") (pin "7") (pinfunction "OUT_7") (pintype "bidirectional"))
    )
    (net (code "124") (name "Net-(IC15-+IN1)") (class "Default")
      (node (ref "C72") (pin "1") (pinfunction "1_1") (pintype "passive"))
      (node (ref "IC15") (pin "3") (pinfunction "+IN1_3") (pintype "bidirectional"))
      (node (ref "R81") (pin "1") (pinfunction "1_1") (pintype "passive"))
    )
    (net (code "125") (name "Net-(IC15-+IN2)") (class "Default")
      (node (ref "C69") (pin "2") (pinfunction "2_2") (pintype "passive"))
      (node (ref "IC15") (pin "5") (pinfunction "+IN2_5") (pintype "bidirectional"))
      (node (ref "R77") (pin "1") (pinfunction "1_1") (pintype "passive"))
    )
    (net (code "126") (name "Net-(IC15--IN1)") (class "Default")
      (node (ref "IC15") (pin "2") (pinfunction "-IN1_2") (pintype "bidirectional"))
      (node (ref "R82") (pin "1") (pinfunction "1_1") (pintype "passive"))
      (node (ref "R83") (pin "1") (pinfunction "1_1") (pintype "passive"))
    )
    (net (code "127") (name "Net-(IC15--IN2)") (class "Default")
      (node (ref "IC15") (pin "6") (pinfunction "-IN2_6") (pintype "bidirectional"))
      (node (ref "R74") (pin "2") (pinfunction "2_2") (pintype "passive"))
      (node (ref "R75") (pin "2") (pinfunction "2_2") (pintype "passive"))
    )
    (net (code "128") (name "Net-(IC15-OUT1)") (class "Default")
      (node (ref "C73") (pin "2") (pinfunction "2_2") (pintype "passive"))
      (node (ref "IC15") (pin "1") (pinfunction "OUT1_1") (pintype "bidirectional"))
      (node (ref "R79") (pin "2") (pinfunction "2_2") (pintype "passive"))
      (node (ref "R83") (pin "2") (pinfunction "2_2") (pintype "passive"))
    )
    (net (code "129") (name "Net-(IC15-OUT2)") (class "Default")
      (node (ref "IC15") (pin "7") (pinfunction "OUT2_7") (pintype "bidirectional"))
      (node (ref "R75") (pin "1") (pinfunction "1_1") (pintype "passive"))
      (node (ref "R76") (pin "2") (pinfunction "2_2") (pintype "passive"))
      (node (ref "R78") (pin "2") (pinfunction "2_2") (pintype "passive"))
    )
    (net (code "130") (name "Net-(IC16--IN)") (class "Default")
      (node (ref "IC16") (pin "4") (pinfunction "-IN_4") (pintype "bidirectional"))
      (node (ref "R79") (pin "1") (pinfunction "1_1") (pintype "passive"))
      (node (ref "R80") (pin "1") (pinfunction "1_1") (pintype "passive"))
    )
    (net (code "131") (name "Net-(IC16-OUT)") (class "Default")
      (node (ref "IC16") (pin "1") (pinfunction "OUT_1") (pintype "bidirectional"))
      (node (ref "R80") (pin "2") (pinfunction "2_2") (pintype "passive"))
      (node (ref "R84") (pin "2") (pinfunction "2_2") (pintype "passive"))
    )
    (net (code "132") (name "Net-(IC17-+IN)") (class "Default")
      (node (ref "IC17") (pin "4") (pinfunction "+IN_4") (pintype "bidirectional"))
      (node (ref "R90") (pin "2") (pinfunction "2_2") (pintype "passive"))
    )
    (net (code "133") (name "Net-(IC17-+RG)") (class "Default")
      (node (ref "IC17") (pin "3") (pinfunction "+RG_3") (pintype "bidirectional"))
      (node (ref "IC18") (pin "12") (pinfunction "+IN4_12") (pintype "bidirectional"))
      (node (ref "R91") (pin "1") (pinfunction "1_1") (pintype "passive"))
    )
    (net (code "134") (name "Net-(IC17--IN)") (class "Default")
      (node (ref "IC17") (pin "1") (pinfunction "-IN_1") (pintype "bidirectional"))
      (node (ref "R89") (pin "2") (pinfunction "2_2") (pintype "passive"))
    )
    (net (code "135") (name "Net-(IC17--RG)") (class "Default")
      (node (ref "IC17") (pin "2") (pinfunction "-RG_2") (pintype "bidirectional"))
      (node (ref "IC18") (pin "10") (pinfunction "+IN3_10") (pintype "bidirectional"))
      (node (ref "R91") (pin "2") (pinfunction "2_2") (pintype "passive"))
    )
    (net (code "136") (name "Net-(IC17-OUT)") (class "Default")
      (node (ref "C82") (pin "1") (pinfunction "1_1") (pintype "passive"))
      (node (ref "IC17") (pin "7") (pinfunction "OUT_7") (pintype "bidirectional"))
    )
    (net (code "137") (name "Net-(IC18-+IN1)") (class "Default")
      (node (ref "C86") (pin "1") (pinfunction "1_1") (pintype "passive"))
      (node (ref "IC18") (pin "3") (pinfunction "+IN1_3") (pintype "bidirectional"))
      (node (ref "R101") (pin "1") (pinfunction "1_1") (pintype "passive"))
    )
    (net (code "138") (name "Net-(IC18-+IN2)") (class "Default")
      (node (ref "C83") (pin "2") (pinfunction "2_2") (pintype "passive"))
      (node (ref "IC18") (pin "5") (pinfunction "+IN2_5") (pintype "bidirectional"))
      (node (ref "R97") (pin "1") (pinfunction "1_1") (pintype "passive"))
    )
    (net (code "139") (name "Net-(IC18--IN1)") (class "Default")
      (node (ref "IC18") (pin "2") (pinfunction "-IN1_2") (pintype "bidirectional"))
      (node (ref "R102") (pin "1") (pinfunction "1_1") (pintype "passive"))
      (node (ref "R103") (pin "1") (pinfunction "1_1") (pintype "passive"))
    )
    (net (code "140") (name "Net-(IC18--IN2)") (class "Default")
      (node (ref "IC18") (pin "6") (pinfunction "-IN2_6") (pintype "bidirectional"))
      (node (ref "R94") (pin "2") (pinfunction "2_2") (pintype "passive"))
      (node (ref "R95") (pin "2") (pinfunction "2_2") (pintype "passive"))
    )
    (net (code "141") (name "Net-(IC18-OUT1)") (class "Default")
      (node (ref "C87") (pin "2") (pinfunction "2_2") (pintype "passive"))
      (node (ref "IC18") (pin "1") (pinfunction "OUT1_1") (pintype "bidirectional"))
      (node (ref "R103") (pin "2") (pinfunction "2_2") (pintype "passive"))
      (node (ref "R99") (pin "2") (pinfunction "2_2") (pintype "passive"))
    )
    (net (code "142") (name "Net-(IC18-OUT2)") (class "Default")
      (node (ref "IC18") (pin "7") (pinfunction "OUT2_7") (pintype "bidirectional"))
      (node (ref "R95") (pin "1") (pinfunction "1_1") (pintype "passive"))
      (node (ref "R96") (pin "2") (pinfunction "2_2") (pintype "passive"))
      (node (ref "R98") (pin "2") (pinfunction "2_2") (pintype "passive"))
    )
    (net (code "143") (name "Net-(IC19--IN)") (class "Default")
      (node (ref "IC19") (pin "4") (pinfunction "-IN_4") (pintype "bidirectional"))
      (node (ref "R100") (pin "1") (pinfunction "1_1") (pintype "passive"))
      (node (ref "R99") (pin "1") (pinfunction "1_1") (pintype "passive"))
    )
    (net (code "144") (name "Net-(IC19-OUT)") (class "Default")
      (node (ref "IC19") (pin "1") (pinfunction "OUT_1") (pintype "bidirectional"))
      (node (ref "R100") (pin "2") (pinfunction "2_2") (pintype "passive"))
      (node (ref "R104") (pin "2") (pinfunction "2_2") (pintype "passive"))
    )
    (net (code "145") (name "Net-(IC20-+IN)") (class "Default")
      (node (ref "IC20") (pin "4") (pinfunction "+IN_4") (pintype "bidirectional"))
      (node (ref "R110") (pin "2") (pinfunction "2_2") (pintype "passive"))
    )
    (net (code "146") (name "Net-(IC20-+RG)") (class "Default")
      (node (ref "IC20") (pin "3") (pinfunction "+RG_3") (pintype "bidirectional"))
      (node (ref "IC21") (pin "12") (pinfunction "+IN4_12") (pintype "bidirectional"))
      (node (ref "R111") (pin "1") (pinfunction "1_1") (pintype "passive"))
    )
    (net (code "147") (name "Net-(IC20--IN)") (class "Default")
      (node (ref "IC20") (pin "1") (pinfunction "-IN_1") (pintype "bidirectional"))
      (node (ref "R109") (pin "2") (pinfunction "2_2") (pintype "passive"))
    )
    (net (code "148") (name "Net-(IC20--RG)") (class "Default")
      (node (ref "IC20") (pin "2") (pinfunction "-RG_2") (pintype "bidirectional"))
      (node (ref "IC21") (pin "10") (pinfunction "+IN3_10") (pintype "bidirectional"))
      (node (ref "R111") (pin "2") (pinfunction "2_2") (pintype "passive"))
    )
    (net (code "149") (name "Net-(IC20-OUT)") (class "Default")
      (node (ref "C96") (pin "1") (pinfunction "1_1") (pintype "passive"))
      (node (ref "IC20") (pin "7") (pinfunction "OUT_7") (pintype "bidirectional"))
    )
    (net (code "150") (name "Net-(IC21-+IN1)") (class "Default")
      (node (ref "C100") (pin "1") (pinfunction "1_1") (pintype "passive"))
      (node (ref "IC21") (pin "3") (pinfunction "+IN1_3") (pintype "bidirectional"))
      (node (ref "R121") (pin "1") (pinfunction "1_1") (pintype "passive"))
    )
    (net (code "151") (name "Net-(IC21-+IN2)") (class "Default")
      (node (ref "C97") (pin "2") (pinfunction "2_2") (pintype "passive"))
      (node (ref "IC21") (pin "5") (pinfunction "+IN2_5") (pintype "bidirectional"))
      (node (ref "R117") (pin "1") (pinfunction "1_1") (pintype "passive"))
    )
    (net (code "152") (name "Net-(IC21--IN1)") (class "Default")
      (node (ref "IC21") (pin "2") (pinfunction "-IN1_2") (pintype "bidirectional"))
      (node (ref "R122") (pin "1") (pinfunction "1_1") (pintype "passive"))
      (node (ref "R123") (pin "1") (pinfunction "1_1") (pintype "passive"))
    )
    (net (code "153") (name "Net-(IC21--IN2)") (class "Default")
      (node (ref "IC21") (pin "6") (pinfunction "-IN2_6") (pintype "bidirectional"))
      (node (ref "R114") (pin "2") (pinfunction "2_2") (pintype "passive"))
      (node (ref "R115") (pin "2") (pinfunction "2_2") (pintype "passive"))
    )
    (net (code "154") (name "Net-(IC21-OUT1)") (class "Default")
      (node (ref "C101") (pin "2") (pinfunction "2_2") (pintype "passive"))
      (node (ref "IC21") (pin "1") (pinfunction "OUT1_1") (pintype "bidirectional"))
      (node (ref "R119") (pin "2") (pinfunction "2_2") (pintype "passive"))
      (node (ref "R123") (pin "2") (pinfunction "2_2") (pintype "passive"))
    )
    (net (code "155") (name "Net-(IC21-OUT2)") (class "Default")
      (node (ref "IC21") (pin "7") (pinfunction "OUT2_7") (pintype "bidirectional"))
      (node (ref "R115") (pin "1") (pinfunction "1_1") (pintype "passive"))
      (node (ref "R116") (pin "2") (pinfunction "2_2") (pintype "passive"))
      (node (ref "R118") (pin "2") (pinfunction "2_2") (pintype "passive"))
    )
    (net (code "156") (name "Net-(IC22--IN)") (class "Default")
      (node (ref "IC22") (pin "4") (pinfunction "-IN_4") (pintype "bidirectional"))
      (node (ref "R119") (pin "1") (pinfunction "1_1") (pintype "passive"))
      (node (ref "R120") (pin "1") (pinfunction "1_1") (pintype "passive"))
    )
    (net (code "157") (name "Net-(IC22-OUT)") (class "Default")
      (node (ref "IC22") (pin "1") (pinfunction "OUT_1") (pintype "bidirectional"))
      (node (ref "R120") (pin "2") (pinfunction "2_2") (pintype "passive"))
      (node (ref "R124") (pin "2") (pinfunction "2_2") (pintype "passive"))
    )
    (net (code "158") (name "Net-(IC23-+IN)") (class "Default")
      (node (ref "IC23") (pin "4") (pinfunction "+IN_4") (pintype "bidirectional"))
      (node (ref "R130") (pin "2") (pinfunction "2_2") (pintype "passive"))
    )
    (net (code "159") (name "Net-(IC23-+RG)") (class "Default")
      (node (ref "IC23") (pin "3") (pinfunction "+RG_3") (pintype "bidirectional"))
      (node (ref "IC24") (pin "12") (pinfunction "+IN4_12") (pintype "bidirectional"))
      (node (ref "R131") (pin "1") (pinfunction "1_1") (pintype "passive"))
    )
    (net (code "160") (name "Net-(IC23--IN)") (class "Default")
      (node (ref "IC23") (pin "1") (pinfunction "-IN_1") (pintype "bidirectional"))
      (node (ref "R129") (pin "2") (pinfunction "2_2") (pintype "passive"))
    )
    (net (code "161") (name "Net-(IC23--RG)") (class "Default")
      (node (ref "IC23") (pin "2") (pinfunction "-RG_2") (pintype "bidirectional"))
      (node (ref "IC24") (pin "10") (pinfunction "+IN3_10") (pintype "bidirectional"))
      (node (ref "R131") (pin "2") (pinfunction "2_2") (pintype "passive"))
    )
    (net (code "162") (name "Net-(IC23-OUT)") (class "Default")
      (node (ref "C110") (pin "1") (pinfunction "1_1") (pintype "passive"))
      (node (ref "IC23") (pin "7") (pinfunction "OUT_7") (pintype "bidirectional"))
    )
    (net (code "163") (name "Net-(IC24-+IN1)") (class "Default")
      (node (ref "C114") (pin "1") (pinfunction "1_1") (pintype "passive"))
      (node (ref "IC24") (pin "3") (pinfunction "+IN1_3") (pintype "bidirectional"))
      (node (ref "R141") (pin "1") (pinfunction "1_1") (pintype "passive"))
    )
    (net (code "164") (name "Net-(IC24-+IN2)") (class "Default")
      (node (ref "C111") (pin "2") (pinfunction "2_2") (pintype "passive"))
      (node (ref "IC24") (pin "5") (pinfunction "+IN2_5") (pintype "bidirectional"))
      (node (ref "R137") (pin "1") (pinfunction "1_1") (pintype "passive"))
    )
    (net (code "165") (name "Net-(IC24--IN1)") (class "Default")
      (node (ref "IC24") (pin "2") (pinfunction "-IN1_2") (pintype "bidirectional"))
      (node (ref "R142") (pin "1") (pinfunction "1_1") (pintype "passive"))
      (node (ref "R143") (pin "1") (pinfunction "1_1") (pintype "passive"))
    )
    (net (code "166") (name "Net-(IC24--IN2)") (class "Default")
      (node (ref "IC24") (pin "6") (pinfunction "-IN2_6") (pintype "bidirectional"))
      (node (ref "R134") (pin "2") (pinfunction "2_2") (pintype "passive"))
      (node (ref "R135") (pin "2") (pinfunction "2_2") (pintype "passive"))
    )
    (net (code "167") (name "Net-(IC24-OUT1)") (class "Default")
      (node (ref "C115") (pin "2") (pinfunction "2_2") (pintype "passive"))
      (node (ref "IC24") (pin "1") (pinfunction "OUT1_1") (pintype "bidirectional"))
      (node (ref "R139") (pin "2") (pinfunction "2_2") (pintype "passive"))
      (node (ref "R143") (pin "2") (pinfunction "2_2") (pintype "passive"))
    )
    (net (code "168") (name "Net-(IC24-OUT2)") (class "Default")
      (node (ref "IC24") (pin "7") (pinfunction "OUT2_7") (pintype "bidirectional"))
      (node (ref "R135") (pin "1") (pinfunction "1_1") (pintype "passive"))
      (node (ref "R136") (pin "2") (pinfunction "2_2") (pintype "passive"))
      (node (ref "R138") (pin "2") (pinfunction "2_2") (pintype "passive"))
    )
    (net (code "169") (name "Net-(IC25--IN)") (class "Default")
      (node (ref "IC25") (pin "4") (pinfunction "-IN_4") (pintype "bidirectional"))
      (node (ref "R139") (pin "1") (pinfunction "1_1") (pintype "passive"))
      (node (ref "R140") (pin "1") (pinfunction "1_1") (pintype "passive"))
    )
    (net (code "170") (name "Net-(IC25-OUT)") (class "Default")
      (node (ref "IC25") (pin "1") (pinfunction "OUT_1") (pintype "bidirectional"))
      (node (ref "R140") (pin "2") (pinfunction "2_2") (pintype "passive"))
      (node (ref "R144") (pin "2") (pinfunction "2_2") (pintype "passive"))
    )
    (net (code "171") (name "Net-(IC26-+IN)") (class "Default")
      (node (ref "IC26") (pin "4") (pinfunction "+IN_4") (pintype "bidirectional"))
      (node (ref "R150") (pin "2") (pinfunction "2_2") (pintype "passive"))
    )
    (net (code "172") (name "Net-(IC26-+RG)") (class "Default")
      (node (ref "IC26") (pin "3") (pinfunction "+RG_3") (pintype "bidirectional"))
      (node (ref "IC27") (pin "12") (pinfunction "+IN4_12") (pintype "bidirectional"))
      (node (ref "R151") (pin "1") (pinfunction "1_1") (pintype "passive"))
    )
    (net (code "173") (name "Net-(IC26--IN)") (class "Default")
      (node (ref "IC26") (pin "1") (pinfunction "-IN_1") (pintype "bidirectional"))
      (node (ref "R149") (pin "2") (pinfunction "2_2") (pintype "passive"))
    )
    (net (code "174") (name "Net-(IC26--RG)") (class "Default")
      (node (ref "IC26") (pin "2") (pinfunction "-RG_2") (pintype "bidirectional"))
      (node (ref "IC27") (pin "10") (pinfunction "+IN3_10") (pintype "bidirectional"))
      (node (ref "R151") (pin "2") (pinfunction "2_2") (pintype "passive"))
    )
    (net (code "175") (name "Net-(IC26-OUT)") (class "Default")
      (node (ref "C124") (pin "1") (pinfunction "1_1") (pintype "passive"))
      (node (ref "IC26") (pin "7") (pinfunction "OUT_7") (pintype "bidirectional"))
    )
    (net (code "176") (name "Net-(IC27-+IN1)") (class "Default")
      (node (ref "C128") (pin "1") (pinfunction "1_1") (pintype "passive"))
      (node (ref "IC27") (pin "3") (pinfunction "+IN1_3") (pintype "bidirectional"))
      (node (ref "R161") (pin "1") (pinfunction "1_1") (pintype "passive"))
    )
    (net (code "177") (name "Net-(IC27-+IN2)") (class "Default")
      (node (ref "C125") (pin "2") (pinfunction "2_2") (pintype "passive"))
      (node (ref "IC27") (pin "5") (pinfunction "+IN2_5") (pintype "bidirectional"))
      (node (ref "R157") (pin "1") (pinfunction "1_1") (pintype "passive"))
    )
    (net (code "178") (name "Net-(IC27--IN1)") (class "Default")
      (node (ref "IC27") (pin "2") (pinfunction "-IN1_2") (pintype "bidirectional"))
      (node (ref "R162") (pin "1") (pinfunction "1_1") (pintype "passive"))
      (node (ref "R163") (pin "1") (pinfunction "1_1") (pintype "passive"))
    )
    (net (code "179") (name "Net-(IC27--IN2)") (class "Default")
      (node (ref "IC27") (pin "6") (pinfunction "-IN2_6") (pintype "bidirectional"))
      (node (ref "R154") (pin "2") (pinfunction "2_2") (pintype "passive"))
      (node (ref "R155") (pin "2") (pinfunction "2_2") (pintype "passive"))
    )
    (net (code "180") (name "Net-(IC27-OUT1)") (class "Default")
      (node (ref "C129") (pin "2") (pinfunction "2_2") (pintype "passive"))
      (node (ref "IC27") (pin "1") (pinfunction "OUT1_1") (pintype "bidirectional"))
      (node (ref "R159") (pin "2") (pinfunction "2_2") (pintype "passive"))
      (node (ref "R163") (pin "2") (pinfunction "2_2") (pintype "passive"))
    )
    (net (code "181") (name "Net-(IC27-OUT2)") (class "Default")
      (node (ref "IC27") (pin "7") (pinfunction "OUT2_7") (pintype "bidirectional"))
      (node (ref "R155") (pin "1") (pinfunction "1_1") (pintype "passive"))
      (node (ref "R156") (pin "2") (pinfunction "2_2") (pintype "passive"))
      (node (ref "R158") (pin "2") (pinfunction "2_2") (pintype "passive"))
    )
    (net (code "182") (name "Net-(IC28--IN)") (class "Default")
      (node (ref "IC28") (pin "4") (pinfunction "-IN_4") (pintype "bidirectional"))
      (node (ref "R159") (pin "1") (pinfunction "1_1") (pintype "passive"))
      (node (ref "R160") (pin "1") (pinfunction "1_1") (pintype "passive"))
    )
    (net (code "183") (name "Net-(IC28-OUT)") (class "Default")
      (node (ref "IC28") (pin "1") (pinfunction "OUT_1") (pintype "bidirectional"))
      (node (ref "R160") (pin "2") (pinfunction "2_2") (pintype "passive"))
      (node (ref "R164") (pin "2") (pinfunction "2_2") (pintype "passive"))
    )
    (net (code "184") (name "Net-(IN1-Pad1)") (class "Default")
      (node (ref "IN1") (pin "1") (pinfunction "1_1") (pintype "passive"))
      (node (ref "R2") (pin "1") (pinfunction "1_1") (pintype "passive"))
    )
    (net (code "185") (name "Net-(IN1-Pad2)") (class "Default")
      (node (ref "IN1") (pin "2") (pinfunction "2_2") (pintype "passive"))
      (node (ref "R4") (pin "1") (pinfunction "1_1") (pintype "passive"))
    )
    (net (code "186") (name "Net-(IN1-Pad3)") (class "Default")
      (node (ref "IN1") (pin "3") (pinfunction "3_3") (pintype "passive"))
      (node (ref "R3") (pin "1") (pinfunction "1_1") (pintype "passive"))
    )
    (net (code "187") (name "Net-(IN1-Pad4)") (class "Default")
      (node (ref "IN1") (pin "4") (pinfunction "4_4") (pintype "passive"))
      (node (ref "R1") (pin "1") (pinfunction "1_1") (pintype "passive"))
    )
    (net (code "188") (name "Net-(IN2-Pad1)") (class "Default")
      (node (ref "IN2") (pin "1") (pinfunction "1_1") (pintype "passive"))
      (node (ref "R26") (pin "1") (pinfunction "1_1") (pintype "passive"))
    )
    (net (code "189") (name "Net-(IN2-Pad2)") (class "Default")
      (node (ref "IN2") (pin "2") (pinfunction "2_2") (pintype "passive"))
      (node (ref "R28") (pin "1") (pinfunction "1_1") (pintype "passive"))
    )
    (net (code "190") (name "Net-(IN2-Pad3)") (class "Default")
      (node (ref "IN2") (pin "3") (pinfunction "3_3") (pintype "passive"))
      (node (ref "R27") (pin "1") (pinfunction "1_1") (pintype "passive"))
    )
    (net (code "191") (name "Net-(IN2-Pad4)") (class "Default")
      (node (ref "IN2") (pin "4") (pinfunction "4_4") (pintype "passive"))
      (node (ref "R24") (pin "1") (pinfunction "1_1") (pintype "passive"))
    )
    (net (code "192") (name "Net-(IN3-Pad1)") (class "Default")
      (node (ref "IN3") (pin "1") (pinfunction "1_1") (pintype "passive"))
      (node (ref "R46") (pin "1") (pinfunction "1_1") (pintype "passive"))
    )
    (net (code "193") (name "Net-(IN3-Pad2)") (class "Default")
      (node (ref "IN3") (pin "2") (pinfunction "2_2") (pintype "passive"))
      (node (ref "R48") (pin "1") (pinfunction "1_1") (pintype "passive"))
    )
    (net (code "194") (name "Net-(IN3-Pad3)") (class "Default")
      (node (ref "IN3") (pin "3") (pinfunction "3_3") (pintype "passive"))
      (node (ref "R47") (pin "1") (pinfunction "1_1") (pintype "passive"))
    )
    (net (code "195") (name "Net-(IN3-Pad4)") (class "Default")
      (node (ref "IN3") (pin "4") (pinfunction "4_4") (pintype "passive"))
      (node (ref "R45") (pin "1") (pinfunction "1_1") (pintype "passive"))
    )
    (net (code "196") (name "Net-(IN4-Pad1)") (class "Default")
      (node (ref "IN4") (pin "1") (pinfunction "1_1") (pintype "passive"))
      (node (ref "R66") (pin "1") (pinfunction "1_1") (pintype "passive"))
    )
    (net (code "197") (name "Net-(IN4-Pad2)") (class "Default")
      (node (ref "IN4") (pin "2") (pinfunction "2_2") (pintype "passive"))
      (node (ref "R68") (pin "1") (pinfunction "1_1") (pintype "passive"))
    )
    (net (code "198") (name "Net-(IN4-Pad3)") (class "Default")
      (node (ref "IN4") (pin "3") (pinfunction "3_3") (pintype "passive"))
      (node (ref "R67") (pin "1") (pinfunction "1_1") (pintype "passive"))
    )
    (net (code "199") (name "Net-(IN4-Pad4)") (class "Default")
      (node (ref "IN4") (pin "4") (pinfunction "4_4") (pintype "passive"))
      (node (ref "R65") (pin "1") (pinfunction "1_1") (pintype "passive"))
    )
    (net (code "200") (name "Net-(IN5-Pad1)") (class "Default")
      (node (ref "IN5") (pin "1") (pinfunction "1_1") (pintype "passive"))
      (node (ref "R86") (pin "1") (pinfunction "1_1") (pintype "passive"))
    )
    (net (code "201") (name "Net-(IN5-Pad2)") (class "Default")
      (node (ref "IN5") (pin "2") (pinfunction "2_2") (pintype "passive"))
      (node (ref "R88") (pin "1") (pinfunction "1_1") (pintype "passive"))
    )
    (net (code "202") (name "Net-(IN5-Pad3)") (class "Default")
      (node (ref "IN5") (pin "3") (pinfunction "3_3") (pintype "passive"))
      (node (ref "R87") (pin "1") (pinfunction "1_1") (pintype "passive"))
    )
    (net (code "203") (name "Net-(IN5-Pad4)") (class "Default")
      (node (ref "IN5") (pin "4") (pinfunction "4_4") (pintype "passive"))
      (node (ref "R85") (pin "1") (pinfunction "1_1") (pintype "passive"))
    )
    (net (code "204") (name "Net-(IN6-Pad1)") (class "Default")
      (node (ref "IN6") (pin "1") (pinfunction "1_1") (pintype "passive"))
      (node (ref "R106") (pin "1") (pinfunction "1_1") (pintype "passive"))
    )
    (net (code "205") (name "Net-(IN6-Pad2)") (class "Default")
      (node (ref "IN6") (pin "2") (pinfunction "2_2") (pintype "passive"))
      (node (ref "R108") (pin "1") (pinfunction "1_1") (pintype "passive"))
    )
    (net (code "206") (name "Net-(IN6-Pad3)") (class "Default")
      (node (ref "IN6") (pin "3") (pinfunction "3_3") (pintype "passive"))
      (node (ref "R107") (pin "1") (pinfunction "1_1") (pintype "passive"))
    )
    (net (code "207") (name "Net-(IN6-Pad4)") (class "Default")
      (node (ref "IN6") (pin "4") (pinfunction "4_4") (pintype "passive"))
      (node (ref "R105") (pin "1") (pinfunction "1_1") (pintype "passive"))
    )
    (net (code "208") (name "Net-(IN7-Pad1)") (class "Default")
      (node (ref "IN7") (pin "1") (pinfunction "1_1") (pintype "passive"))
      (node (ref "R126") (pin "1") (pinfunction "1_1") (pintype "passive"))
    )
    (net (code "209") (name "Net-(IN7-Pad2)") (class "Default")
      (node (ref "IN7") (pin "2") (pinfunction "2_2") (pintype "passive"))
      (node (ref "R128") (pin "1") (pinfunction "1_1") (pintype "passive"))
    )
    (net (code "210") (name "Net-(IN7-Pad3)") (class "Default")
      (node (ref "IN7") (pin "3") (pinfunction "3_3") (pintype "passive"))
      (node (ref "R127") (pin "1") (pinfunction "1_1") (pintype "passive"))
    )
    (net (code "211") (name "Net-(IN7-Pad4)") (class "Default")
      (node (ref "IN7") (pin "4") (pinfunction "4_4") (pintype "passive"))
      (node (ref "R125") (pin "1") (pinfunction "1_1") (pintype "passive"))
    )
    (net (code "212") (name "Net-(IN8-Pad1)") (class "Default")
      (node (ref "IN8") (pin "1") (pinfunction "1_1") (pintype "passive"))
      (node (ref "R146") (pin "1") (pinfunction "1_1") (pintype "passive"))
    )
    (net (code "213") (name "Net-(IN8-Pad2)") (class "Default")
      (node (ref "IN8") (pin "2") (pinfunction "2_2") (pintype "passive"))
      (node (ref "R148") (pin "1") (pinfunction "1_1") (pintype "passive"))
    )
    (net (code "214") (name "Net-(IN8-Pad3)") (class "Default")
      (node (ref "IN8") (pin "3") (pinfunction "3_3") (pintype "passive"))
      (node (ref "R147") (pin "1") (pinfunction "1_1") (pintype "passive"))
    )
    (net (code "215") (name "Net-(IN8-Pad4)") (class "Default")
      (node (ref "IN8") (pin "4") (pinfunction "4_4") (pintype "passive"))
      (node (ref "R145") (pin "1") (pinfunction "1_1") (pintype "passive"))
    )
    (net (code "216") (name "VREF") (class "Default")
      (node (ref "C113") (pin "2") (pinfunction "2_2") (pintype "passive"))
      (node (ref "C127") (pin "2") (pinfunction "2_2") (pintype "passive"))
      (node (ref "C16") (pin "1") (pinfunction "1_1") (pintype "passive"))
      (node (ref "C20") (pin "+") (pinfunction "+_+") (pintype "passive"))
      (node (ref "C40") (pin "2") (pinfunction "2_2") (pintype "passive"))
      (node (ref "C52") (pin "2") (pinfunction "2_2") (pintype "passive"))
      (node (ref "C57") (pin "2") (pinfunction "2_2") (pintype "passive"))
      (node (ref "C71") (pin "2") (pinfunction "2_2") (pintype "passive"))
      (node (ref "C85") (pin "2") (pinfunction "2_2") (pintype "passive"))
      (node (ref "C99") (pin "2") (pinfunction "2_2") (pintype "passive"))
      (node (ref "IC10") (pin "3") (pinfunction "+IN_3") (pintype "bidirectional"))
      (node (ref "IC13") (pin "3") (pinfunction "+IN_3") (pintype "bidirectional"))
      (node (ref "IC16") (pin "3") (pinfunction "+IN_3") (pintype "bidirectional"))
      (node (ref "IC19") (pin "3") (pinfunction "+IN_3") (pintype "bidirectional"))
      (node (ref "IC22") (pin "3") (pinfunction "+IN_3") (pintype "bidirectional"))
      (node (ref "IC25") (pin "3") (pinfunction "+IN_3") (pintype "bidirectional"))
      (node (ref "IC28") (pin "3") (pinfunction "+IN_3") (pintype "bidirectional"))
      (node (ref "IC3") (pin "4") (pinfunction "VREFP_4") (pintype "bidirectional"))
      (node (ref "IC3") (pin "5") (pinfunction "AINCOM_5") (pintype "bidirectional"))
      (node (ref "IC4") (pin "3") (pinfunction "+IN_3") (pintype "bidirectional"))
      (node (ref "IC7") (pin "2") (pinfunction "VOUT_2") (pintype "bidirectional"))
    )
    (net (code "217") (name "unconnected-(IC3-D0{slash}CLKOUT-Pad25)") (class "Default")
      (node (ref "IC3") (pin "25") (pinfunction "D0/CLKOUT_25") (pintype "bidirectional"))
    )
    (net (code "218") (name "unconnected-(IC3-D1-Pad26)") (class "Default")
      (node (ref "IC3") (pin "26") (pinfunction "D1_26") (pintype "bidirectional"))
    )
    (net (code "219") (name "unconnected-(IC3-D2-Pad27)") (class "Default")
      (node (ref "IC3") (pin "27") (pinfunction "D2_27") (pintype "bidirectional"))
    )
    (net (code "220") (name "unconnected-(IC3-D3-Pad28)") (class "Default")
      (node (ref "IC3") (pin "28") (pinfunction "D3_28") (pintype "bidirectional"))
    )
    (net (code "221") (name "unconnected-(IC5-VI-Pad2)") (class "Default")
      (node (ref "IC5") (pin "2") (pinfunction "VI_2") (pintype "input"))
    )
  )
)
